# Sheet1.net
KiCad netlist of a schematic drawn in Altium Designer
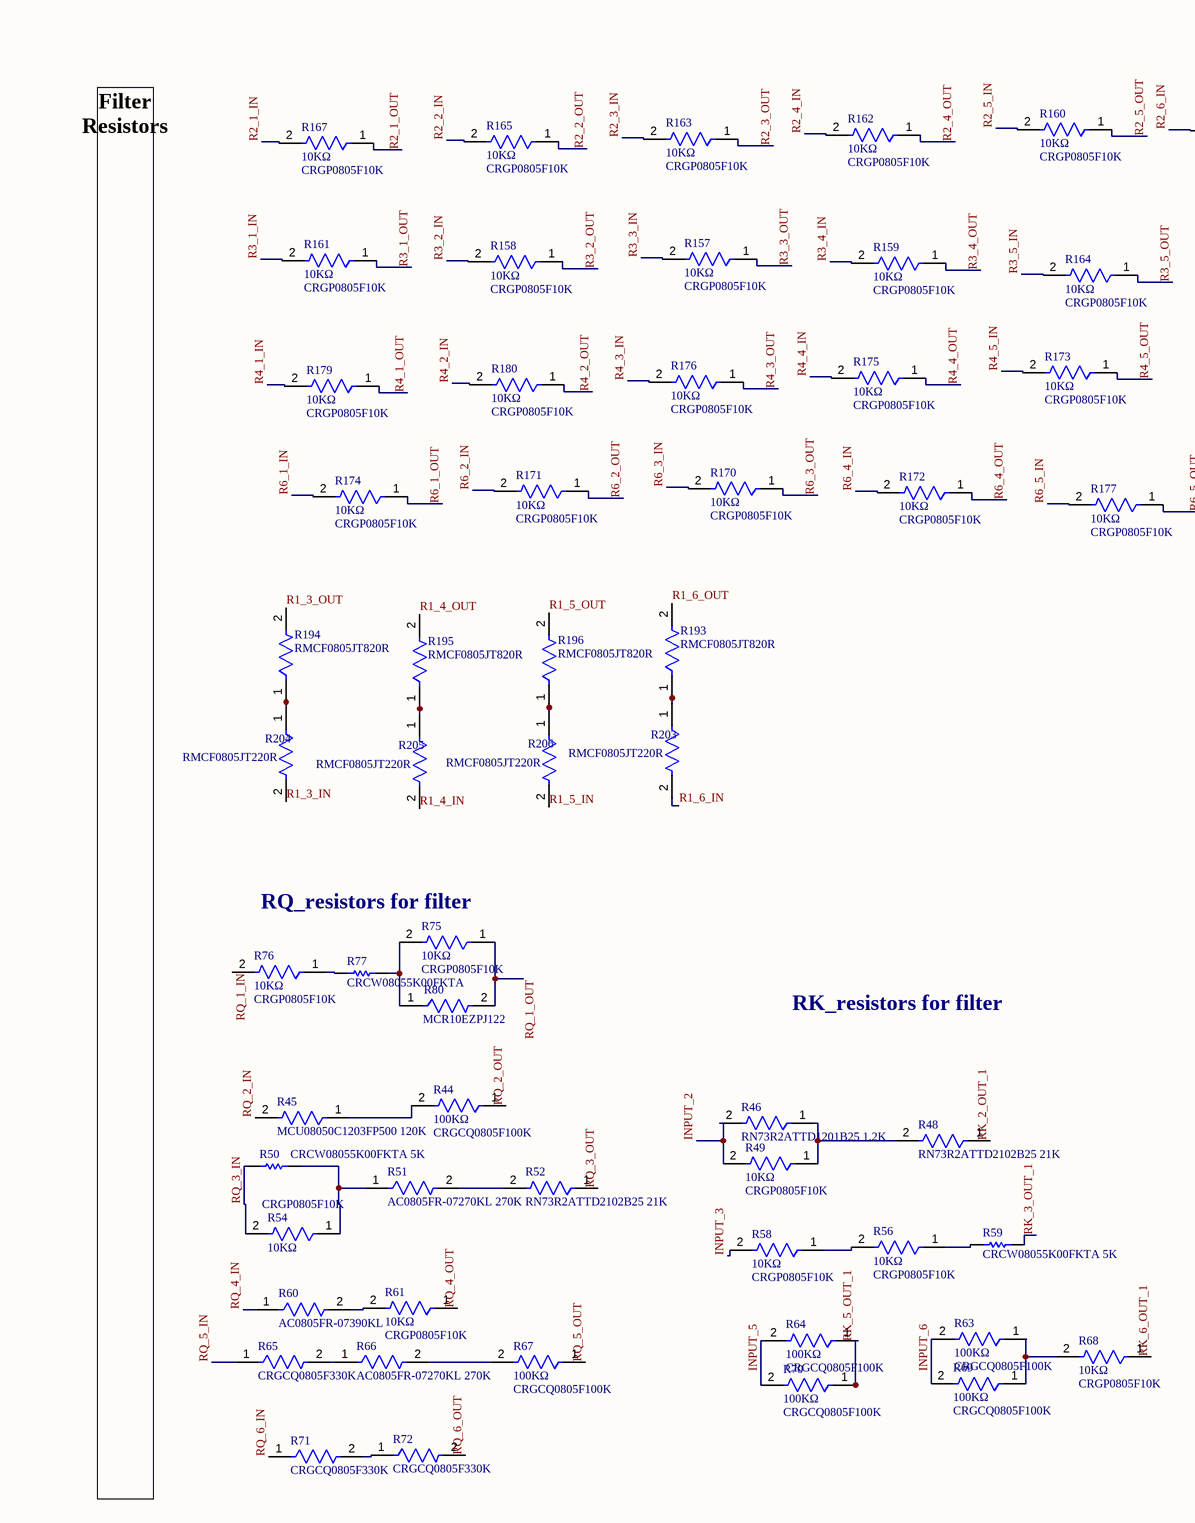
[diagram p0: Sheet1.SchDoc, top left]
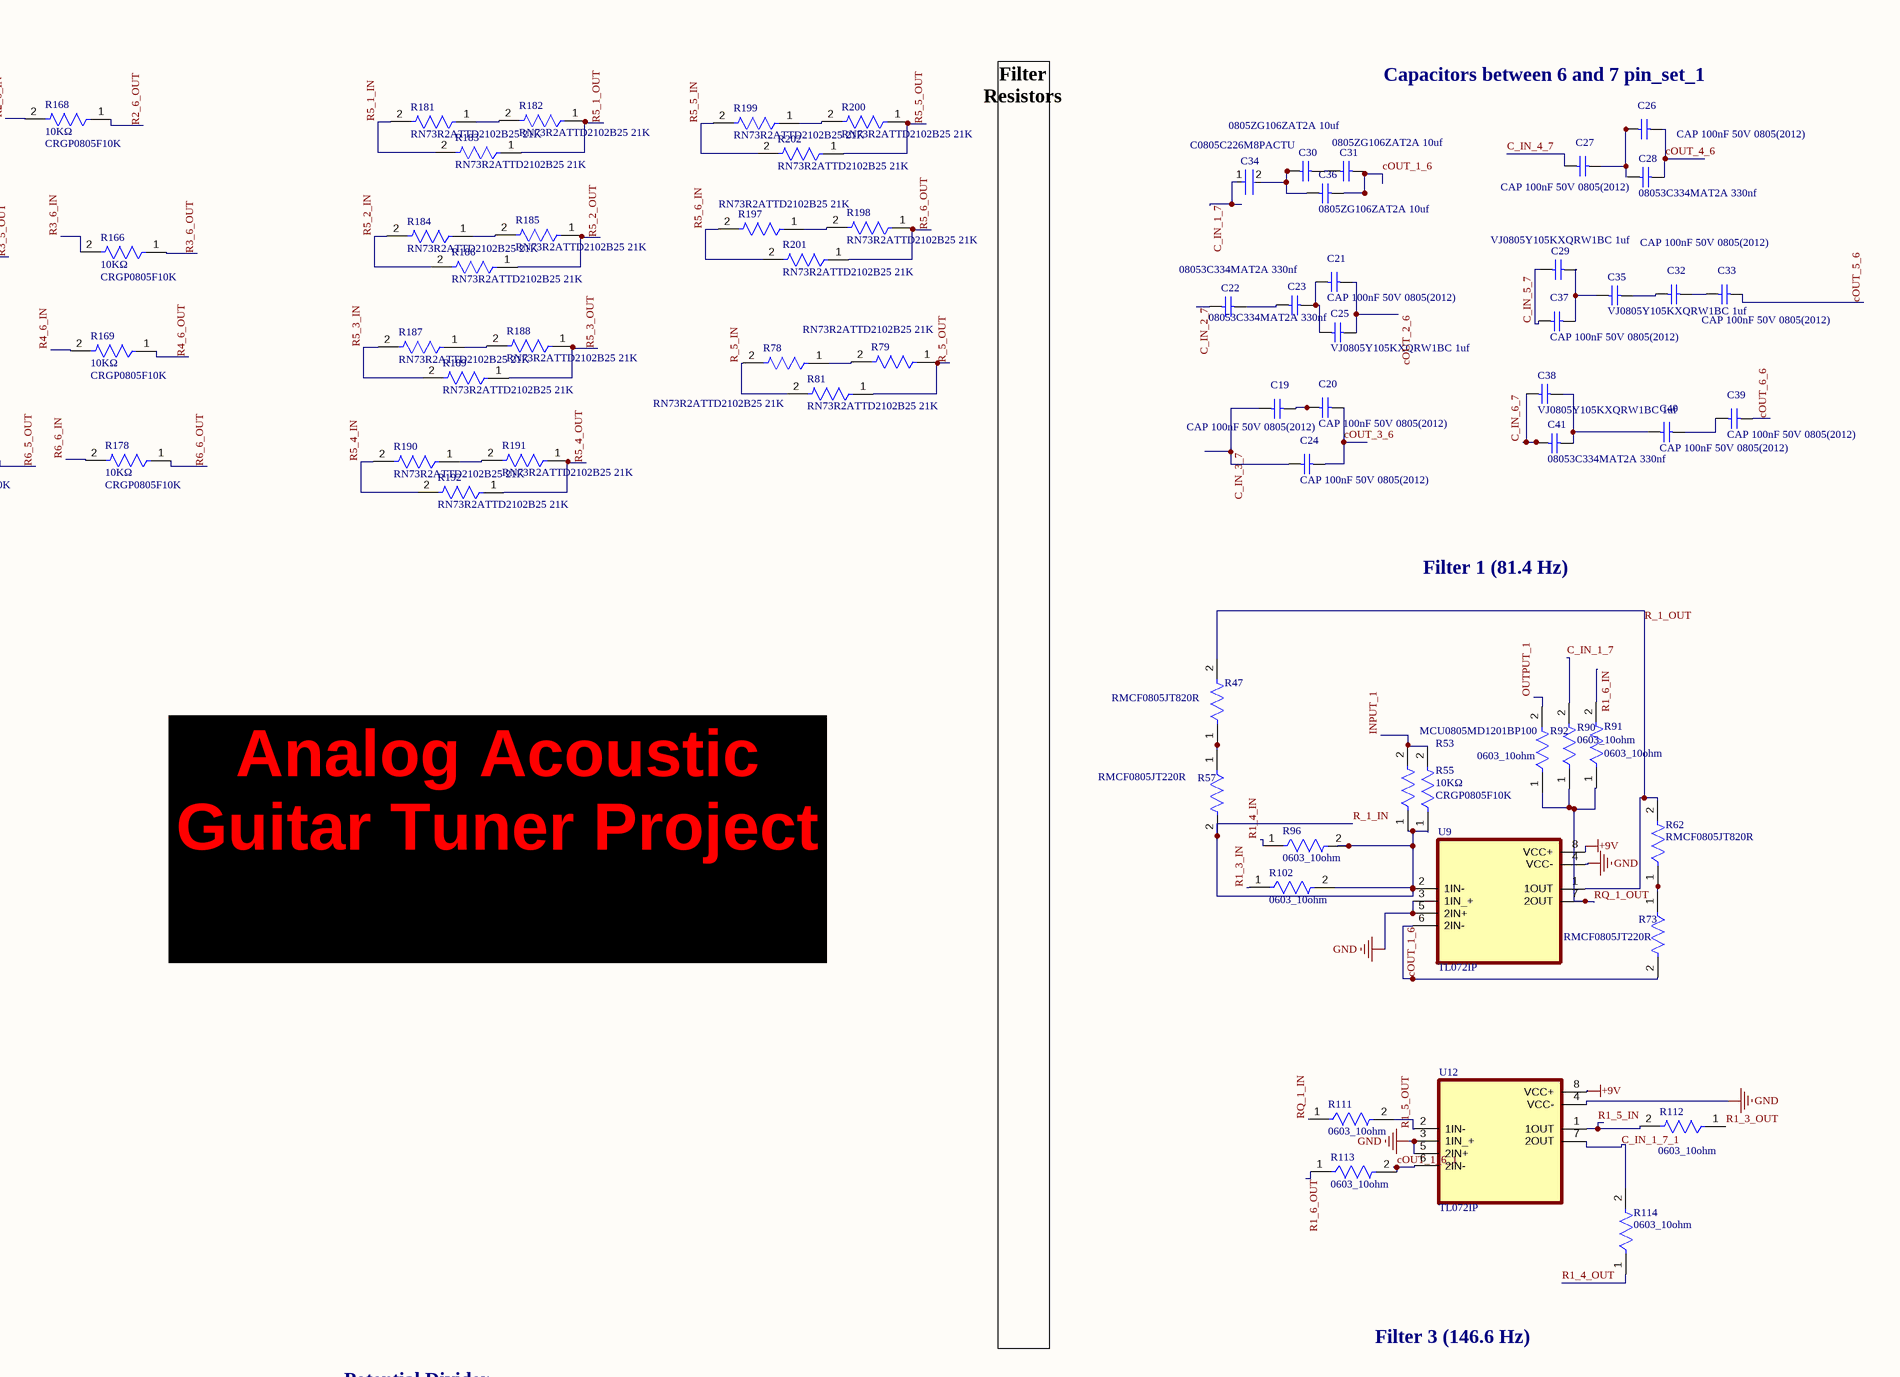
[diagram p1: Sheet1.SchDoc, top middle]
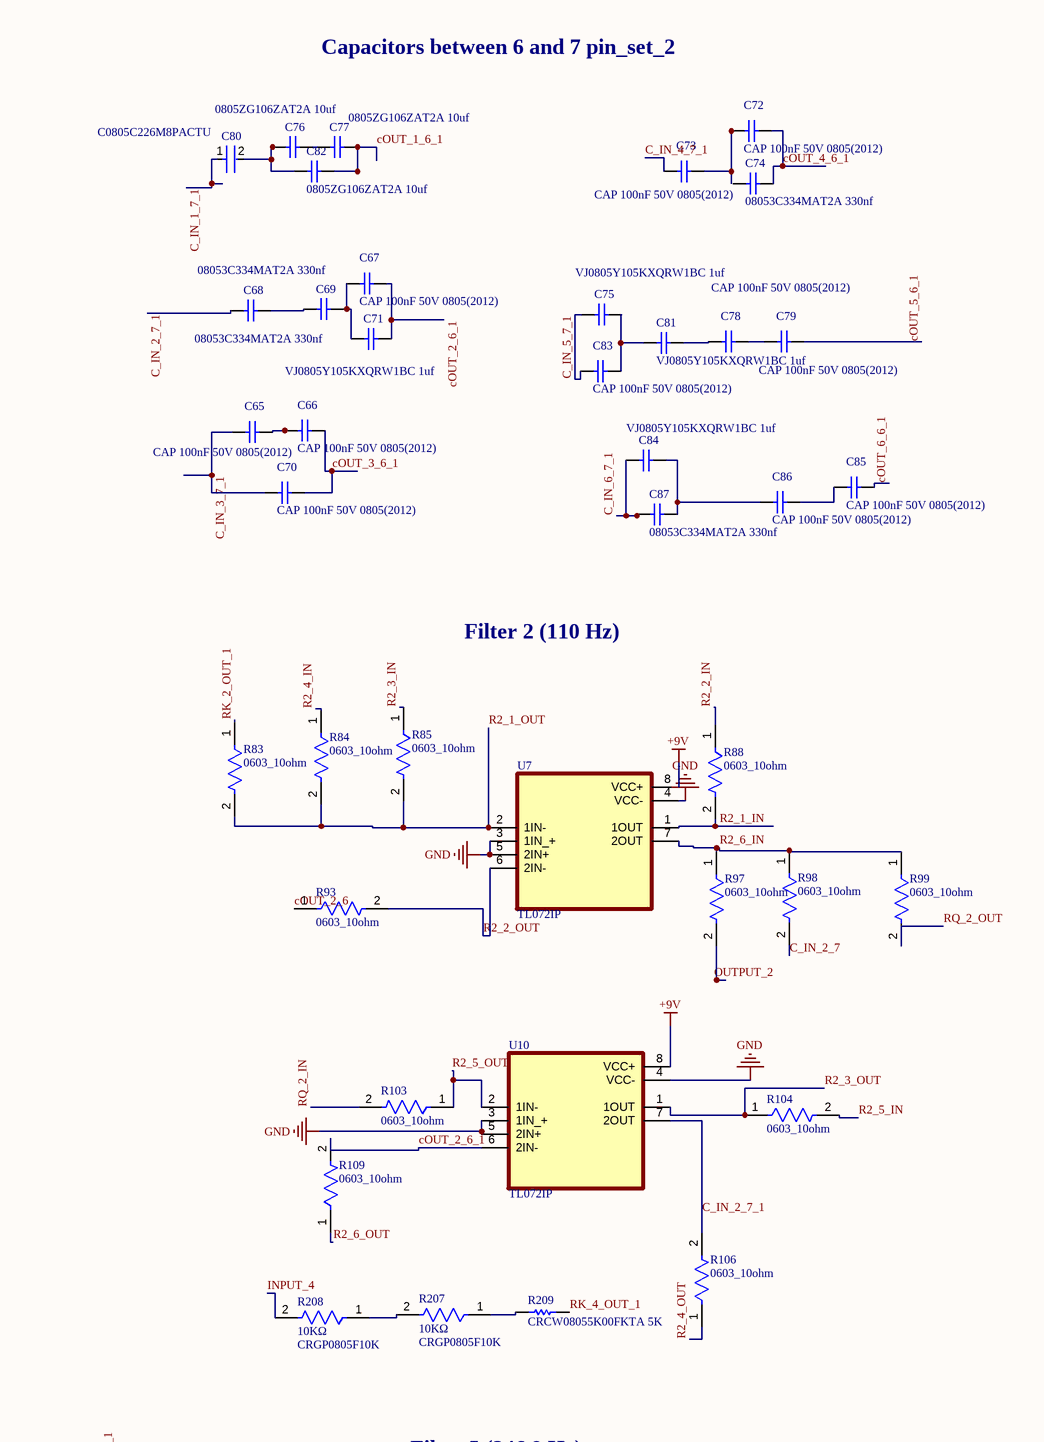
[diagram p2: Sheet1.SchDoc, top right]
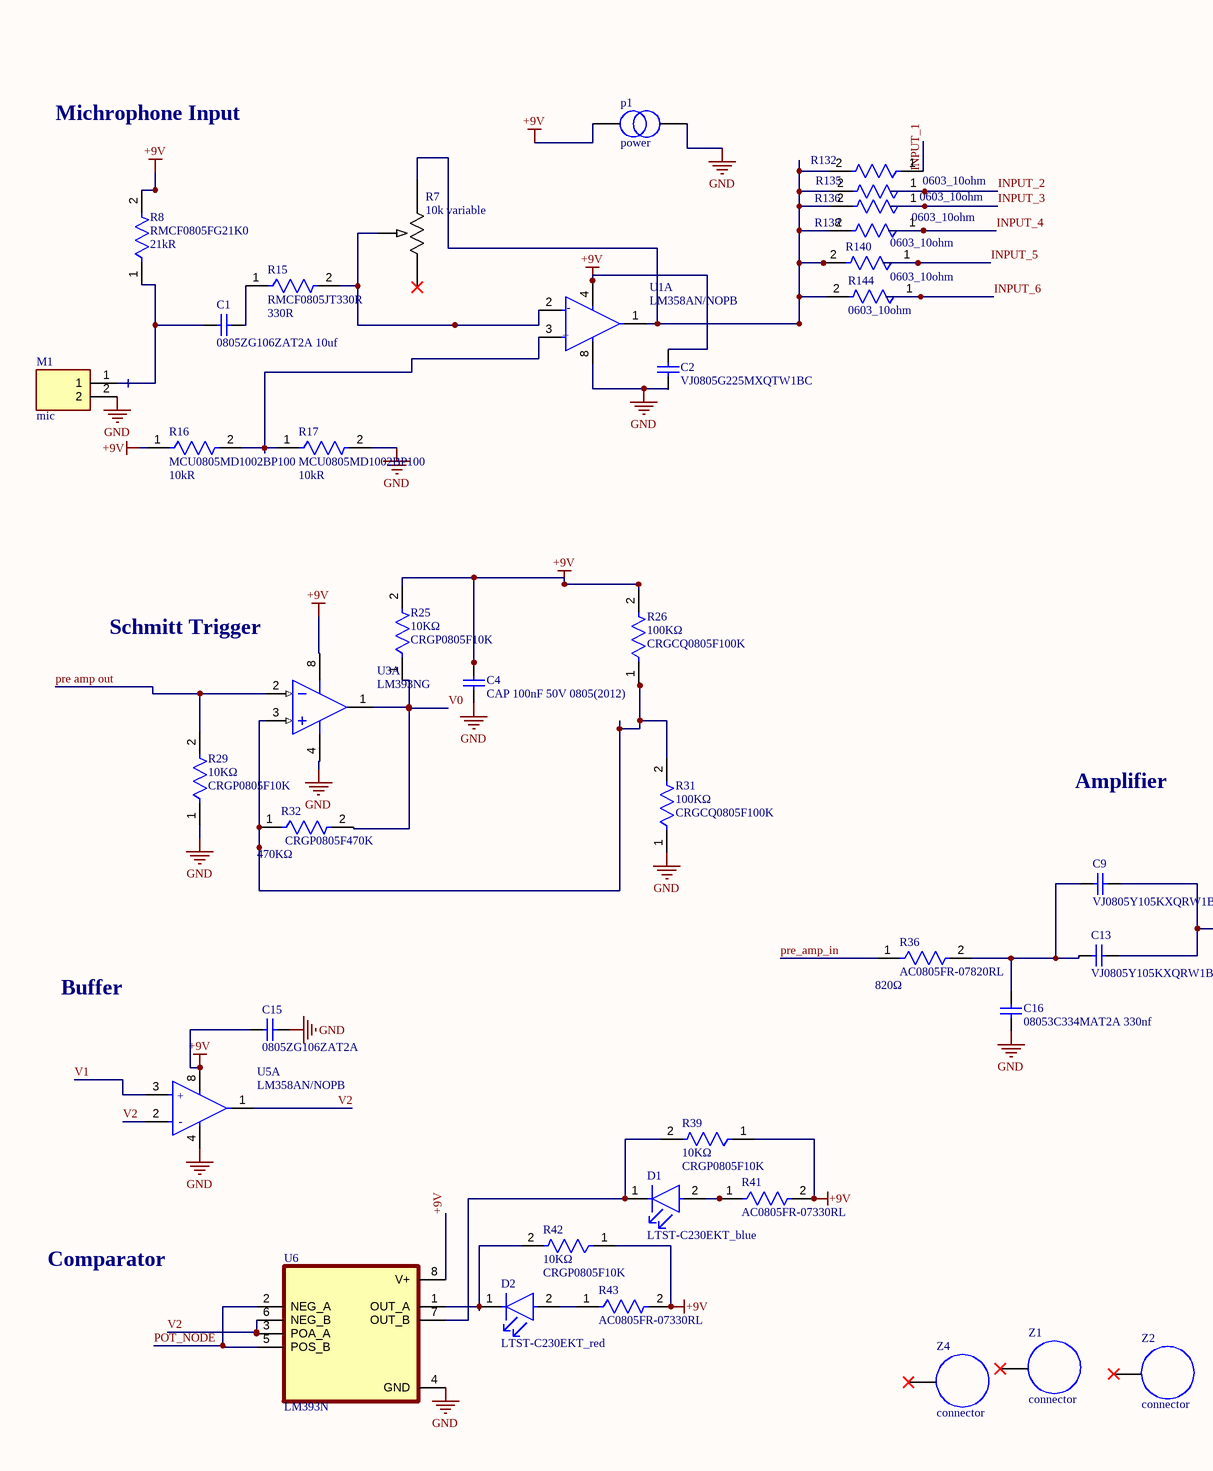
[diagram p3: Sheet1.SchDoc, bottom left]
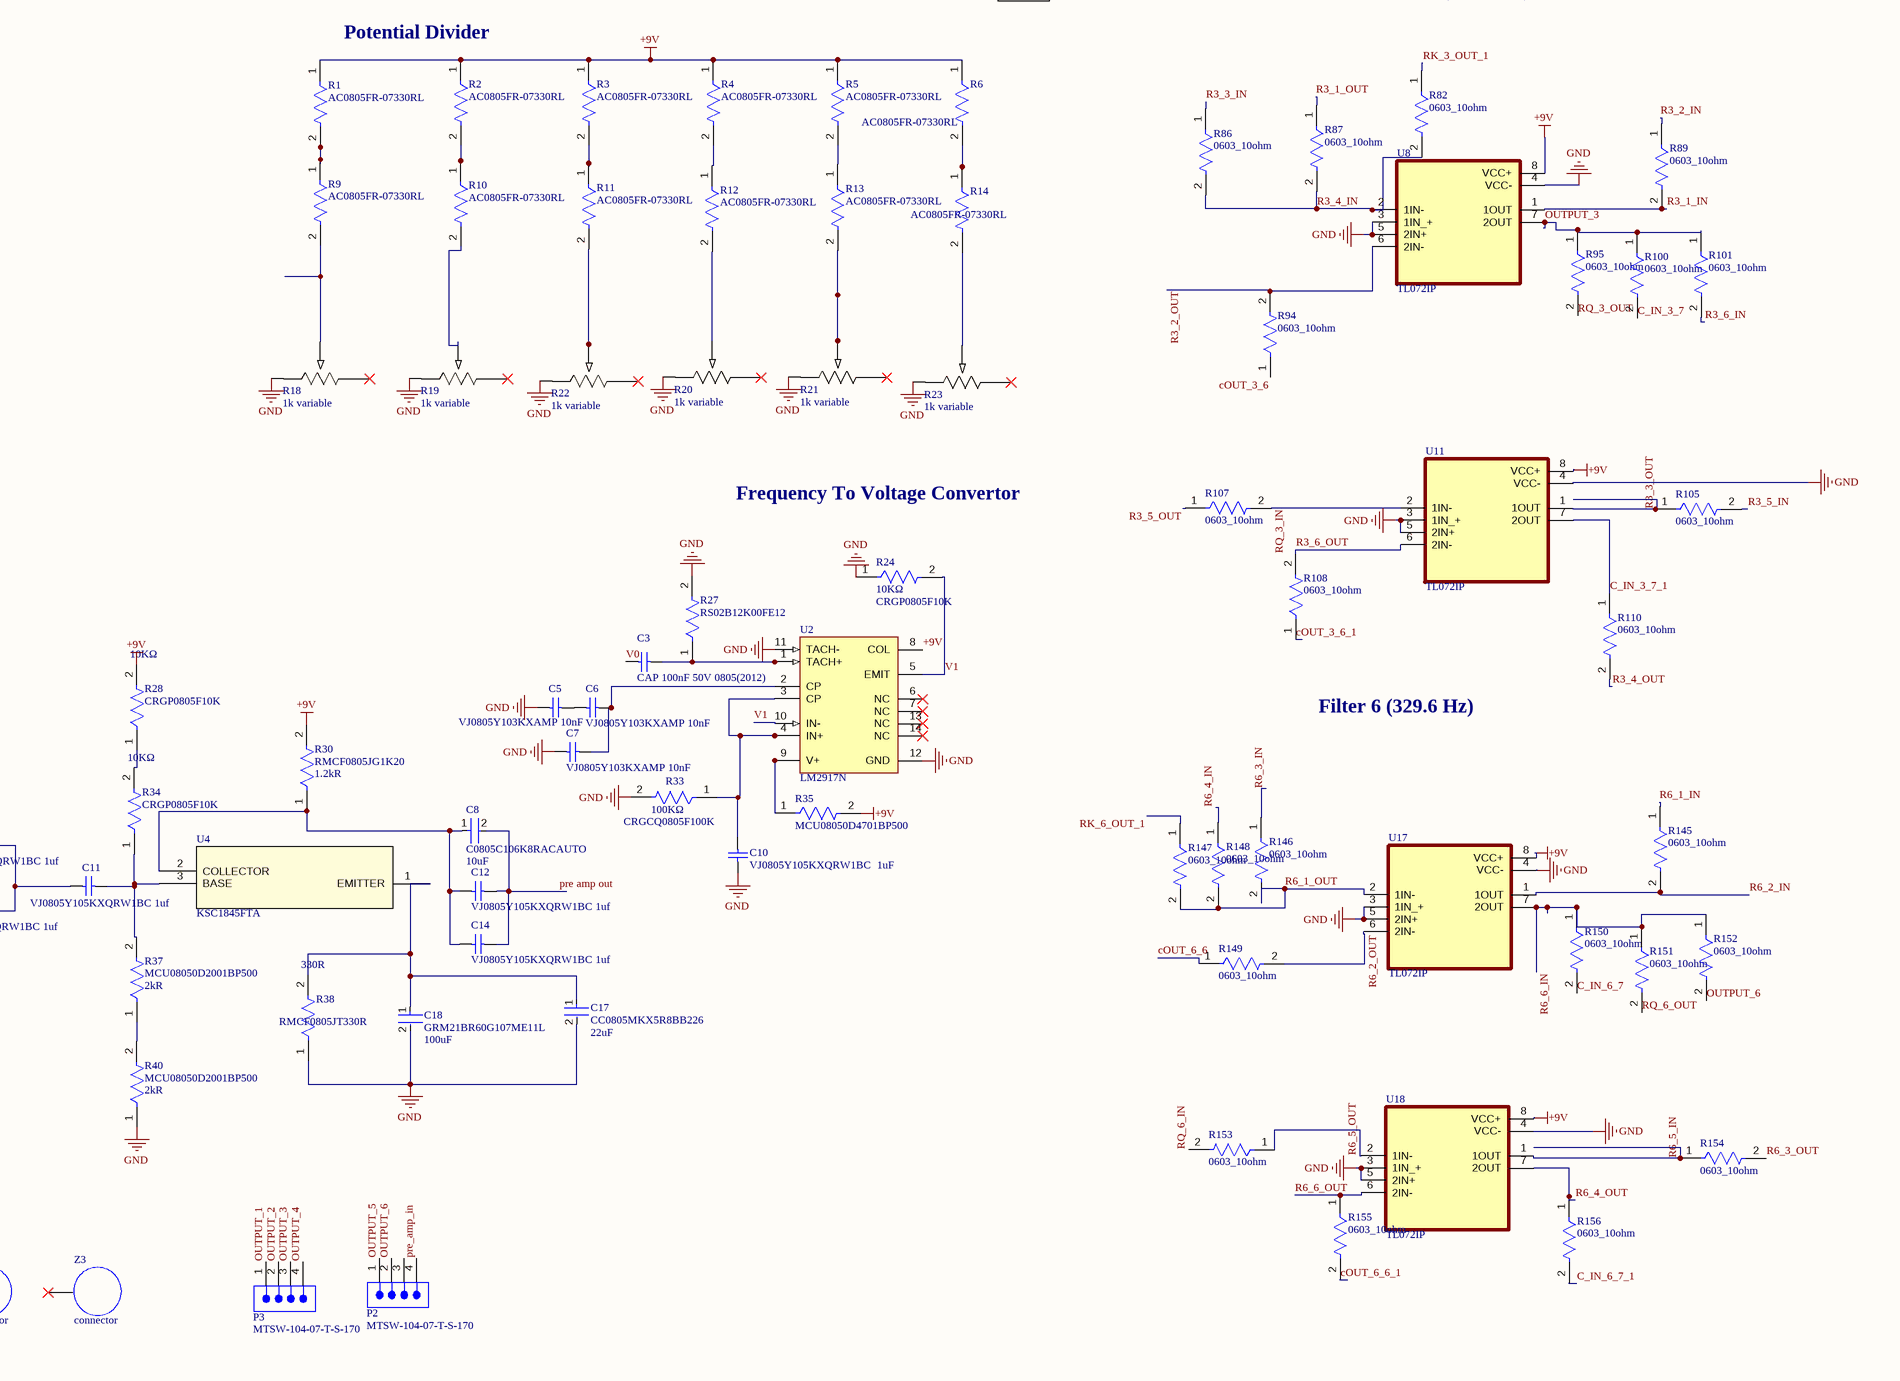
[diagram p4: Sheet1.SchDoc, bottom middle]
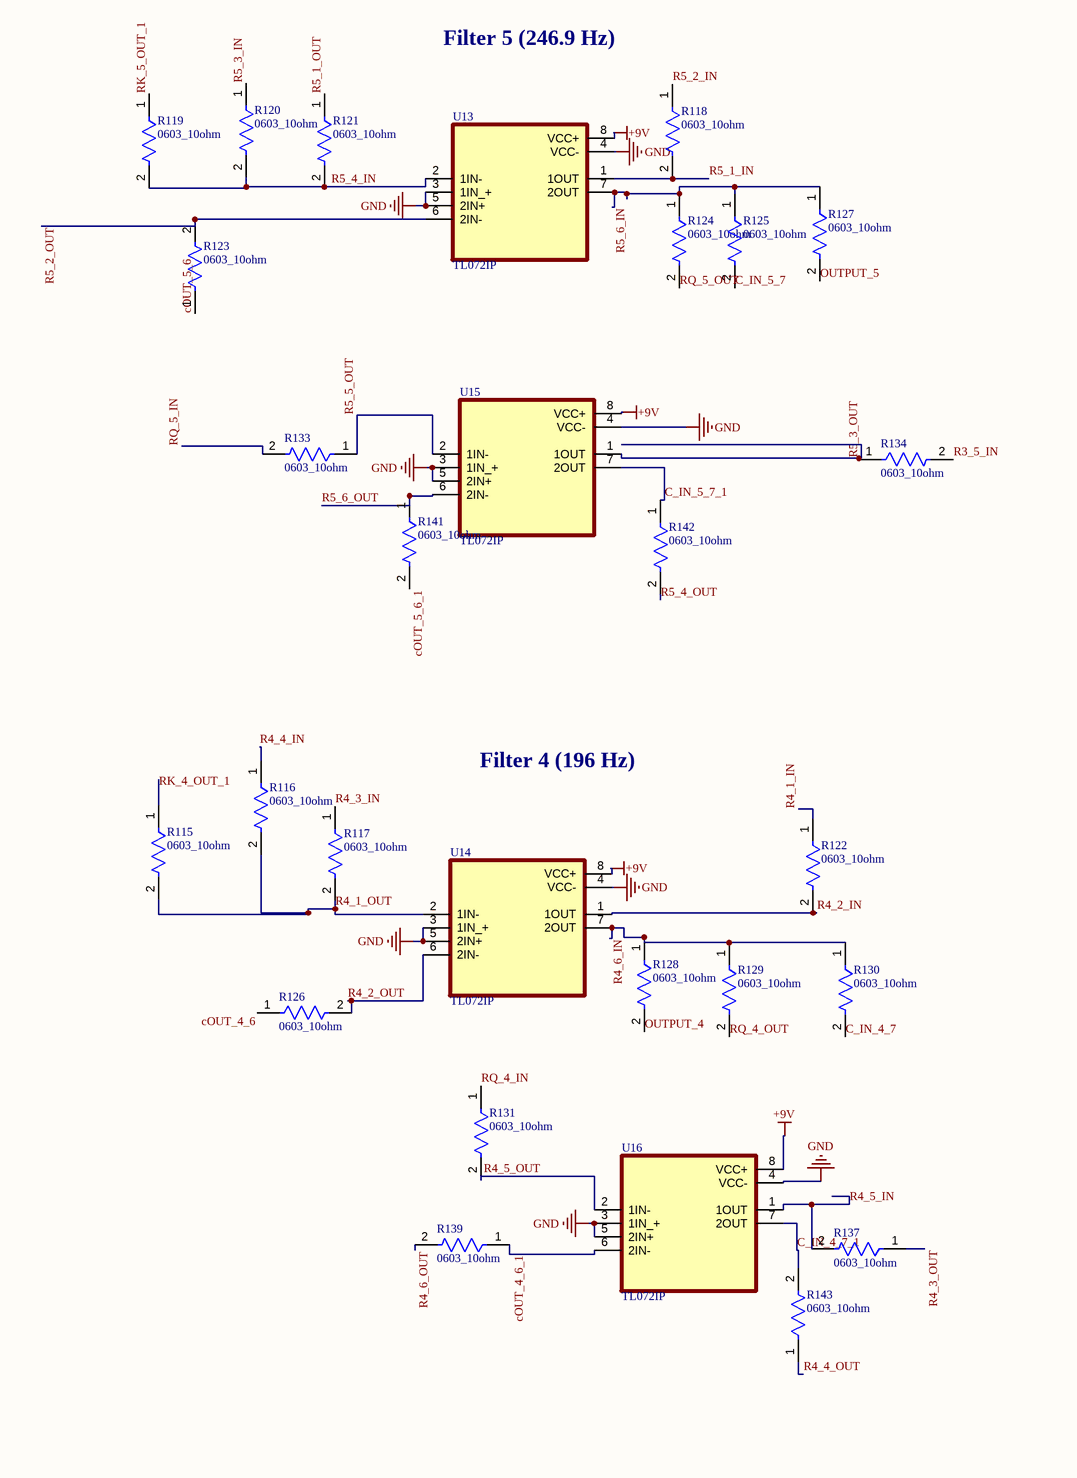
[diagram p5: Sheet1.SchDoc, bottom right]

(export (version "E")
  (design (tool "Eeschema 10.0.6"))
  (components
    (comp (ref "C1")
      (value "0805ZG106ZAT2A 10uf")
      (footprint "CAPC2013X152X50NL20T25")
      (fields
        (field (name "PART NUMBER") "0805ZG106ZAT2A")
        (field (name "MANUFACTURER") "AVX Interconnect / Elco")
      )
      (libsource (lib "Altium Content Vault") (part "CAP"))
    )
    (comp (ref "C2")
      (value "VJ0805G225MXQTW1BC")
      (footprint "CAPC2013X145X50ML20T20")
      (fields (field (name "MANUFACTURER") "Vitramon"))
      (libsource (lib "Altium Content Vault") (part "CAP"))
    )
    (comp (ref "C3")
      (value "CAP 100nF 50V 0805(2012)")
      (footprint "CAPC0805(2012)145_N")
      (description "CAP 100nF 50V ±5% 0805 (2012 Metric) Thickness 1.45mm SMD")
      (fields (field (name "TOLERANCE") "Â±5%"))
      (libsource (lib "Altium Content Vault") (part "CAP"))
    )
    (comp (ref "C4")
      (value "CAP 100nF 50V 0805(2012)")
      (footprint "CAPC0805(2012)145_N")
      (description "CAP 100nF 50V ±5% 0805 (2012 Metric) Thickness 1.45mm SMD")
      (fields (field (name "TOLERANCE") "Â±5%"))
      (libsource (lib "Altium Content Vault") (part "CAP"))
    )
    (comp (ref "C5")
      (value "VJ0805Y103KXAMP 10nF")
      (footprint "CAPC2013X145X48LL20T23")
      (fields (field (name "MANUFACTURER") "Vitramon") (field (name "PART NUMBER") "VJ0805Y103KXAMP"))
      (libsource (lib "Altium Content Vault") (part "CAP"))
    )
    (comp (ref "C6")
      (value "VJ0805Y103KXAMP 10nF")
      (footprint "CAPC2013X145X48LL20T23")
      (fields (field (name "MANUFACTURER") "Vitramon") (field (name "PART NUMBER") "VJ0805Y103KXAMP"))
      (libsource (lib "Altium Content Vault") (part "CAP"))
    )
    (comp (ref "C7")
      (value "VJ0805Y103KXAMP 10nF")
      (footprint "CAPC2013X145X48LL20T23")
      (fields (field (name "MANUFACTURER") "Vitramon") (field (name "PART NUMBER") "VJ0805Y103KXAMP"))
      (libsource (lib "Altium Content Vault") (part "CAP"))
    )
    (comp (ref "C8")
      (value "C0805C106K8RACAUTO")
      (footprint "FP-C0805C106K8RACAUTO-MFG")
      (description "CAP CER 10UF 10V X7R 0805")
      (fields (field (name "TOLERANCE") "10%") (field (name "CAPACITANCE") "10uF"))
      (libsource (lib "Altium Content Vault") (part "b4654b650e69147ec39a6b967a45e02"))
    )
    (comp (ref "C9")
      (value "VJ0805Y105KXQRW1BC 1uf")
      (footprint "CAPC2013X145X50NL20T20")
      (fields (field (name "PART NUMBER") "VJ0805Y105KXQRW1BC") (field (name "MANUFACTURER") "Vitramon"))
      (libsource (lib "Altium Content Vault") (part "CAP"))
    )
    (comp (ref "C10")
      (value "VJ0805Y105KXQRW1BC  1uF")
      (footprint "CAPC2013X145X50NL20T20")
      (fields (field (name "PART NUMBER") "VJ0805Y105KXQRW1BC") (field (name "MANUFACTURER") "Vitramon"))
      (libsource (lib "Altium Content Vault") (part "CAP"))
    )
    (comp (ref "C11")
      (value "VJ0805Y105KXQRW1BC 1uf")
      (footprint "CAPC2013X145X50NL20T20")
      (fields (field (name "PART NUMBER") "VJ0805Y105KXQRW1BC") (field (name "MANUFACTURER") "Vitramon"))
      (libsource (lib "Altium Content Vault") (part "CAP"))
    )
    (comp (ref "C12")
      (value "VJ0805Y105KXQRW1BC 1uf")
      (footprint "CAPC2013X145X50NL20T20")
      (fields (field (name "PART NUMBER") "VJ0805Y105KXQRW1BC") (field (name "MANUFACTURER") "Vitramon"))
      (libsource (lib "Altium Content Vault") (part "CAP"))
    )
    (comp (ref "C13")
      (value "VJ0805Y105KXQRW1BC 1uf")
      (footprint "CAPC2013X145X50NL20T20")
      (fields (field (name "PART NUMBER") "VJ0805Y105KXQRW1BC") (field (name "MANUFACTURER") "Vitramon"))
      (libsource (lib "Altium Content Vault") (part "CAP"))
    )
    (comp (ref "C14")
      (value "VJ0805Y105KXQRW1BC 1uf")
      (footprint "CAPC2013X145X50NL20T20")
      (fields (field (name "PART NUMBER") "VJ0805Y105KXQRW1BC") (field (name "MANUFACTURER") "Vitramon"))
      (libsource (lib "Altium Content Vault") (part "CAP"))
    )
    (comp (ref "C15")
      (value "0805ZG106ZAT2A")
      (footprint "CAPC2013X152X50NL20T25")
      (fields (field (name "MANUFACTURER") "AVX Interconnect / Elco"))
      (libsource (lib "Altium Content Vault") (part "CAP"))
    )
    (comp (ref "C16")
      (value "08053C334MAT2A 330nf")
      (footprint "CAPC2013X140X50ML20T25")
      (fields
        (field (name "MANUFACTURER") "AVX Interconnect / Elco")
        (field (name "PART NUMBER") "08053C334MAT2A")
      )
      (libsource (lib "Altium Content Vault") (part "CAP"))
    )
    (comp (ref "C17")
      (value "CC0805MKX5R8BB226")
      (footprint "FP-CC0805-0_2-1_45-IPC_C")
      (description "CAP CER 22UF 25V X5R 0805")
      (fields (field (name "CAPACITANCE") "22uF") (field (name "TOLERANCE") "20%"))
      (libsource (lib "Altium Content Vault") (part "11868f565c42a9108669ba33697ecf6"))
    )
    (comp (ref "C18")
      (value "GRM21BR60G107ME11L")
      (footprint "FP-GRM21B-0_2-e0_2_0_7-MFG")
      (description "Chip Multilayer Ceramic Capacitors for General Purpose, 0805, 100uF, X5R, 15%, 20%, 4V")
      (fields (field (name "CAPACITANCE") "100uF") (field (name "TOLERANCE") "20%"))
      (libsource (lib "Altium Content Vault") (part "b4654b650e69147ec39a6b967a45e02"))
    )
    (comp (ref "C19")
      (value "CAP 100nF 50V 0805(2012)")
      (footprint "CAPC0805(2012)145_N")
      (description "CAP 100nF 50V ±5% 0805 (2012 Metric) Thickness 1.45mm SMD")
      (fields (field (name "TOLERANCE") "Â±5%"))
      (libsource (lib "Altium Content Vault") (part "CAP"))
    )
    (comp (ref "C20")
      (value "CAP 100nF 50V 0805(2012)")
      (footprint "CAPC0805(2012)145_N")
      (description "CAP 100nF 50V ±5% 0805 (2012 Metric) Thickness 1.45mm SMD")
      (fields (field (name "TOLERANCE") "Â±5%"))
      (libsource (lib "Altium Content Vault") (part "CAP"))
    )
    (comp (ref "C21")
      (value "CAP 100nF 50V 0805(2012)")
      (footprint "CAPC0805(2012)145_N")
      (description "CAP 100nF 50V ±5% 0805 (2012 Metric) Thickness 1.45mm SMD")
      (fields (field (name "TOLERANCE") "Â±5%"))
      (libsource (lib "Altium Content Vault") (part "CAP"))
    )
    (comp (ref "C22")
      (value "08053C334MAT2A 330nf")
      (footprint "CAPC2013X140X50ML20T25")
      (fields
        (field (name "MANUFACTURER") "AVX Interconnect / Elco")
        (field (name "PART NUMBER") "08053C334MAT2A")
      )
      (libsource (lib "Altium Content Vault") (part "CAP"))
    )
    (comp (ref "C23")
      (value "08053C334MAT2A 330nf")
      (footprint "CAPC2013X140X50ML20T25")
      (fields
        (field (name "MANUFACTURER") "AVX Interconnect / Elco")
        (field (name "PART NUMBER") "08053C334MAT2A")
      )
      (libsource (lib "Altium Content Vault") (part "CAP"))
    )
    (comp (ref "C24")
      (value "CAP 100nF 50V 0805(2012)")
      (footprint "CAPC0805(2012)145_N")
      (description "CAP 100nF 50V ±5% 0805 (2012 Metric) Thickness 1.45mm SMD")
      (fields (field (name "TOLERANCE") "Â±5%"))
      (libsource (lib "Altium Content Vault") (part "CAP"))
    )
    (comp (ref "C25")
      (value "VJ0805Y105KXQRW1BC 1uf")
      (footprint "CAPC2013X145X50NL20T20")
      (fields (field (name "PART NUMBER") "VJ0805Y105KXQRW1BC") (field (name "MANUFACTURER") "Vitramon"))
      (libsource (lib "Altium Content Vault") (part "CAP"))
    )
    (comp (ref "C26")
      (value "CAP 100nF 50V 0805(2012)")
      (footprint "CAPC0805(2012)145_N")
      (description "CAP 100nF 50V ±5% 0805 (2012 Metric) Thickness 1.45mm SMD")
      (fields (field (name "TOLERANCE") "Â±5%"))
      (libsource (lib "Altium Content Vault") (part "CAP"))
    )
    (comp (ref "C27")
      (value "CAP 100nF 50V 0805(2012)")
      (footprint "CAPC0805(2012)145_N")
      (description "CAP 100nF 50V ±5% 0805 (2012 Metric) Thickness 1.45mm SMD")
      (fields (field (name "TOLERANCE") "Â±5%"))
      (libsource (lib "Altium Content Vault") (part "CAP"))
    )
    (comp (ref "C28")
      (value "08053C334MAT2A 330nf")
      (footprint "CAPC2013X140X50ML20T25")
      (fields
        (field (name "MANUFACTURER") "AVX Interconnect / Elco")
        (field (name "PART NUMBER") "08053C334MAT2A")
      )
      (libsource (lib "Altium Content Vault") (part "CAP"))
    )
    (comp (ref "C29")
      (value "VJ0805Y105KXQRW1BC 1uf")
      (footprint "CAPC2013X145X50NL20T20")
      (fields (field (name "PART NUMBER") "VJ0805Y105KXQRW1BC") (field (name "MANUFACTURER") "Vitramon"))
      (libsource (lib "Altium Content Vault") (part "CAP"))
    )
    (comp (ref "C30")
      (value "0805ZG106ZAT2A 10uf")
      (footprint "CAPC2013X152X50NL20T25")
      (fields
        (field (name "PART NUMBER") "0805ZG106ZAT2A")
        (field (name "MANUFACTURER") "AVX Interconnect / Elco")
      )
      (libsource (lib "Altium Content Vault") (part "CAP"))
    )
    (comp (ref "C31")
      (value "0805ZG106ZAT2A 10uf")
      (footprint "CAPC2013X152X50NL20T25")
      (fields
        (field (name "PART NUMBER") "0805ZG106ZAT2A")
        (field (name "MANUFACTURER") "AVX Interconnect / Elco")
      )
      (libsource (lib "Altium Content Vault") (part "CAP"))
    )
    (comp (ref "C32")
      (value "CAP 100nF 50V 0805(2012)")
      (footprint "CAPC0805(2012)145_N")
      (description "CAP 100nF 50V ±5% 0805 (2012 Metric) Thickness 1.45mm SMD")
      (fields (field (name "TOLERANCE") "Â±5%"))
      (libsource (lib "Altium Content Vault") (part "CAP"))
    )
    (comp (ref "C33")
      (value "CAP 100nF 50V 0805(2012)")
      (footprint "CAPC0805(2012)145_N")
      (description "CAP 100nF 50V ±5% 0805 (2012 Metric) Thickness 1.45mm SMD")
      (fields (field (name "TOLERANCE") "Â±5%"))
      (libsource (lib "Altium Content Vault") (part "CAP"))
    )
    (comp (ref "C34")
      (value "C0805C226M8PACTU")
      (footprint "FP-C0805C226M8PACTU-MFG")
      (description "CAP CER 22UF 10V X5R 0805")
      (fields (field (name "TOLERANCE") "20%") (field (name "VOLTAGE") "10V"))
      (libsource (lib "Altium Content Vault") (part "02cd4be3c70576c341d710602a673aa"))
    )
    (comp (ref "C35")
      (value "VJ0805Y105KXQRW1BC 1uf")
      (footprint "CAPC2013X145X50NL20T20")
      (fields (field (name "PART NUMBER") "VJ0805Y105KXQRW1BC") (field (name "MANUFACTURER") "Vitramon"))
      (libsource (lib "Altium Content Vault") (part "CAP"))
    )
    (comp (ref "C36")
      (value "0805ZG106ZAT2A 10uf")
      (footprint "CAPC2013X152X50NL20T25")
      (fields
        (field (name "PART NUMBER") "0805ZG106ZAT2A")
        (field (name "MANUFACTURER") "AVX Interconnect / Elco")
      )
      (libsource (lib "Altium Content Vault") (part "CAP"))
    )
    (comp (ref "C37")
      (value "CAP 100nF 50V 0805(2012)")
      (footprint "CAPC0805(2012)145_N")
      (description "CAP 100nF 50V ±5% 0805 (2012 Metric) Thickness 1.45mm SMD")
      (fields (field (name "TOLERANCE") "Â±5%"))
      (libsource (lib "Altium Content Vault") (part "CAP"))
    )
    (comp (ref "C38")
      (value "VJ0805Y105KXQRW1BC 1uf")
      (footprint "CAPC2013X145X50NL20T20")
      (fields (field (name "PART NUMBER") "VJ0805Y105KXQRW1BC") (field (name "MANUFACTURER") "Vitramon"))
      (libsource (lib "Altium Content Vault") (part "CAP"))
    )
    (comp (ref "C39")
      (value "CAP 100nF 50V 0805(2012)")
      (footprint "CAPC0805(2012)145_N")
      (description "CAP 100nF 50V ±5% 0805 (2012 Metric) Thickness 1.45mm SMD")
      (fields (field (name "TOLERANCE") "Â±5%"))
      (libsource (lib "Altium Content Vault") (part "CAP"))
    )
    (comp (ref "C40")
      (value "CAP 100nF 50V 0805(2012)")
      (footprint "CAPC0805(2012)145_N")
      (description "CAP 100nF 50V ±5% 0805 (2012 Metric) Thickness 1.45mm SMD")
      (fields (field (name "TOLERANCE") "Â±5%"))
      (libsource (lib "Altium Content Vault") (part "CAP"))
    )
    (comp (ref "C41")
      (value "08053C334MAT2A 330nf")
      (footprint "CAPC2013X140X50ML20T25")
      (fields
        (field (name "MANUFACTURER") "AVX Interconnect / Elco")
        (field (name "PART NUMBER") "08053C334MAT2A")
      )
      (libsource (lib "Altium Content Vault") (part "CAP"))
    )
    (comp (ref "C65")
      (value "CAP 100nF 50V 0805(2012)")
      (footprint "CAPC0805(2012)145_N")
      (description "CAP 100nF 50V ±5% 0805 (2012 Metric) Thickness 1.45mm SMD")
      (fields (field (name "TOLERANCE") "Â±5%"))
      (libsource (lib "Altium Content Vault") (part "CAP"))
    )
    (comp (ref "C66")
      (value "CAP 100nF 50V 0805(2012)")
      (footprint "CAPC0805(2012)145_N")
      (description "CAP 100nF 50V ±5% 0805 (2012 Metric) Thickness 1.45mm SMD")
      (fields (field (name "TOLERANCE") "Â±5%"))
      (libsource (lib "Altium Content Vault") (part "CAP"))
    )
    (comp (ref "C67")
      (value "CAP 100nF 50V 0805(2012)")
      (footprint "CAPC0805(2012)145_N")
      (description "CAP 100nF 50V ±5% 0805 (2012 Metric) Thickness 1.45mm SMD")
      (fields (field (name "TOLERANCE") "Â±5%"))
      (libsource (lib "Altium Content Vault") (part "CAP"))
    )
    (comp (ref "C68")
      (value "08053C334MAT2A 330nf")
      (footprint "CAPC2013X140X50ML20T25")
      (fields
        (field (name "MANUFACTURER") "AVX Interconnect / Elco")
        (field (name "PART NUMBER") "08053C334MAT2A")
      )
      (libsource (lib "Altium Content Vault") (part "CAP"))
    )
    (comp (ref "C69")
      (value "08053C334MAT2A 330nf")
      (footprint "CAPC2013X140X50ML20T25")
      (fields
        (field (name "MANUFACTURER") "AVX Interconnect / Elco")
        (field (name "PART NUMBER") "08053C334MAT2A")
      )
      (libsource (lib "Altium Content Vault") (part "CAP"))
    )
    (comp (ref "C70")
      (value "CAP 100nF 50V 0805(2012)")
      (footprint "CAPC0805(2012)145_N")
      (description "CAP 100nF 50V ±5% 0805 (2012 Metric) Thickness 1.45mm SMD")
      (fields (field (name "TOLERANCE") "Â±5%"))
      (libsource (lib "Altium Content Vault") (part "CAP"))
    )
    (comp (ref "C71")
      (value "VJ0805Y105KXQRW1BC 1uf")
      (footprint "CAPC2013X145X50NL20T20")
      (fields (field (name "PART NUMBER") "VJ0805Y105KXQRW1BC") (field (name "MANUFACTURER") "Vitramon"))
      (libsource (lib "Altium Content Vault") (part "CAP"))
    )
    (comp (ref "C72")
      (value "CAP 100nF 50V 0805(2012)")
      (footprint "CAPC0805(2012)145_N")
      (description "CAP 100nF 50V ±5% 0805 (2012 Metric) Thickness 1.45mm SMD")
      (fields (field (name "TOLERANCE") "Â±5%"))
      (libsource (lib "Altium Content Vault") (part "CAP"))
    )
    (comp (ref "C73")
      (value "CAP 100nF 50V 0805(2012)")
      (footprint "CAPC0805(2012)145_N")
      (description "CAP 100nF 50V ±5% 0805 (2012 Metric) Thickness 1.45mm SMD")
      (fields (field (name "TOLERANCE") "Â±5%"))
      (libsource (lib "Altium Content Vault") (part "CAP"))
    )
    (comp (ref "C74")
      (value "08053C334MAT2A 330nf")
      (footprint "CAPC2013X140X50ML20T25")
      (fields
        (field (name "MANUFACTURER") "AVX Interconnect / Elco")
        (field (name "PART NUMBER") "08053C334MAT2A")
      )
      (libsource (lib "Altium Content Vault") (part "CAP"))
    )
    (comp (ref "C75")
      (value "VJ0805Y105KXQRW1BC 1uf")
      (footprint "CAPC2013X145X50NL20T20")
      (fields (field (name "PART NUMBER") "VJ0805Y105KXQRW1BC") (field (name "MANUFACTURER") "Vitramon"))
      (libsource (lib "Altium Content Vault") (part "CAP"))
    )
    (comp (ref "C76")
      (value "0805ZG106ZAT2A 10uf")
      (footprint "CAPC2013X152X50NL20T25")
      (fields
        (field (name "PART NUMBER") "0805ZG106ZAT2A")
        (field (name "MANUFACTURER") "AVX Interconnect / Elco")
      )
      (libsource (lib "Altium Content Vault") (part "CAP"))
    )
    (comp (ref "C77")
      (value "0805ZG106ZAT2A 10uf")
      (footprint "CAPC2013X152X50NL20T25")
      (fields
        (field (name "PART NUMBER") "0805ZG106ZAT2A")
        (field (name "MANUFACTURER") "AVX Interconnect / Elco")
      )
      (libsource (lib "Altium Content Vault") (part "CAP"))
    )
    (comp (ref "C78")
      (value "CAP 100nF 50V 0805(2012)")
      (footprint "CAPC0805(2012)145_N")
      (description "CAP 100nF 50V ±5% 0805 (2012 Metric) Thickness 1.45mm SMD")
      (fields (field (name "TOLERANCE") "Â±5%"))
      (libsource (lib "Altium Content Vault") (part "CAP"))
    )
    (comp (ref "C79")
      (value "CAP 100nF 50V 0805(2012)")
      (footprint "CAPC0805(2012)145_N")
      (description "CAP 100nF 50V ±5% 0805 (2012 Metric) Thickness 1.45mm SMD")
      (fields (field (name "TOLERANCE") "Â±5%"))
      (libsource (lib "Altium Content Vault") (part "CAP"))
    )
    (comp (ref "C80")
      (value "C0805C226M8PACTU")
      (footprint "FP-C0805C226M8PACTU-MFG")
      (description "CAP CER 22UF 10V X5R 0805")
      (fields (field (name "TOLERANCE") "20%") (field (name "VOLTAGE") "10V"))
      (libsource (lib "Altium Content Vault") (part "02cd4be3c70576c341d710602a673aa"))
    )
    (comp (ref "C81")
      (value "VJ0805Y105KXQRW1BC 1uf")
      (footprint "CAPC2013X145X50NL20T20")
      (fields (field (name "PART NUMBER") "VJ0805Y105KXQRW1BC") (field (name "MANUFACTURER") "Vitramon"))
      (libsource (lib "Altium Content Vault") (part "CAP"))
    )
    (comp (ref "C82")
      (value "0805ZG106ZAT2A 10uf")
      (footprint "CAPC2013X152X50NL20T25")
      (fields
        (field (name "PART NUMBER") "0805ZG106ZAT2A")
        (field (name "MANUFACTURER") "AVX Interconnect / Elco")
      )
      (libsource (lib "Altium Content Vault") (part "CAP"))
    )
    (comp (ref "C83")
      (value "CAP 100nF 50V 0805(2012)")
      (footprint "CAPC0805(2012)145_N")
      (description "CAP 100nF 50V ±5% 0805 (2012 Metric) Thickness 1.45mm SMD")
      (fields (field (name "TOLERANCE") "Â±5%"))
      (libsource (lib "Altium Content Vault") (part "CAP"))
    )
    (comp (ref "C84")
      (value "VJ0805Y105KXQRW1BC 1uf")
      (footprint "CAPC2013X145X50NL20T20")
      (fields (field (name "PART NUMBER") "VJ0805Y105KXQRW1BC") (field (name "MANUFACTURER") "Vitramon"))
      (libsource (lib "Altium Content Vault") (part "CAP"))
    )
    (comp (ref "C85")
      (value "CAP 100nF 50V 0805(2012)")
      (footprint "CAPC0805(2012)145_N")
      (description "CAP 100nF 50V ±5% 0805 (2012 Metric) Thickness 1.45mm SMD")
      (fields (field (name "TOLERANCE") "Â±5%"))
      (libsource (lib "Altium Content Vault") (part "CAP"))
    )
    (comp (ref "C86")
      (value "CAP 100nF 50V 0805(2012)")
      (footprint "CAPC0805(2012)145_N")
      (description "CAP 100nF 50V ±5% 0805 (2012 Metric) Thickness 1.45mm SMD")
      (fields (field (name "TOLERANCE") "Â±5%"))
      (libsource (lib "Altium Content Vault") (part "CAP"))
    )
    (comp (ref "C87")
      (value "08053C334MAT2A 330nf")
      (footprint "CAPC2013X140X50ML20T25")
      (fields
        (field (name "MANUFACTURER") "AVX Interconnect / Elco")
        (field (name "PART NUMBER") "08053C334MAT2A")
      )
      (libsource (lib "Altium Content Vault") (part "CAP"))
    )
    (comp (ref "D1")
      (value "LTST-C230EKT_blue")
      (footprint "FP-LTST-C230EKT-MFG")
      (description "LED RED CLEAR CHIP SMD")
      (libsource (lib "Altium Content Vault") (part "8706943c75ba83719d021d2fdc84c58"))
    )
    (comp (ref "D2")
      (value "LTST-C230EKT_red")
      (footprint "FP-LTST-C230EKT-MFG")
      (description "LED RED CLEAR CHIP SMD")
      (libsource (lib "Altium Content Vault") (part "8706943c75ba83719d021d2fdc84c58"))
    )
    (comp (ref "M1")
      (value "mic")
      (footprint "CMA4544PFW")
      (description "CMA Series 10V 0.5mA 20 kHz -44 dB Omnidirectional Electret Condenser Microphone")
      (fields
        (field (name "MANUFACTURER") "Same Sky")
        (field (name "MANUFACTURER PART NUMBER") "CMA-4544PF-W")
      )
      (libsource (lib "guitar tuner schematick") (part "CMA-4544PF-W"))
    )
    (comp (ref "p1")
      (value "power")
      (footprint "DIP4")
      (libsource (lib "guitar tuner schematick") (part "power"))
    )
    (comp (ref "P2")
      (value "MTSW-104-07-T-S-170")
      (footprint "SMTC-MTSW-104-07-X-S-170")
      (fields (field (name "MANUFACTURER") "Samtec"))
      (libsource (lib "Altium Content Vault") (part "SMTC-MTSW-104-07-X-S-170"))
    )
    (comp (ref "P3")
      (value "MTSW-104-07-T-S-170")
      (footprint "SMTC-MTSW-104-07-X-S-170")
      (fields (field (name "MANUFACTURER") "Samtec"))
      (libsource (lib "Altium Content Vault") (part "SMTC-MTSW-104-07-X-S-170"))
    )
    (comp (ref "R1")
      (value "AC0805FR-07330RL")
      (footprint "FP-AC0805-MFG")
      (description "RES SMD 330 OHM 1% 1/8W 0805")
      (fields (field (name "MANUFACTURER") "Yageo") (field (name "TOLERANCE") "0.01"))
      (libsource (lib "Altium Content Vault") (part "1029c3af85768c4190bb7ad29bc67b5"))
    )
    (comp (ref "R2")
      (value "AC0805FR-07330RL")
      (footprint "FP-AC0805-MFG")
      (description "RES SMD 330 OHM 1% 1/8W 0805")
      (fields (field (name "MANUFACTURER") "Yageo") (field (name "TOLERANCE") "0.01"))
      (libsource (lib "Altium Content Vault") (part "1029c3af85768c4190bb7ad29bc67b5"))
    )
    (comp (ref "R3")
      (value "AC0805FR-07330RL")
      (footprint "FP-AC0805-MFG")
      (description "RES SMD 330 OHM 1% 1/8W 0805")
      (fields (field (name "MANUFACTURER") "Yageo") (field (name "TOLERANCE") "0.01"))
      (libsource (lib "Altium Content Vault") (part "1029c3af85768c4190bb7ad29bc67b5"))
    )
    (comp (ref "R4")
      (value "AC0805FR-07330RL")
      (footprint "FP-AC0805-MFG")
      (description "RES SMD 330 OHM 1% 1/8W 0805")
      (fields (field (name "MANUFACTURER") "Yageo") (field (name "TOLERANCE") "0.01"))
      (libsource (lib "Altium Content Vault") (part "1029c3af85768c4190bb7ad29bc67b5"))
    )
    (comp (ref "R5")
      (value "AC0805FR-07330RL")
      (footprint "FP-AC0805-MFG")
      (description "RES SMD 330 OHM 1% 1/8W 0805")
      (fields (field (name "MANUFACTURER") "Yageo") (field (name "TOLERANCE") "0.01"))
      (libsource (lib "Altium Content Vault") (part "1029c3af85768c4190bb7ad29bc67b5"))
    )
    (comp (ref "R6")
      (value "AC0805FR-07330RL")
      (footprint "FP-AC0805-MFG")
      (description "RES SMD 330 OHM 1% 1/8W 0805")
      (fields (field (name "MANUFACTURER") "Yageo") (field (name "TOLERANCE") "0.01"))
      (libsource (lib "Altium Content Vault") (part "1029c3af85768c4190bb7ad29bc67b5"))
    )
    (comp (ref "R7")
      (value "10k variable")
      (footprint "variablr resistor")
      (description "Cermet trimmer potentiometer, 25 turns, 100 kΩ, 0.5 W, THT, on top, PV36W104C01B00")
      (fields
        (field (name "MANUFACTURER") "Bourns")
        (field (name "MANUFACTURER PART NUMBER") "PV36W104C01B00")
      )
      (libsource (lib "guitar tuner schematick") (part "PV36W104C01B00"))
    )
    (comp (ref "R8")
      (value "RMCF0805FG21K0")
      (footprint "FP-RMCF0805-IPC_C")
      (description "21kΩ ±1% 0.125W 0805 Thick Film Chip Resistor AEC-Q200 compliant")
      (fields (field (name "RESISTANCE") "21kR") (field (name "TOLERANCE") "1%"))
      (libsource (lib "Altium Content Vault") (part "1029c3af85768c4190bb7ad29bc67b5"))
    )
    (comp (ref "R9")
      (value "AC0805FR-07330RL")
      (footprint "FP-AC0805-MFG")
      (description "RES SMD 330 OHM 1% 1/8W 0805")
      (fields (field (name "MANUFACTURER") "Yageo") (field (name "TOLERANCE") "0.01"))
      (libsource (lib "Altium Content Vault") (part "1029c3af85768c4190bb7ad29bc67b5"))
    )
    (comp (ref "R10")
      (value "AC0805FR-07330RL")
      (footprint "FP-AC0805-MFG")
      (description "RES SMD 330 OHM 1% 1/8W 0805")
      (fields (field (name "MANUFACTURER") "Yageo") (field (name "TOLERANCE") "0.01"))
      (libsource (lib "Altium Content Vault") (part "1029c3af85768c4190bb7ad29bc67b5"))
    )
    (comp (ref "R11")
      (value "AC0805FR-07330RL")
      (footprint "FP-AC0805-MFG")
      (description "RES SMD 330 OHM 1% 1/8W 0805")
      (fields (field (name "MANUFACTURER") "Yageo") (field (name "TOLERANCE") "0.01"))
      (libsource (lib "Altium Content Vault") (part "1029c3af85768c4190bb7ad29bc67b5"))
    )
    (comp (ref "R12")
      (value "AC0805FR-07330RL")
      (footprint "FP-AC0805-MFG")
      (description "RES SMD 330 OHM 1% 1/8W 0805")
      (fields (field (name "MANUFACTURER") "Yageo") (field (name "TOLERANCE") "0.01"))
      (libsource (lib "Altium Content Vault") (part "1029c3af85768c4190bb7ad29bc67b5"))
    )
    (comp (ref "R13")
      (value "AC0805FR-07330RL")
      (footprint "FP-AC0805-MFG")
      (description "RES SMD 330 OHM 1% 1/8W 0805")
      (fields (field (name "MANUFACTURER") "Yageo") (field (name "TOLERANCE") "0.01"))
      (libsource (lib "Altium Content Vault") (part "1029c3af85768c4190bb7ad29bc67b5"))
    )
    (comp (ref "R14")
      (value "AC0805FR-07330RL")
      (footprint "FP-AC0805-MFG")
      (description "RES SMD 330 OHM 1% 1/8W 0805")
      (fields (field (name "MANUFACTURER") "Yageo") (field (name "TOLERANCE") "0.01"))
      (libsource (lib "Altium Content Vault") (part "1029c3af85768c4190bb7ad29bc67b5"))
    )
    (comp (ref "R15")
      (value "RMCF0805JT330R")
      (footprint "FP-RMCF0805-IPC_C")
      (description "330Ω ±5% 0.125W 0805 Thick Film Chip Resistor AEC-Q200 compliant")
      (fields (field (name "TOLERANCE") "5%") (field (name "RESISTANCE") "330R"))
      (libsource (lib "Altium Content Vault") (part "1029c3af85768c4190bb7ad29bc67b5"))
    )
    (comp (ref "R16")
      (value "MCU0805MD1002BP100")
      (footprint "FP-MCU0805-IPC_C")
      (description "RES 1.05K OHM 0.5% 1/5W 0805")
      (fields (field (name "TOLERANCE") "0.1%") (field (name "RESISTANCE") "10kR"))
      (libsource (lib "Altium Content Vault") (part "1029c3af85768c4190bb7ad29bc67b5"))
    )
    (comp (ref "R17")
      (value "MCU0805MD1002BP100")
      (footprint "FP-MCU0805-IPC_C")
      (description "RES 1.05K OHM 0.5% 1/5W 0805")
      (fields (field (name "TOLERANCE") "0.1%") (field (name "RESISTANCE") "10kR"))
      (libsource (lib "Altium Content Vault") (part "1029c3af85768c4190bb7ad29bc67b5"))
    )
    (comp (ref "R18")
      (value "1k variable")
      (footprint "variablr resistor")
      (description "Cermet trimmer potentiometer, 25 turns, 1 kΩ, 0.5 W, THT, on top, PV36W102C01B00")
      (fields
        (field (name "MANUFACTURER") "Bourns")
        (field (name "MANUFACTURER PART NUMBER") "PV36W102C01B00")
      )
      (libsource (lib "guitar tuner schematick") (part "PV36W102C01B00"))
    )
    (comp (ref "R19")
      (value "1k variable")
      (footprint "variablr resistor")
      (description "Cermet trimmer potentiometer, 25 turns, 1 kΩ, 0.5 W, THT, on top, PV36W102C01B00")
      (fields
        (field (name "MANUFACTURER") "Bourns")
        (field (name "MANUFACTURER PART NUMBER") "PV36W102C01B00")
      )
      (libsource (lib "guitar tuner schematick") (part "PV36W102C01B00"))
    )
    (comp (ref "R20")
      (value "1k variable")
      (footprint "variablr resistor")
      (description "Cermet trimmer potentiometer, 25 turns, 1 kΩ, 0.5 W, THT, on top, PV36W102C01B00")
      (fields
        (field (name "MANUFACTURER") "Bourns")
        (field (name "MANUFACTURER PART NUMBER") "PV36W102C01B00")
      )
      (libsource (lib "guitar tuner schematick") (part "PV36W102C01B00"))
    )
    (comp (ref "R21")
      (value "1k variable")
      (footprint "variablr resistor")
      (description "Cermet trimmer potentiometer, 25 turns, 1 kΩ, 0.5 W, THT, on top, PV36W102C01B00")
      (fields
        (field (name "MANUFACTURER") "Bourns")
        (field (name "MANUFACTURER PART NUMBER") "PV36W102C01B00")
      )
      (libsource (lib "guitar tuner schematick") (part "PV36W102C01B00"))
    )
    (comp (ref "R22")
      (value "1k variable")
      (footprint "variablr resistor")
      (description "Cermet trimmer potentiometer, 25 turns, 1 kΩ, 0.5 W, THT, on top, PV36W102C01B00")
      (fields
        (field (name "MANUFACTURER") "Bourns")
        (field (name "MANUFACTURER PART NUMBER") "PV36W102C01B00")
      )
      (libsource (lib "guitar tuner schematick") (part "PV36W102C01B00"))
    )
    (comp (ref "R23")
      (value "1k variable")
      (footprint "variablr resistor")
      (description "Cermet trimmer potentiometer, 25 turns, 1 kΩ, 0.5 W, THT, on top, PV36W102C01B00")
      (fields
        (field (name "MANUFACTURER") "Bourns")
        (field (name "MANUFACTURER PART NUMBER") "PV36W102C01B00")
      )
      (libsource (lib "guitar tuner schematick") (part "PV36W102C01B00"))
    )
    (comp (ref "R24")
      (value "CRGP0805F10K")
      (footprint "FP-CRGP0805-IPC_C")
      (description "CRGP 0805 10K 1%")
      (fields
        (field (name "MANUFACTURER") "TE")
        (field (name "ALTIUM_VALUE") "10KΩ")
        (field (name "OCTOPART") "https://octopart.com/crgp0805f10k-te+connectivity-91018782")
      )
      (libsource (lib "Altium Content Vault") (part "1029c3af85768c4190bb7ad29bc67b5"))
    )
    (comp (ref "R25")
      (value "CRGP0805F10K")
      (footprint "FP-CRGP0805-IPC_C")
      (description "CRGP 0805 10K 1%")
      (fields
        (field (name "MANUFACTURER") "TE")
        (field (name "ALTIUM_VALUE") "10KΩ")
        (field (name "OCTOPART") "https://octopart.com/crgp0805f10k-te+connectivity-91018782")
      )
      (libsource (lib "Altium Content Vault") (part "1029c3af85768c4190bb7ad29bc67b5"))
    )
    (comp (ref "R26")
      (value "CRGCQ0805F100K")
      (footprint "FP-CRGCQ0805-IPC_C")
      (description "CRGCQ 0805 100K 1%")
      (fields
        (field (name "MANUFACTURER") "TE Connectivity")
        (field (name "OCTOPART") "https://octopart.com/crgcq0805f100k-te+connectivity-91018138")
        (field (name "ALTIUM_VALUE") "100KΩ")
      )
      (libsource (lib "Altium Content Vault") (part "1029c3af85768c4190bb7ad29bc67b5"))
    )
    (comp (ref "R27")
      (value "RS02B12K00FE12")
      (footprint "FP-RS02B-MFG")
      (description "Res Wirewound 12K Ohm 1% 3W ±20ppm/°C Ceramic Hi Temp Sil AXL Thru-Hole Bulk")
      (fields (field (name "TOLERANCE") "1%"))
      (libsource (lib "Altium Content Vault") (part "1029c3af85768c4190bb7ad29bc67b5"))
    )
    (comp (ref "R28")
      (value "CRGP0805F10K")
      (footprint "FP-CRGP0805-IPC_C")
      (description "CRGP 0805 10K 1%")
      (fields
        (field (name "MANUFACTURER") "TE")
        (field (name "ALTIUM_VALUE") "10KΩ")
        (field (name "OCTOPART") "https://octopart.com/crgp0805f10k-te+connectivity-91018782")
      )
      (libsource (lib "Altium Content Vault") (part "1029c3af85768c4190bb7ad29bc67b5"))
    )
    (comp (ref "R29")
      (value "CRGP0805F10K")
      (footprint "FP-CRGP0805-IPC_C")
      (description "CRGP 0805 10K 1%")
      (fields
        (field (name "MANUFACTURER") "TE")
        (field (name "ALTIUM_VALUE") "10KΩ")
        (field (name "OCTOPART") "https://octopart.com/crgp0805f10k-te+connectivity-91018782")
      )
      (libsource (lib "Altium Content Vault") (part "1029c3af85768c4190bb7ad29bc67b5"))
    )
    (comp (ref "R30")
      (value "RMCF0805JG1K20")
      (footprint "FP-RMCF0805-IPC_A")
      (description "1.2kΩ ±5% 0.125W 0805 Thick Film Chip Resistor AEC-Q200 compliant")
      (fields (field (name "RESISTANCE") "1.2kR") (field (name "TOLERANCE") "5%"))
      (libsource (lib "Altium Content Vault") (part "1029c3af85768c4190bb7ad29bc67b5"))
    )
    (comp (ref "R31")
      (value "CRGCQ0805F100K")
      (footprint "FP-CRGCQ0805-IPC_C")
      (description "CRGCQ 0805 100K 1%")
      (fields
        (field (name "MANUFACTURER") "TE Connectivity")
        (field (name "OCTOPART") "https://octopart.com/crgcq0805f100k-te+connectivity-91018138")
        (field (name "ALTIUM_VALUE") "100KΩ")
      )
      (libsource (lib "Altium Content Vault") (part "1029c3af85768c4190bb7ad29bc67b5"))
    )
    (comp (ref "R32")
      (value "CRGP0805F470K")
      (footprint "FP-CRGP0805-IPC_C")
      (description "CRGP0805 470KΩ 0.33W ±100ppm/°C 1% 150V")
      (fields
        (field (name "ALTIUM_VALUE") "470KΩ")
        (field (name "MANUFACTURER") "TE")
        (field (name "TOLERANCE") "0.01")
      )
      (libsource (lib "Altium Content Vault") (part "1029c3af85768c4190bb7ad29bc67b5"))
    )
    (comp (ref "R33")
      (value "CRGCQ0805F100K")
      (footprint "FP-CRGCQ0805-IPC_C")
      (description "CRGCQ 0805 100K 1%")
      (fields
        (field (name "MANUFACTURER") "TE Connectivity")
        (field (name "OCTOPART") "https://octopart.com/crgcq0805f100k-te+connectivity-91018138")
        (field (name "ALTIUM_VALUE") "100KΩ")
      )
      (libsource (lib "Altium Content Vault") (part "1029c3af85768c4190bb7ad29bc67b5"))
    )
    (comp (ref "R34")
      (value "CRGP0805F10K")
      (footprint "FP-CRGP0805-IPC_C")
      (description "CRGP 0805 10K 1%")
      (fields
        (field (name "MANUFACTURER") "TE")
        (field (name "ALTIUM_VALUE") "10KΩ")
        (field (name "OCTOPART") "https://octopart.com/crgp0805f10k-te+connectivity-91018782")
      )
      (libsource (lib "Altium Content Vault") (part "1029c3af85768c4190bb7ad29bc67b5"))
    )
    (comp (ref "R35")
      (value "MCU08050D4701BP500")
      (footprint "FP-MCU0805-MFG")
      (description "RES 1.05K OHM 0.5% 1/5W 0805")
      (fields (field (name "TOLERANCE") "0.1%"))
      (libsource (lib "Altium Content Vault") (part "1029c3af85768c4190bb7ad29bc67b5"))
    )
    (comp (ref "R36")
      (value "AC0805FR-07820RL")
      (footprint "FP-AC0805-MFG")
      (description "RES SMD 820 OHM 1% 1/8W 0805")
      (fields
        (field (name "TOLERANCE") "0.01")
        (field (name "ALTIUM_VALUE") "820Ω")
        (field (name "OCTOPART") "https://octopart.com/ac0805fr-07820rl-yageo-26041182")
      )
      (libsource (lib "Altium Content Vault") (part "1029c3af85768c4190bb7ad29bc67b5"))
    )
    (comp (ref "R37")
      (value "MCU08050D2001BP500")
      (footprint "FP-MCU0805-IPC_A")
      (description "RES 1.05K OHM 0.5% 1/5W 0805")
      (fields (field (name "TOLERANCE") "0.1%") (field (name "RESISTANCE") "2kR"))
      (libsource (lib "Altium Content Vault") (part "1029c3af85768c4190bb7ad29bc67b5"))
    )
    (comp (ref "R38")
      (value "RMCF0805JT330R")
      (footprint "FP-RMCF0805-IPC_C")
      (description "330Ω ±5% 0.125W 0805 Thick Film Chip Resistor AEC-Q200 compliant")
      (fields (field (name "TOLERANCE") "5%") (field (name "RESISTANCE") "330R"))
      (libsource (lib "Altium Content Vault") (part "1029c3af85768c4190bb7ad29bc67b5"))
    )
    (comp (ref "R39")
      (value "CRGP0805F10K")
      (footprint "FP-CRGP0805-IPC_C")
      (description "CRGP 0805 10K 1%")
      (fields
        (field (name "MANUFACTURER") "TE")
        (field (name "ALTIUM_VALUE") "10KΩ")
        (field (name "OCTOPART") "https://octopart.com/crgp0805f10k-te+connectivity-91018782")
      )
      (libsource (lib "Altium Content Vault") (part "1029c3af85768c4190bb7ad29bc67b5"))
    )
    (comp (ref "R40")
      (value "MCU08050D2001BP500")
      (footprint "FP-MCU0805-IPC_A")
      (description "RES 1.05K OHM 0.5% 1/5W 0805")
      (fields (field (name "TOLERANCE") "0.1%") (field (name "RESISTANCE") "2kR"))
      (libsource (lib "Altium Content Vault") (part "1029c3af85768c4190bb7ad29bc67b5"))
    )
    (comp (ref "R41")
      (value "AC0805FR-07330RL")
      (footprint "FP-AC0805-MFG")
      (description "RES SMD 330 OHM 1% 1/8W 0805")
      (fields (field (name "MANUFACTURER") "Yageo") (field (name "TOLERANCE") "0.01"))
      (libsource (lib "Altium Content Vault") (part "1029c3af85768c4190bb7ad29bc67b5"))
    )
    (comp (ref "R42")
      (value "CRGP0805F10K")
      (footprint "FP-CRGP0805-IPC_C")
      (description "CRGP 0805 10K 1%")
      (fields
        (field (name "MANUFACTURER") "TE")
        (field (name "ALTIUM_VALUE") "10KΩ")
        (field (name "OCTOPART") "https://octopart.com/crgp0805f10k-te+connectivity-91018782")
      )
      (libsource (lib "Altium Content Vault") (part "1029c3af85768c4190bb7ad29bc67b5"))
    )
    (comp (ref "R43")
      (value "AC0805FR-07330RL")
      (footprint "FP-AC0805-MFG")
      (description "RES SMD 330 OHM 1% 1/8W 0805")
      (fields (field (name "MANUFACTURER") "Yageo") (field (name "TOLERANCE") "0.01"))
      (libsource (lib "Altium Content Vault") (part "1029c3af85768c4190bb7ad29bc67b5"))
    )
    (comp (ref "R44")
      (value "CRGCQ0805F100K")
      (footprint "FP-CRGCQ0805-IPC_C")
      (description "CRGCQ 0805 100K 1%")
      (fields
        (field (name "MANUFACTURER") "TE Connectivity")
        (field (name "OCTOPART") "https://octopart.com/crgcq0805f100k-te+connectivity-91018138")
        (field (name "ALTIUM_VALUE") "100KΩ")
      )
      (libsource (lib "Altium Content Vault") (part "1029c3af85768c4190bb7ad29bc67b5"))
    )
    (comp (ref "R45")
      (value "MCU08050C1203FP500 120K")
      (footprint "FP-MCU0805-IPC_A")
      (description "RES 1.05K OHM 0.5% 1/5W 0805")
      (fields (field (name "TOLERANCE") "1%"))
      (libsource (lib "Altium Content Vault") (part "1029c3af85768c4190bb7ad29bc67b5"))
    )
    (comp (ref "R46")
      (value "RN73R2ATTD1201B25 1.2K")
      (footprint "FP-RN73R2A-MFG")
      (description "1.2kΩ ±0.1% 0.125W, 1/8W Chip Resistor 0805 (2012 Metric) Moisture Resistant Thin Film")
      (libsource (lib "Altium Content Vault") (part "1029c3af85768c4190bb7ad29bc67b5"))
    )
    (comp (ref "R47")
      (value "RMCF0805JT820R")
      (footprint "FP-RMCF0805-IPC_C")
      (description "820Ω ±5% 0.125W 0805 Thick Film Chip Resistor AEC-Q200 compliant")
      (fields (field (name "TOLERANCE") "5%"))
      (libsource (lib "Altium Content Vault") (part "1029c3af85768c4190bb7ad29bc67b5"))
    )
    (comp (ref "R48")
      (value "RN73R2ATTD2102B25 21K")
      (footprint "FP-RN73R2A-IPC_A")
      (description "21kΩ ±0.1% 0.125W, 1/8W Chip Resistor 0805 (2012 Metric) Moisture Resistant Thin Film")
      (libsource (lib "Altium Content Vault") (part "1029c3af85768c4190bb7ad29bc67b5"))
    )
    (comp (ref "R49")
      (value "CRGP0805F10K")
      (footprint "FP-CRGP0805-IPC_C")
      (description "CRGP 0805 10K 1%")
      (fields
        (field (name "MANUFACTURER") "TE")
        (field (name "ALTIUM_VALUE") "10KΩ")
        (field (name "OCTOPART") "https://octopart.com/crgp0805f10k-te+connectivity-91018782")
      )
      (libsource (lib "Altium Content Vault") (part "1029c3af85768c4190bb7ad29bc67b5"))
    )
    (comp (ref "R50")
      (value "CRCW08055K00FKTA 5K")
      (footprint "RESC2013X50X30ML20T20")
      (fields (field (name "PART NUMBER") "CRCW08055K00FKTA") (field (name "MANUFACTURER") "Vishay Dale"))
      (libsource (lib "Altium Content Vault") (part "RES"))
    )
    (comp (ref "R51")
      (value "AC0805FR-07270KL 270K")
      (footprint "FP-AC0805-MFG")
      (description "RES SMD 270K OHM 1% 1/8W 0805")
      (fields
        (field (name "OCTOPART") "https://octopart.com/ac0805fr-07270kl-yageo-71367641")
        (field (name "TOLERANCE") "0.01")
      )
      (libsource (lib "Altium Content Vault") (part "1029c3af85768c4190bb7ad29bc67b5"))
    )
    (comp (ref "R52")
      (value "RN73R2ATTD2102B25 21K")
      (footprint "FP-RN73R2A-IPC_A")
      (description "21kΩ ±0.1% 0.125W, 1/8W Chip Resistor 0805 (2012 Metric) Moisture Resistant Thin Film")
      (libsource (lib "Altium Content Vault") (part "1029c3af85768c4190bb7ad29bc67b5"))
    )
    (comp (ref "R53")
      (value "MCU0805MD1201BP100")
      (footprint "FP-MCU0805-MFG")
      (description "RES 1.05K OHM 0.5% 1/5W 0805")
      (libsource (lib "Altium Content Vault") (part "1029c3af85768c4190bb7ad29bc67b5"))
    )
    (comp (ref "R54")
      (value "CRGP0805F10K")
      (footprint "FP-CRGP0805-IPC_C")
      (description "CRGP 0805 10K 1%")
      (fields
        (field (name "MANUFACTURER") "TE")
        (field (name "ALTIUM_VALUE") "10KΩ")
        (field (name "OCTOPART") "https://octopart.com/crgp0805f10k-te+connectivity-91018782")
      )
      (libsource (lib "Altium Content Vault") (part "1029c3af85768c4190bb7ad29bc67b5"))
    )
    (comp (ref "R55")
      (value "CRGP0805F10K")
      (footprint "FP-CRGP0805-IPC_C")
      (description "CRGP 0805 10K 1%")
      (fields
        (field (name "MANUFACTURER") "TE")
        (field (name "ALTIUM_VALUE") "10KΩ")
        (field (name "OCTOPART") "https://octopart.com/crgp0805f10k-te+connectivity-91018782")
      )
      (libsource (lib "Altium Content Vault") (part "1029c3af85768c4190bb7ad29bc67b5"))
    )
    (comp (ref "R56")
      (value "CRGP0805F10K")
      (footprint "FP-CRGP0805-IPC_C")
      (description "CRGP 0805 10K 1%")
      (fields
        (field (name "MANUFACTURER") "TE")
        (field (name "ALTIUM_VALUE") "10KΩ")
        (field (name "OCTOPART") "https://octopart.com/crgp0805f10k-te+connectivity-91018782")
      )
      (libsource (lib "Altium Content Vault") (part "1029c3af85768c4190bb7ad29bc67b5"))
    )
    (comp (ref "R57")
      (value "RMCF0805JT220R")
      (footprint "FP-RMCF0805-IPC_A")
      (description "220Ω ±5% 0.125W 0805 Thick Film Chip Resistor AEC-Q200 compliant")
      (fields (field (name "TOLERANCE") "5%"))
      (libsource (lib "Altium Content Vault") (part "1029c3af85768c4190bb7ad29bc67b5"))
    )
    (comp (ref "R58")
      (value "CRGP0805F10K")
      (footprint "FP-CRGP0805-IPC_C")
      (description "CRGP 0805 10K 1%")
      (fields
        (field (name "MANUFACTURER") "TE")
        (field (name "ALTIUM_VALUE") "10KΩ")
        (field (name "OCTOPART") "https://octopart.com/crgp0805f10k-te+connectivity-91018782")
      )
      (libsource (lib "Altium Content Vault") (part "1029c3af85768c4190bb7ad29bc67b5"))
    )
    (comp (ref "R59")
      (value "CRCW08055K00FKTA 5K")
      (footprint "RESC2013X50X30ML20T20")
      (fields (field (name "PART NUMBER") "CRCW08055K00FKTA") (field (name "MANUFACTURER") "Vishay Dale"))
      (libsource (lib "Altium Content Vault") (part "RES"))
    )
    (comp (ref "R60")
      (value "AC0805FR-07390KL")
      (footprint "FP-AC0805-MFG")
      (description "RES SMD 390K OHM 1% 1/8W 0805")
      (fields (field (name "TOLERANCE") "0.01") (field (name "MANUFACTURER") "Yageo"))
      (libsource (lib "Altium Content Vault") (part "1029c3af85768c4190bb7ad29bc67b5"))
    )
    (comp (ref "R61")
      (value "CRGP0805F10K")
      (footprint "FP-CRGP0805-IPC_C")
      (description "CRGP 0805 10K 1%")
      (fields
        (field (name "MANUFACTURER") "TE")
        (field (name "ALTIUM_VALUE") "10KΩ")
        (field (name "OCTOPART") "https://octopart.com/crgp0805f10k-te+connectivity-91018782")
      )
      (libsource (lib "Altium Content Vault") (part "1029c3af85768c4190bb7ad29bc67b5"))
    )
    (comp (ref "R62")
      (value "RMCF0805JT820R")
      (footprint "FP-RMCF0805-IPC_C")
      (description "820Ω ±5% 0.125W 0805 Thick Film Chip Resistor AEC-Q200 compliant")
      (fields (field (name "TOLERANCE") "5%"))
      (libsource (lib "Altium Content Vault") (part "1029c3af85768c4190bb7ad29bc67b5"))
    )
    (comp (ref "R63")
      (value "CRGCQ0805F100K")
      (footprint "FP-CRGCQ0805-IPC_C")
      (description "CRGCQ 0805 100K 1%")
      (fields
        (field (name "MANUFACTURER") "TE Connectivity")
        (field (name "OCTOPART") "https://octopart.com/crgcq0805f100k-te+connectivity-91018138")
        (field (name "ALTIUM_VALUE") "100KΩ")
      )
      (libsource (lib "Altium Content Vault") (part "1029c3af85768c4190bb7ad29bc67b5"))
    )
    (comp (ref "R64")
      (value "CRGCQ0805F100K")
      (footprint "FP-CRGCQ0805-IPC_C")
      (description "CRGCQ 0805 100K 1%")
      (fields
        (field (name "MANUFACTURER") "TE Connectivity")
        (field (name "OCTOPART") "https://octopart.com/crgcq0805f100k-te+connectivity-91018138")
        (field (name "ALTIUM_VALUE") "100KΩ")
      )
      (libsource (lib "Altium Content Vault") (part "1029c3af85768c4190bb7ad29bc67b5"))
    )
    (comp (ref "R65")
      (value "CRGCQ0805F330K")
      (footprint "FP-CRGCQ0805-IPC_C")
      (description "CRGCQ0805 330KΩ 0.125W ±100ppm/°C 1% 150V")
      (fields
        (field (name "OCTOPART") "https://octopart.com/crgcq0805f330k-te+connectivity-91018169")
        (field (name "TOLERANCE") "0.01")
      )
      (libsource (lib "Altium Content Vault") (part "1029c3af85768c4190bb7ad29bc67b5"))
    )
    (comp (ref "R66")
      (value "AC0805FR-07270KL 270K")
      (footprint "FP-AC0805-MFG")
      (description "RES SMD 270K OHM 1% 1/8W 0805")
      (fields
        (field (name "OCTOPART") "https://octopart.com/ac0805fr-07270kl-yageo-71367641")
        (field (name "TOLERANCE") "0.01")
      )
      (libsource (lib "Altium Content Vault") (part "1029c3af85768c4190bb7ad29bc67b5"))
    )
    (comp (ref "R67")
      (value "CRGCQ0805F100K")
      (footprint "FP-CRGCQ0805-IPC_C")
      (description "CRGCQ 0805 100K 1%")
      (fields
        (field (name "MANUFACTURER") "TE Connectivity")
        (field (name "OCTOPART") "https://octopart.com/crgcq0805f100k-te+connectivity-91018138")
        (field (name "ALTIUM_VALUE") "100KΩ")
      )
      (libsource (lib "Altium Content Vault") (part "1029c3af85768c4190bb7ad29bc67b5"))
    )
    (comp (ref "R68")
      (value "CRGP0805F10K")
      (footprint "FP-CRGP0805-IPC_C")
      (description "CRGP 0805 10K 1%")
      (fields
        (field (name "MANUFACTURER") "TE")
        (field (name "ALTIUM_VALUE") "10KΩ")
        (field (name "OCTOPART") "https://octopart.com/crgp0805f10k-te+connectivity-91018782")
      )
      (libsource (lib "Altium Content Vault") (part "1029c3af85768c4190bb7ad29bc67b5"))
    )
    (comp (ref "R69")
      (value "CRGCQ0805F100K")
      (footprint "FP-CRGCQ0805-IPC_C")
      (description "CRGCQ 0805 100K 1%")
      (fields
        (field (name "MANUFACTURER") "TE Connectivity")
        (field (name "OCTOPART") "https://octopart.com/crgcq0805f100k-te+connectivity-91018138")
        (field (name "ALTIUM_VALUE") "100KΩ")
      )
      (libsource (lib "Altium Content Vault") (part "1029c3af85768c4190bb7ad29bc67b5"))
    )
    (comp (ref "R70")
      (value "CRGCQ0805F100K")
      (footprint "FP-CRGCQ0805-IPC_C")
      (description "CRGCQ 0805 100K 1%")
      (fields
        (field (name "MANUFACTURER") "TE Connectivity")
        (field (name "OCTOPART") "https://octopart.com/crgcq0805f100k-te+connectivity-91018138")
        (field (name "ALTIUM_VALUE") "100KΩ")
      )
      (libsource (lib "Altium Content Vault") (part "1029c3af85768c4190bb7ad29bc67b5"))
    )
    (comp (ref "R71")
      (value "CRGCQ0805F330K")
      (footprint "FP-CRGCQ0805-IPC_C")
      (description "CRGCQ0805 330KΩ 0.125W ±100ppm/°C 1% 150V")
      (fields
        (field (name "OCTOPART") "https://octopart.com/crgcq0805f330k-te+connectivity-91018169")
        (field (name "TOLERANCE") "0.01")
      )
      (libsource (lib "Altium Content Vault") (part "1029c3af85768c4190bb7ad29bc67b5"))
    )
    (comp (ref "R72")
      (value "CRGCQ0805F330K")
      (footprint "FP-CRGCQ0805-IPC_C")
      (description "CRGCQ0805 330KΩ 0.125W ±100ppm/°C 1% 150V")
      (fields
        (field (name "OCTOPART") "https://octopart.com/crgcq0805f330k-te+connectivity-91018169")
        (field (name "TOLERANCE") "0.01")
      )
      (libsource (lib "Altium Content Vault") (part "1029c3af85768c4190bb7ad29bc67b5"))
    )
    (comp (ref "R73")
      (value "RMCF0805JT220R")
      (footprint "FP-RMCF0805-IPC_A")
      (description "220Ω ±5% 0.125W 0805 Thick Film Chip Resistor AEC-Q200 compliant")
      (fields (field (name "TOLERANCE") "5%"))
      (libsource (lib "Altium Content Vault") (part "1029c3af85768c4190bb7ad29bc67b5"))
    )
    (comp (ref "R75")
      (value "CRGP0805F10K")
      (footprint "FP-CRGP0805-IPC_C")
      (description "CRGP 0805 10K 1%")
      (fields
        (field (name "MANUFACTURER") "TE")
        (field (name "ALTIUM_VALUE") "10KΩ")
        (field (name "OCTOPART") "https://octopart.com/crgp0805f10k-te+connectivity-91018782")
      )
      (libsource (lib "Altium Content Vault") (part "1029c3af85768c4190bb7ad29bc67b5"))
    )
    (comp (ref "R76")
      (value "CRGP0805F10K")
      (footprint "FP-CRGP0805-IPC_C")
      (description "CRGP 0805 10K 1%")
      (fields
        (field (name "MANUFACTURER") "TE")
        (field (name "ALTIUM_VALUE") "10KΩ")
        (field (name "OCTOPART") "https://octopart.com/crgp0805f10k-te+connectivity-91018782")
      )
      (libsource (lib "Altium Content Vault") (part "1029c3af85768c4190bb7ad29bc67b5"))
    )
    (comp (ref "R77")
      (value "CRCW08055K00FKTA")
      (footprint "RESC2013X50X30ML20T20")
      (fields (field (name "MANUFACTURER") "Vishay Dale"))
      (libsource (lib "Altium Content Vault") (part "RES"))
    )
    (comp (ref "R78")
      (value "RN73R2ATTD2102B25 21K")
      (footprint "FP-RN73R2A-IPC_A")
      (description "21kΩ ±0.1% 0.125W, 1/8W Chip Resistor 0805 (2012 Metric) Moisture Resistant Thin Film")
      (libsource (lib "Altium Content Vault") (part "1029c3af85768c4190bb7ad29bc67b5"))
    )
    (comp (ref "R79")
      (value "RN73R2ATTD2102B25 21K")
      (footprint "FP-RN73R2A-IPC_A")
      (description "21kΩ ±0.1% 0.125W, 1/8W Chip Resistor 0805 (2012 Metric) Moisture Resistant Thin Film")
      (libsource (lib "Altium Content Vault") (part "1029c3af85768c4190bb7ad29bc67b5"))
    )
    (comp (ref "R80")
      (value "MCR10EZPJ122")
      (footprint "FP-MCR10-IPC_C")
      (description "Thick Film Chip Resistor, 0805, 1.2kΩ, 5%, 200ppm/°C, 0.125W, 150V")
      (fields (field (name "TOLERANCE") "5%"))
      (libsource (lib "Altium Content Vault") (part "1029c3af85768c4190bb7ad29bc67b5"))
    )
    (comp (ref "R81")
      (value "RN73R2ATTD2102B25 21K")
      (footprint "FP-RN73R2A-IPC_A")
      (description "21kΩ ±0.1% 0.125W, 1/8W Chip Resistor 0805 (2012 Metric) Moisture Resistant Thin Film")
      (libsource (lib "Altium Content Vault") (part "1029c3af85768c4190bb7ad29bc67b5"))
    )
    (comp (ref "R82")
      (value "0603_10ohm")
      (footprint "FP-MCT0603-IPC_A")
      (description "RES SMD 100 OHM 1% 1/8W 0603")
      (fields (field (name "TOLERANCE") "0.1%"))
      (libsource (lib "Altium Content Vault") (part "1029c3af85768c4190bb7ad29bc67b5"))
    )
    (comp (ref "R83")
      (value "0603_10ohm")
      (footprint "FP-MCT0603-IPC_A")
      (description "RES SMD 100 OHM 1% 1/8W 0603")
      (fields (field (name "TOLERANCE") "0.1%"))
      (libsource (lib "Altium Content Vault") (part "1029c3af85768c4190bb7ad29bc67b5"))
    )
    (comp (ref "R84")
      (value "0603_10ohm")
      (footprint "FP-MCT0603-IPC_A")
      (description "RES SMD 100 OHM 1% 1/8W 0603")
      (fields (field (name "TOLERANCE") "0.1%"))
      (libsource (lib "Altium Content Vault") (part "1029c3af85768c4190bb7ad29bc67b5"))
    )
    (comp (ref "R85")
      (value "0603_10ohm")
      (footprint "FP-MCT0603-IPC_A")
      (description "RES SMD 100 OHM 1% 1/8W 0603")
      (fields (field (name "TOLERANCE") "0.1%"))
      (libsource (lib "Altium Content Vault") (part "1029c3af85768c4190bb7ad29bc67b5"))
    )
    (comp (ref "R86")
      (value "0603_10ohm")
      (footprint "FP-MCT0603-IPC_A")
      (description "RES SMD 100 OHM 1% 1/8W 0603")
      (fields (field (name "TOLERANCE") "0.1%"))
      (libsource (lib "Altium Content Vault") (part "1029c3af85768c4190bb7ad29bc67b5"))
    )
    (comp (ref "R87")
      (value "0603_10ohm")
      (footprint "FP-MCT0603-IPC_A")
      (description "RES SMD 100 OHM 1% 1/8W 0603")
      (fields (field (name "TOLERANCE") "0.1%"))
      (libsource (lib "Altium Content Vault") (part "1029c3af85768c4190bb7ad29bc67b5"))
    )
    (comp (ref "R88")
      (value "0603_10ohm")
      (footprint "FP-MCT0603-IPC_A")
      (description "RES SMD 100 OHM 1% 1/8W 0603")
      (fields (field (name "TOLERANCE") "0.1%"))
      (libsource (lib "Altium Content Vault") (part "1029c3af85768c4190bb7ad29bc67b5"))
    )
    (comp (ref "R89")
      (value "0603_10ohm")
      (footprint "FP-MCT0603-IPC_A")
      (description "RES SMD 100 OHM 1% 1/8W 0603")
      (fields (field (name "TOLERANCE") "0.1%"))
      (libsource (lib "Altium Content Vault") (part "1029c3af85768c4190bb7ad29bc67b5"))
    )
    (comp (ref "R90")
      (value "0603_10ohm")
      (footprint "FP-MCT0603-IPC_A")
      (description "RES SMD 100 OHM 1% 1/8W 0603")
      (fields (field (name "TOLERANCE") "0.1%"))
      (libsource (lib "Altium Content Vault") (part "1029c3af85768c4190bb7ad29bc67b5"))
    )
    (comp (ref "R91")
      (value "0603_10ohm")
      (footprint "FP-MCT0603-IPC_A")
      (description "RES SMD 100 OHM 1% 1/8W 0603")
      (fields (field (name "TOLERANCE") "0.1%"))
      (libsource (lib "Altium Content Vault") (part "1029c3af85768c4190bb7ad29bc67b5"))
    )
    (comp (ref "R92")
      (value "0603_10ohm")
      (footprint "FP-MCT0603-IPC_A")
      (description "RES SMD 100 OHM 1% 1/8W 0603")
      (fields (field (name "TOLERANCE") "0.1%"))
      (libsource (lib "Altium Content Vault") (part "1029c3af85768c4190bb7ad29bc67b5"))
    )
    (comp (ref "R93")
      (value "0603_10ohm")
      (footprint "FP-MCT0603-IPC_A")
      (description "RES SMD 100 OHM 1% 1/8W 0603")
      (fields (field (name "TOLERANCE") "0.1%"))
      (libsource (lib "Altium Content Vault") (part "1029c3af85768c4190bb7ad29bc67b5"))
    )
    (comp (ref "R94")
      (value "0603_10ohm")
      (footprint "FP-MCT0603-IPC_A")
      (description "RES SMD 100 OHM 1% 1/8W 0603")
      (fields (field (name "TOLERANCE") "0.1%"))
      (libsource (lib "Altium Content Vault") (part "1029c3af85768c4190bb7ad29bc67b5"))
    )
    (comp (ref "R95")
      (value "0603_10ohm")
      (footprint "FP-MCT0603-IPC_A")
      (description "RES SMD 100 OHM 1% 1/8W 0603")
      (fields (field (name "TOLERANCE") "0.1%"))
      (libsource (lib "Altium Content Vault") (part "1029c3af85768c4190bb7ad29bc67b5"))
    )
    (comp (ref "R96")
      (value "0603_10ohm")
      (footprint "FP-MCT0603-IPC_A")
      (description "RES SMD 100 OHM 1% 1/8W 0603")
      (fields (field (name "TOLERANCE") "0.1%"))
      (libsource (lib "Altium Content Vault") (part "1029c3af85768c4190bb7ad29bc67b5"))
    )
    (comp (ref "R97")
      (value "0603_10ohm")
      (footprint "FP-MCT0603-IPC_A")
      (description "RES SMD 100 OHM 1% 1/8W 0603")
      (fields (field (name "TOLERANCE") "0.1%"))
      (libsource (lib "Altium Content Vault") (part "1029c3af85768c4190bb7ad29bc67b5"))
    )
    (comp (ref "R98")
      (value "0603_10ohm")
      (footprint "FP-MCT0603-IPC_A")
      (description "RES SMD 100 OHM 1% 1/8W 0603")
      (fields (field (name "TOLERANCE") "0.1%"))
      (libsource (lib "Altium Content Vault") (part "1029c3af85768c4190bb7ad29bc67b5"))
    )
    (comp (ref "R99")
      (value "0603_10ohm")
      (footprint "FP-MCT0603-IPC_A")
      (description "RES SMD 100 OHM 1% 1/8W 0603")
      (fields (field (name "TOLERANCE") "0.1%"))
      (libsource (lib "Altium Content Vault") (part "1029c3af85768c4190bb7ad29bc67b5"))
    )
    (comp (ref "R100")
      (value "0603_10ohm")
      (footprint "FP-MCT0603-IPC_A")
      (description "RES SMD 100 OHM 1% 1/8W 0603")
      (fields (field (name "TOLERANCE") "0.1%"))
      (libsource (lib "Altium Content Vault") (part "1029c3af85768c4190bb7ad29bc67b5"))
    )
    (comp (ref "R101")
      (value "0603_10ohm")
      (footprint "FP-MCT0603-IPC_A")
      (description "RES SMD 100 OHM 1% 1/8W 0603")
      (fields (field (name "TOLERANCE") "0.1%"))
      (libsource (lib "Altium Content Vault") (part "1029c3af85768c4190bb7ad29bc67b5"))
    )
    (comp (ref "R102")
      (value "0603_10ohm")
      (footprint "FP-MCT0603-IPC_A")
      (description "RES SMD 100 OHM 1% 1/8W 0603")
      (fields (field (name "TOLERANCE") "0.1%"))
      (libsource (lib "Altium Content Vault") (part "1029c3af85768c4190bb7ad29bc67b5"))
    )
    (comp (ref "R103")
      (value "0603_10ohm")
      (footprint "FP-MCT0603-IPC_A")
      (description "RES SMD 100 OHM 1% 1/8W 0603")
      (fields (field (name "TOLERANCE") "0.1%"))
      (libsource (lib "Altium Content Vault") (part "1029c3af85768c4190bb7ad29bc67b5"))
    )
    (comp (ref "R104")
      (value "0603_10ohm")
      (footprint "FP-MCT0603-IPC_A")
      (description "RES SMD 100 OHM 1% 1/8W 0603")
      (fields (field (name "TOLERANCE") "0.1%"))
      (libsource (lib "Altium Content Vault") (part "1029c3af85768c4190bb7ad29bc67b5"))
    )
    (comp (ref "R105")
      (value "0603_10ohm")
      (footprint "FP-MCT0603-IPC_A")
      (description "RES SMD 100 OHM 1% 1/8W 0603")
      (fields (field (name "TOLERANCE") "0.1%"))
      (libsource (lib "Altium Content Vault") (part "1029c3af85768c4190bb7ad29bc67b5"))
    )
    (comp (ref "R106")
      (value "0603_10ohm")
      (footprint "FP-MCT0603-IPC_A")
      (description "RES SMD 100 OHM 1% 1/8W 0603")
      (fields (field (name "TOLERANCE") "0.1%"))
      (libsource (lib "Altium Content Vault") (part "1029c3af85768c4190bb7ad29bc67b5"))
    )
    (comp (ref "R107")
      (value "0603_10ohm")
      (footprint "FP-MCT0603-IPC_A")
      (description "RES SMD 100 OHM 1% 1/8W 0603")
      (fields (field (name "TOLERANCE") "0.1%"))
      (libsource (lib "Altium Content Vault") (part "1029c3af85768c4190bb7ad29bc67b5"))
    )
    (comp (ref "R108")
      (value "0603_10ohm")
      (footprint "FP-MCT0603-IPC_A")
      (description "RES SMD 100 OHM 1% 1/8W 0603")
      (fields (field (name "TOLERANCE") "0.1%"))
      (libsource (lib "Altium Content Vault") (part "1029c3af85768c4190bb7ad29bc67b5"))
    )
    (comp (ref "R109")
      (value "0603_10ohm")
      (footprint "FP-MCT0603-IPC_A")
      (description "RES SMD 100 OHM 1% 1/8W 0603")
      (fields (field (name "TOLERANCE") "0.1%"))
      (libsource (lib "Altium Content Vault") (part "1029c3af85768c4190bb7ad29bc67b5"))
    )
    (comp (ref "R110")
      (value "0603_10ohm")
      (footprint "FP-MCT0603-IPC_A")
      (description "RES SMD 100 OHM 1% 1/8W 0603")
      (fields (field (name "TOLERANCE") "0.1%"))
      (libsource (lib "Altium Content Vault") (part "1029c3af85768c4190bb7ad29bc67b5"))
    )
    (comp (ref "R111")
      (value "0603_10ohm")
      (footprint "FP-MCT0603-IPC_A")
      (description "RES SMD 100 OHM 1% 1/8W 0603")
      (fields (field (name "TOLERANCE") "0.1%"))
      (libsource (lib "Altium Content Vault") (part "1029c3af85768c4190bb7ad29bc67b5"))
    )
    (comp (ref "R112")
      (value "0603_10ohm")
      (footprint "FP-MCT0603-IPC_A")
      (description "RES SMD 100 OHM 1% 1/8W 0603")
      (fields (field (name "TOLERANCE") "0.1%"))
      (libsource (lib "Altium Content Vault") (part "1029c3af85768c4190bb7ad29bc67b5"))
    )
    (comp (ref "R113")
      (value "0603_10ohm")
      (footprint "FP-MCT0603-IPC_A")
      (description "RES SMD 100 OHM 1% 1/8W 0603")
      (fields (field (name "TOLERANCE") "0.1%"))
      (libsource (lib "Altium Content Vault") (part "1029c3af85768c4190bb7ad29bc67b5"))
    )
    (comp (ref "R114")
      (value "0603_10ohm")
      (footprint "FP-MCT0603-IPC_A")
      (description "RES SMD 100 OHM 1% 1/8W 0603")
      (fields (field (name "TOLERANCE") "0.1%"))
      (libsource (lib "Altium Content Vault") (part "1029c3af85768c4190bb7ad29bc67b5"))
    )
    (comp (ref "R115")
      (value "0603_10ohm")
      (footprint "FP-MCT0603-IPC_A")
      (description "RES SMD 100 OHM 1% 1/8W 0603")
      (fields (field (name "TOLERANCE") "0.1%"))
      (libsource (lib "Altium Content Vault") (part "1029c3af85768c4190bb7ad29bc67b5"))
    )
    (comp (ref "R116")
      (value "0603_10ohm")
      (footprint "FP-MCT0603-IPC_A")
      (description "RES SMD 100 OHM 1% 1/8W 0603")
      (fields (field (name "TOLERANCE") "0.1%"))
      (libsource (lib "Altium Content Vault") (part "1029c3af85768c4190bb7ad29bc67b5"))
    )
    (comp (ref "R117")
      (value "0603_10ohm")
      (footprint "FP-MCT0603-IPC_A")
      (description "RES SMD 100 OHM 1% 1/8W 0603")
      (fields (field (name "TOLERANCE") "0.1%"))
      (libsource (lib "Altium Content Vault") (part "1029c3af85768c4190bb7ad29bc67b5"))
    )
    (comp (ref "R118")
      (value "0603_10ohm")
      (footprint "FP-MCT0603-IPC_A")
      (description "RES SMD 100 OHM 1% 1/8W 0603")
      (fields (field (name "TOLERANCE") "0.1%"))
      (libsource (lib "Altium Content Vault") (part "1029c3af85768c4190bb7ad29bc67b5"))
    )
    (comp (ref "R119")
      (value "0603_10ohm")
      (footprint "FP-MCT0603-IPC_A")
      (description "RES SMD 100 OHM 1% 1/8W 0603")
      (fields (field (name "TOLERANCE") "0.1%"))
      (libsource (lib "Altium Content Vault") (part "1029c3af85768c4190bb7ad29bc67b5"))
    )
    (comp (ref "R120")
      (value "0603_10ohm")
      (footprint "FP-MCT0603-IPC_A")
      (description "RES SMD 100 OHM 1% 1/8W 0603")
      (fields (field (name "TOLERANCE") "0.1%"))
      (libsource (lib "Altium Content Vault") (part "1029c3af85768c4190bb7ad29bc67b5"))
    )
    (comp (ref "R121")
      (value "0603_10ohm")
      (footprint "FP-MCT0603-IPC_A")
      (description "RES SMD 100 OHM 1% 1/8W 0603")
      (fields (field (name "TOLERANCE") "0.1%"))
      (libsource (lib "Altium Content Vault") (part "1029c3af85768c4190bb7ad29bc67b5"))
    )
    (comp (ref "R122")
      (value "0603_10ohm")
      (footprint "FP-MCT0603-IPC_A")
      (description "RES SMD 100 OHM 1% 1/8W 0603")
      (fields (field (name "TOLERANCE") "0.1%"))
      (libsource (lib "Altium Content Vault") (part "1029c3af85768c4190bb7ad29bc67b5"))
    )
    (comp (ref "R123")
      (value "0603_10ohm")
      (footprint "FP-MCT0603-IPC_A")
      (description "RES SMD 100 OHM 1% 1/8W 0603")
      (fields (field (name "TOLERANCE") "0.1%"))
      (libsource (lib "Altium Content Vault") (part "1029c3af85768c4190bb7ad29bc67b5"))
    )
    (comp (ref "R124")
      (value "0603_10ohm")
      (footprint "FP-MCT0603-IPC_A")
      (description "RES SMD 100 OHM 1% 1/8W 0603")
      (fields (field (name "TOLERANCE") "0.1%"))
      (libsource (lib "Altium Content Vault") (part "1029c3af85768c4190bb7ad29bc67b5"))
    )
    (comp (ref "R125")
      (value "0603_10ohm")
      (footprint "FP-MCT0603-IPC_A")
      (description "RES SMD 100 OHM 1% 1/8W 0603")
      (fields (field (name "TOLERANCE") "0.1%"))
      (libsource (lib "Altium Content Vault") (part "1029c3af85768c4190bb7ad29bc67b5"))
    )
    (comp (ref "R126")
      (value "0603_10ohm")
      (footprint "FP-MCT0603-IPC_A")
      (description "RES SMD 100 OHM 1% 1/8W 0603")
      (fields (field (name "TOLERANCE") "0.1%"))
      (libsource (lib "Altium Content Vault") (part "1029c3af85768c4190bb7ad29bc67b5"))
    )
    (comp (ref "R127")
      (value "0603_10ohm")
      (footprint "FP-MCT0603-IPC_A")
      (description "RES SMD 100 OHM 1% 1/8W 0603")
      (fields (field (name "TOLERANCE") "0.1%"))
      (libsource (lib "Altium Content Vault") (part "1029c3af85768c4190bb7ad29bc67b5"))
    )
    (comp (ref "R128")
      (value "0603_10ohm")
      (footprint "FP-MCT0603-IPC_A")
      (description "RES SMD 100 OHM 1% 1/8W 0603")
      (fields (field (name "TOLERANCE") "0.1%"))
      (libsource (lib "Altium Content Vault") (part "1029c3af85768c4190bb7ad29bc67b5"))
    )
    (comp (ref "R129")
      (value "0603_10ohm")
      (footprint "FP-MCT0603-IPC_A")
      (description "RES SMD 100 OHM 1% 1/8W 0603")
      (fields (field (name "TOLERANCE") "0.1%"))
      (libsource (lib "Altium Content Vault") (part "1029c3af85768c4190bb7ad29bc67b5"))
    )
    (comp (ref "R130")
      (value "0603_10ohm")
      (footprint "FP-MCT0603-IPC_A")
      (description "RES SMD 100 OHM 1% 1/8W 0603")
      (fields (field (name "TOLERANCE") "0.1%"))
      (libsource (lib "Altium Content Vault") (part "1029c3af85768c4190bb7ad29bc67b5"))
    )
    (comp (ref "R131")
      (value "0603_10ohm")
      (footprint "FP-MCT0603-IPC_A")
      (description "RES SMD 100 OHM 1% 1/8W 0603")
      (fields (field (name "TOLERANCE") "0.1%"))
      (libsource (lib "Altium Content Vault") (part "1029c3af85768c4190bb7ad29bc67b5"))
    )
    (comp (ref "R132")
      (value "0603_10ohm")
      (footprint "FP-MCT0603-IPC_A")
      (description "RES SMD 100 OHM 1% 1/8W 0603")
      (fields (field (name "TOLERANCE") "0.1%"))
      (libsource (lib "Altium Content Vault") (part "1029c3af85768c4190bb7ad29bc67b5"))
    )
    (comp (ref "R133")
      (value "0603_10ohm")
      (footprint "FP-MCT0603-IPC_A")
      (description "RES SMD 100 OHM 1% 1/8W 0603")
      (fields (field (name "TOLERANCE") "0.1%"))
      (libsource (lib "Altium Content Vault") (part "1029c3af85768c4190bb7ad29bc67b5"))
    )
    (comp (ref "R134")
      (value "0603_10ohm")
      (footprint "FP-MCT0603-IPC_A")
      (description "RES SMD 100 OHM 1% 1/8W 0603")
      (fields (field (name "TOLERANCE") "0.1%"))
      (libsource (lib "Altium Content Vault") (part "1029c3af85768c4190bb7ad29bc67b5"))
    )
    (comp (ref "R135")
      (value "0603_10ohm")
      (footprint "FP-MCT0603-IPC_A")
      (description "RES SMD 100 OHM 1% 1/8W 0603")
      (fields (field (name "TOLERANCE") "0.1%"))
      (libsource (lib "Altium Content Vault") (part "1029c3af85768c4190bb7ad29bc67b5"))
    )
    (comp (ref "R136")
      (value "0603_10ohm")
      (footprint "FP-MCT0603-IPC_A")
      (description "RES SMD 100 OHM 1% 1/8W 0603")
      (fields (field (name "TOLERANCE") "0.1%"))
      (libsource (lib "Altium Content Vault") (part "1029c3af85768c4190bb7ad29bc67b5"))
    )
    (comp (ref "R137")
      (value "0603_10ohm")
      (footprint "FP-MCT0603-IPC_A")
      (description "RES SMD 100 OHM 1% 1/8W 0603")
      (fields (field (name "TOLERANCE") "0.1%"))
      (libsource (lib "Altium Content Vault") (part "1029c3af85768c4190bb7ad29bc67b5"))
    )
    (comp (ref "R138")
      (value "0603_10ohm")
      (footprint "FP-MCT0603-IPC_A")
      (description "RES SMD 100 OHM 1% 1/8W 0603")
      (fields (field (name "TOLERANCE") "0.1%"))
      (libsource (lib "Altium Content Vault") (part "1029c3af85768c4190bb7ad29bc67b5"))
    )
    (comp (ref "R139")
      (value "0603_10ohm")
      (footprint "FP-MCT0603-IPC_A")
      (description "RES SMD 100 OHM 1% 1/8W 0603")
      (fields (field (name "TOLERANCE") "0.1%"))
      (libsource (lib "Altium Content Vault") (part "1029c3af85768c4190bb7ad29bc67b5"))
    )
    (comp (ref "R140")
      (value "0603_10ohm")
      (footprint "FP-MCT0603-IPC_A")
      (description "RES SMD 100 OHM 1% 1/8W 0603")
      (fields (field (name "TOLERANCE") "0.1%"))
      (libsource (lib "Altium Content Vault") (part "1029c3af85768c4190bb7ad29bc67b5"))
    )
    (comp (ref "R141")
      (value "0603_10ohm")
      (footprint "FP-MCT0603-IPC_A")
      (description "RES SMD 100 OHM 1% 1/8W 0603")
      (fields (field (name "TOLERANCE") "0.1%"))
      (libsource (lib "Altium Content Vault") (part "1029c3af85768c4190bb7ad29bc67b5"))
    )
    (comp (ref "R142")
      (value "0603_10ohm")
      (footprint "FP-MCT0603-IPC_A")
      (description "RES SMD 100 OHM 1% 1/8W 0603")
      (fields (field (name "TOLERANCE") "0.1%"))
      (libsource (lib "Altium Content Vault") (part "1029c3af85768c4190bb7ad29bc67b5"))
    )
    (comp (ref "R143")
      (value "0603_10ohm")
      (footprint "FP-MCT0603-IPC_A")
      (description "RES SMD 100 OHM 1% 1/8W 0603")
      (fields (field (name "TOLERANCE") "0.1%"))
      (libsource (lib "Altium Content Vault") (part "1029c3af85768c4190bb7ad29bc67b5"))
    )
    (comp (ref "R144")
      (value "0603_10ohm")
      (footprint "FP-MCT0603-IPC_A")
      (description "RES SMD 100 OHM 1% 1/8W 0603")
      (fields (field (name "TOLERANCE") "0.1%"))
      (libsource (lib "Altium Content Vault") (part "1029c3af85768c4190bb7ad29bc67b5"))
    )
    (comp (ref "R145")
      (value "0603_10ohm")
      (footprint "FP-MCT0603-IPC_A")
      (description "RES SMD 100 OHM 1% 1/8W 0603")
      (fields (field (name "TOLERANCE") "0.1%"))
      (libsource (lib "Altium Content Vault") (part "1029c3af85768c4190bb7ad29bc67b5"))
    )
    (comp (ref "R146")
      (value "0603_10ohm")
      (footprint "FP-MCT0603-IPC_A")
      (description "RES SMD 100 OHM 1% 1/8W 0603")
      (fields (field (name "TOLERANCE") "0.1%"))
      (libsource (lib "Altium Content Vault") (part "1029c3af85768c4190bb7ad29bc67b5"))
    )
    (comp (ref "R147")
      (value "0603_10ohm")
      (footprint "FP-MCT0603-IPC_A")
      (description "RES SMD 100 OHM 1% 1/8W 0603")
      (fields (field (name "TOLERANCE") "0.1%"))
      (libsource (lib "Altium Content Vault") (part "1029c3af85768c4190bb7ad29bc67b5"))
    )
    (comp (ref "R148")
      (value "0603_10ohm")
      (footprint "FP-MCT0603-IPC_A")
      (description "RES SMD 100 OHM 1% 1/8W 0603")
      (fields (field (name "TOLERANCE") "0.1%"))
      (libsource (lib "Altium Content Vault") (part "1029c3af85768c4190bb7ad29bc67b5"))
    )
    (comp (ref "R149")
      (value "0603_10ohm")
      (footprint "FP-MCT0603-IPC_A")
      (description "RES SMD 100 OHM 1% 1/8W 0603")
      (fields (field (name "TOLERANCE") "0.1%"))
      (libsource (lib "Altium Content Vault") (part "1029c3af85768c4190bb7ad29bc67b5"))
    )
    (comp (ref "R150")
      (value "0603_10ohm")
      (footprint "FP-MCT0603-IPC_A")
      (description "RES SMD 100 OHM 1% 1/8W 0603")
      (fields (field (name "TOLERANCE") "0.1%"))
      (libsource (lib "Altium Content Vault") (part "1029c3af85768c4190bb7ad29bc67b5"))
    )
    (comp (ref "R151")
      (value "0603_10ohm")
      (footprint "FP-MCT0603-IPC_A")
      (description "RES SMD 100 OHM 1% 1/8W 0603")
      (fields (field (name "TOLERANCE") "0.1%"))
      (libsource (lib "Altium Content Vault") (part "1029c3af85768c4190bb7ad29bc67b5"))
    )
    (comp (ref "R152")
      (value "0603_10ohm")
      (footprint "FP-MCT0603-IPC_A")
      (description "RES SMD 100 OHM 1% 1/8W 0603")
      (fields (field (name "TOLERANCE") "0.1%"))
      (libsource (lib "Altium Content Vault") (part "1029c3af85768c4190bb7ad29bc67b5"))
    )
    (comp (ref "R153")
      (value "0603_10ohm")
      (footprint "FP-MCT0603-IPC_A")
      (description "RES SMD 100 OHM 1% 1/8W 0603")
      (fields (field (name "TOLERANCE") "0.1%"))
      (libsource (lib "Altium Content Vault") (part "1029c3af85768c4190bb7ad29bc67b5"))
    )
    (comp (ref "R154")
      (value "0603_10ohm")
      (footprint "FP-MCT0603-IPC_A")
      (description "RES SMD 100 OHM 1% 1/8W 0603")
      (fields (field (name "TOLERANCE") "0.1%"))
      (libsource (lib "Altium Content Vault") (part "1029c3af85768c4190bb7ad29bc67b5"))
    )
    (comp (ref "R155")
      (value "0603_10ohm")
      (footprint "FP-MCT0603-IPC_A")
      (description "RES SMD 100 OHM 1% 1/8W 0603")
      (fields (field (name "TOLERANCE") "0.1%"))
      (libsource (lib "Altium Content Vault") (part "1029c3af85768c4190bb7ad29bc67b5"))
    )
    (comp (ref "R156")
      (value "0603_10ohm")
      (footprint "FP-MCT0603-IPC_A")
      (description "RES SMD 100 OHM 1% 1/8W 0603")
      (fields (field (name "TOLERANCE") "0.1%"))
      (libsource (lib "Altium Content Vault") (part "1029c3af85768c4190bb7ad29bc67b5"))
    )
    (comp (ref "R157")
      (value "CRGP0805F10K")
      (footprint "FP-CRGP0805-IPC_C")
      (description "CRGP 0805 10K 1%")
      (fields
        (field (name "MANUFACTURER") "TE")
        (field (name "ALTIUM_VALUE") "10KΩ")
        (field (name "OCTOPART") "https://octopart.com/crgp0805f10k-te+connectivity-91018782")
      )
      (libsource (lib "Altium Content Vault") (part "1029c3af85768c4190bb7ad29bc67b5"))
    )
    (comp (ref "R158")
      (value "CRGP0805F10K")
      (footprint "FP-CRGP0805-IPC_C")
      (description "CRGP 0805 10K 1%")
      (fields
        (field (name "MANUFACTURER") "TE")
        (field (name "ALTIUM_VALUE") "10KΩ")
        (field (name "OCTOPART") "https://octopart.com/crgp0805f10k-te+connectivity-91018782")
      )
      (libsource (lib "Altium Content Vault") (part "1029c3af85768c4190bb7ad29bc67b5"))
    )
    (comp (ref "R159")
      (value "CRGP0805F10K")
      (footprint "FP-CRGP0805-IPC_C")
      (description "CRGP 0805 10K 1%")
      (fields
        (field (name "MANUFACTURER") "TE")
        (field (name "ALTIUM_VALUE") "10KΩ")
        (field (name "OCTOPART") "https://octopart.com/crgp0805f10k-te+connectivity-91018782")
      )
      (libsource (lib "Altium Content Vault") (part "1029c3af85768c4190bb7ad29bc67b5"))
    )
    (comp (ref "R160")
      (value "CRGP0805F10K")
      (footprint "FP-CRGP0805-IPC_C")
      (description "CRGP 0805 10K 1%")
      (fields
        (field (name "MANUFACTURER") "TE")
        (field (name "ALTIUM_VALUE") "10KΩ")
        (field (name "OCTOPART") "https://octopart.com/crgp0805f10k-te+connectivity-91018782")
      )
      (libsource (lib "Altium Content Vault") (part "1029c3af85768c4190bb7ad29bc67b5"))
    )
    (comp (ref "R161")
      (value "CRGP0805F10K")
      (footprint "FP-CRGP0805-IPC_C")
      (description "CRGP 0805 10K 1%")
      (fields
        (field (name "MANUFACTURER") "TE")
        (field (name "ALTIUM_VALUE") "10KΩ")
        (field (name "OCTOPART") "https://octopart.com/crgp0805f10k-te+connectivity-91018782")
      )
      (libsource (lib "Altium Content Vault") (part "1029c3af85768c4190bb7ad29bc67b5"))
    )
    (comp (ref "R162")
      (value "CRGP0805F10K")
      (footprint "FP-CRGP0805-IPC_C")
      (description "CRGP 0805 10K 1%")
      (fields
        (field (name "MANUFACTURER") "TE")
        (field (name "ALTIUM_VALUE") "10KΩ")
        (field (name "OCTOPART") "https://octopart.com/crgp0805f10k-te+connectivity-91018782")
      )
      (libsource (lib "Altium Content Vault") (part "1029c3af85768c4190bb7ad29bc67b5"))
    )
    (comp (ref "R163")
      (value "CRGP0805F10K")
      (footprint "FP-CRGP0805-IPC_C")
      (description "CRGP 0805 10K 1%")
      (fields
        (field (name "MANUFACTURER") "TE")
        (field (name "ALTIUM_VALUE") "10KΩ")
        (field (name "OCTOPART") "https://octopart.com/crgp0805f10k-te+connectivity-91018782")
      )
      (libsource (lib "Altium Content Vault") (part "1029c3af85768c4190bb7ad29bc67b5"))
    )
    (comp (ref "R164")
      (value "CRGP0805F10K")
      (footprint "FP-CRGP0805-IPC_C")
      (description "CRGP 0805 10K 1%")
      (fields
        (field (name "MANUFACTURER") "TE")
        (field (name "ALTIUM_VALUE") "10KΩ")
        (field (name "OCTOPART") "https://octopart.com/crgp0805f10k-te+connectivity-91018782")
      )
      (libsource (lib "Altium Content Vault") (part "1029c3af85768c4190bb7ad29bc67b5"))
    )
    (comp (ref "R165")
      (value "CRGP0805F10K")
      (footprint "FP-CRGP0805-IPC_C")
      (description "CRGP 0805 10K 1%")
      (fields
        (field (name "MANUFACTURER") "TE")
        (field (name "ALTIUM_VALUE") "10KΩ")
        (field (name "OCTOPART") "https://octopart.com/crgp0805f10k-te+connectivity-91018782")
      )
      (libsource (lib "Altium Content Vault") (part "1029c3af85768c4190bb7ad29bc67b5"))
    )
    (comp (ref "R166")
      (value "CRGP0805F10K")
      (footprint "FP-CRGP0805-IPC_C")
      (description "CRGP 0805 10K 1%")
      (fields
        (field (name "MANUFACTURER") "TE")
        (field (name "ALTIUM_VALUE") "10KΩ")
        (field (name "OCTOPART") "https://octopart.com/crgp0805f10k-te+connectivity-91018782")
      )
      (libsource (lib "Altium Content Vault") (part "1029c3af85768c4190bb7ad29bc67b5"))
    )
    (comp (ref "R167")
      (value "CRGP0805F10K")
      (footprint "FP-CRGP0805-IPC_C")
      (description "CRGP 0805 10K 1%")
      (fields
        (field (name "MANUFACTURER") "TE")
        (field (name "ALTIUM_VALUE") "10KΩ")
        (field (name "OCTOPART") "https://octopart.com/crgp0805f10k-te+connectivity-91018782")
      )
      (libsource (lib "Altium Content Vault") (part "1029c3af85768c4190bb7ad29bc67b5"))
    )
    (comp (ref "R168")
      (value "CRGP0805F10K")
      (footprint "FP-CRGP0805-IPC_C")
      (description "CRGP 0805 10K 1%")
      (fields
        (field (name "MANUFACTURER") "TE")
        (field (name "ALTIUM_VALUE") "10KΩ")
        (field (name "OCTOPART") "https://octopart.com/crgp0805f10k-te+connectivity-91018782")
      )
      (libsource (lib "Altium Content Vault") (part "1029c3af85768c4190bb7ad29bc67b5"))
    )
    (comp (ref "R169")
      (value "CRGP0805F10K")
      (footprint "FP-CRGP0805-IPC_C")
      (description "CRGP 0805 10K 1%")
      (fields
        (field (name "MANUFACTURER") "TE")
        (field (name "ALTIUM_VALUE") "10KΩ")
        (field (name "OCTOPART") "https://octopart.com/crgp0805f10k-te+connectivity-91018782")
      )
      (libsource (lib "Altium Content Vault") (part "1029c3af85768c4190bb7ad29bc67b5"))
    )
    (comp (ref "R170")
      (value "CRGP0805F10K")
      (footprint "FP-CRGP0805-IPC_C")
      (description "CRGP 0805 10K 1%")
      (fields
        (field (name "MANUFACTURER") "TE")
        (field (name "ALTIUM_VALUE") "10KΩ")
        (field (name "OCTOPART") "https://octopart.com/crgp0805f10k-te+connectivity-91018782")
      )
      (libsource (lib "Altium Content Vault") (part "1029c3af85768c4190bb7ad29bc67b5"))
    )
    (comp (ref "R171")
      (value "CRGP0805F10K")
      (footprint "FP-CRGP0805-IPC_C")
      (description "CRGP 0805 10K 1%")
      (fields
        (field (name "MANUFACTURER") "TE")
        (field (name "ALTIUM_VALUE") "10KΩ")
        (field (name "OCTOPART") "https://octopart.com/crgp0805f10k-te+connectivity-91018782")
      )
      (libsource (lib "Altium Content Vault") (part "1029c3af85768c4190bb7ad29bc67b5"))
    )
    (comp (ref "R172")
      (value "CRGP0805F10K")
      (footprint "FP-CRGP0805-IPC_C")
      (description "CRGP 0805 10K 1%")
      (fields
        (field (name "MANUFACTURER") "TE")
        (field (name "ALTIUM_VALUE") "10KΩ")
        (field (name "OCTOPART") "https://octopart.com/crgp0805f10k-te+connectivity-91018782")
      )
      (libsource (lib "Altium Content Vault") (part "1029c3af85768c4190bb7ad29bc67b5"))
    )
    (comp (ref "R173")
      (value "CRGP0805F10K")
      (footprint "FP-CRGP0805-IPC_C")
      (description "CRGP 0805 10K 1%")
      (fields
        (field (name "MANUFACTURER") "TE")
        (field (name "ALTIUM_VALUE") "10KΩ")
        (field (name "OCTOPART") "https://octopart.com/crgp0805f10k-te+connectivity-91018782")
      )
      (libsource (lib "Altium Content Vault") (part "1029c3af85768c4190bb7ad29bc67b5"))
    )
    (comp (ref "R174")
      (value "CRGP0805F10K")
      (footprint "FP-CRGP0805-IPC_C")
      (description "CRGP 0805 10K 1%")
      (fields
        (field (name "MANUFACTURER") "TE")
        (field (name "ALTIUM_VALUE") "10KΩ")
        (field (name "OCTOPART") "https://octopart.com/crgp0805f10k-te+connectivity-91018782")
      )
      (libsource (lib "Altium Content Vault") (part "1029c3af85768c4190bb7ad29bc67b5"))
    )
    (comp (ref "R175")
      (value "CRGP0805F10K")
      (footprint "FP-CRGP0805-IPC_C")
      (description "CRGP 0805 10K 1%")
      (fields
        (field (name "MANUFACTURER") "TE")
        (field (name "ALTIUM_VALUE") "10KΩ")
        (field (name "OCTOPART") "https://octopart.com/crgp0805f10k-te+connectivity-91018782")
      )
      (libsource (lib "Altium Content Vault") (part "1029c3af85768c4190bb7ad29bc67b5"))
    )
    (comp (ref "R176")
      (value "CRGP0805F10K")
      (footprint "FP-CRGP0805-IPC_C")
      (description "CRGP 0805 10K 1%")
      (fields
        (field (name "MANUFACTURER") "TE")
        (field (name "ALTIUM_VALUE") "10KΩ")
        (field (name "OCTOPART") "https://octopart.com/crgp0805f10k-te+connectivity-91018782")
      )
      (libsource (lib "Altium Content Vault") (part "1029c3af85768c4190bb7ad29bc67b5"))
    )
    (comp (ref "R177")
      (value "CRGP0805F10K")
      (footprint "FP-CRGP0805-IPC_C")
      (description "CRGP 0805 10K 1%")
      (fields
        (field (name "MANUFACTURER") "TE")
        (field (name "ALTIUM_VALUE") "10KΩ")
        (field (name "OCTOPART") "https://octopart.com/crgp0805f10k-te+connectivity-91018782")
      )
      (libsource (lib "Altium Content Vault") (part "1029c3af85768c4190bb7ad29bc67b5"))
    )
    (comp (ref "R178")
      (value "CRGP0805F10K")
      (footprint "FP-CRGP0805-IPC_C")
      (description "CRGP 0805 10K 1%")
      (fields
        (field (name "MANUFACTURER") "TE")
        (field (name "ALTIUM_VALUE") "10KΩ")
        (field (name "OCTOPART") "https://octopart.com/crgp0805f10k-te+connectivity-91018782")
      )
      (libsource (lib "Altium Content Vault") (part "1029c3af85768c4190bb7ad29bc67b5"))
    )
    (comp (ref "R179")
      (value "CRGP0805F10K")
      (footprint "FP-CRGP0805-IPC_C")
      (description "CRGP 0805 10K 1%")
      (fields
        (field (name "MANUFACTURER") "TE")
        (field (name "ALTIUM_VALUE") "10KΩ")
        (field (name "OCTOPART") "https://octopart.com/crgp0805f10k-te+connectivity-91018782")
      )
      (libsource (lib "Altium Content Vault") (part "1029c3af85768c4190bb7ad29bc67b5"))
    )
    (comp (ref "R180")
      (value "CRGP0805F10K")
      (footprint "FP-CRGP0805-IPC_C")
      (description "CRGP 0805 10K 1%")
      (fields
        (field (name "MANUFACTURER") "TE")
        (field (name "ALTIUM_VALUE") "10KΩ")
        (field (name "OCTOPART") "https://octopart.com/crgp0805f10k-te+connectivity-91018782")
      )
      (libsource (lib "Altium Content Vault") (part "1029c3af85768c4190bb7ad29bc67b5"))
    )
    (comp (ref "R181")
      (value "RN73R2ATTD2102B25 21K")
      (footprint "FP-RN73R2A-IPC_A")
      (description "21kΩ ±0.1% 0.125W, 1/8W Chip Resistor 0805 (2012 Metric) Moisture Resistant Thin Film")
      (libsource (lib "Altium Content Vault") (part "1029c3af85768c4190bb7ad29bc67b5"))
    )
    (comp (ref "R182")
      (value "RN73R2ATTD2102B25 21K")
      (footprint "FP-RN73R2A-IPC_A")
      (description "21kΩ ±0.1% 0.125W, 1/8W Chip Resistor 0805 (2012 Metric) Moisture Resistant Thin Film")
      (libsource (lib "Altium Content Vault") (part "1029c3af85768c4190bb7ad29bc67b5"))
    )
    (comp (ref "R183")
      (value "RN73R2ATTD2102B25 21K")
      (footprint "FP-RN73R2A-IPC_A")
      (description "21kΩ ±0.1% 0.125W, 1/8W Chip Resistor 0805 (2012 Metric) Moisture Resistant Thin Film")
      (libsource (lib "Altium Content Vault") (part "1029c3af85768c4190bb7ad29bc67b5"))
    )
    (comp (ref "R184")
      (value "RN73R2ATTD2102B25 21K")
      (footprint "FP-RN73R2A-IPC_A")
      (description "21kΩ ±0.1% 0.125W, 1/8W Chip Resistor 0805 (2012 Metric) Moisture Resistant Thin Film")
      (libsource (lib "Altium Content Vault") (part "1029c3af85768c4190bb7ad29bc67b5"))
    )
    (comp (ref "R185")
      (value "RN73R2ATTD2102B25 21K")
      (footprint "FP-RN73R2A-IPC_A")
      (description "21kΩ ±0.1% 0.125W, 1/8W Chip Resistor 0805 (2012 Metric) Moisture Resistant Thin Film")
      (libsource (lib "Altium Content Vault") (part "1029c3af85768c4190bb7ad29bc67b5"))
    )
    (comp (ref "R186")
      (value "RN73R2ATTD2102B25 21K")
      (footprint "FP-RN73R2A-IPC_A")
      (description "21kΩ ±0.1% 0.125W, 1/8W Chip Resistor 0805 (2012 Metric) Moisture Resistant Thin Film")
      (libsource (lib "Altium Content Vault") (part "1029c3af85768c4190bb7ad29bc67b5"))
    )
    (comp (ref "R187")
      (value "RN73R2ATTD2102B25 21K")
      (footprint "FP-RN73R2A-IPC_A")
      (description "21kΩ ±0.1% 0.125W, 1/8W Chip Resistor 0805 (2012 Metric) Moisture Resistant Thin Film")
      (libsource (lib "Altium Content Vault") (part "1029c3af85768c4190bb7ad29bc67b5"))
    )
    (comp (ref "R188")
      (value "RN73R2ATTD2102B25 21K")
      (footprint "FP-RN73R2A-IPC_A")
      (description "21kΩ ±0.1% 0.125W, 1/8W Chip Resistor 0805 (2012 Metric) Moisture Resistant Thin Film")
      (libsource (lib "Altium Content Vault") (part "1029c3af85768c4190bb7ad29bc67b5"))
    )
    (comp (ref "R189")
      (value "RN73R2ATTD2102B25 21K")
      (footprint "FP-RN73R2A-IPC_A")
      (description "21kΩ ±0.1% 0.125W, 1/8W Chip Resistor 0805 (2012 Metric) Moisture Resistant Thin Film")
      (libsource (lib "Altium Content Vault") (part "1029c3af85768c4190bb7ad29bc67b5"))
    )
    (comp (ref "R190")
      (value "RN73R2ATTD2102B25 21K")
      (footprint "FP-RN73R2A-IPC_A")
      (description "21kΩ ±0.1% 0.125W, 1/8W Chip Resistor 0805 (2012 Metric) Moisture Resistant Thin Film")
      (libsource (lib "Altium Content Vault") (part "1029c3af85768c4190bb7ad29bc67b5"))
    )
    (comp (ref "R191")
      (value "RN73R2ATTD2102B25 21K")
      (footprint "FP-RN73R2A-IPC_A")
      (description "21kΩ ±0.1% 0.125W, 1/8W Chip Resistor 0805 (2012 Metric) Moisture Resistant Thin Film")
      (libsource (lib "Altium Content Vault") (part "1029c3af85768c4190bb7ad29bc67b5"))
    )
    (comp (ref "R192")
      (value "RN73R2ATTD2102B25 21K")
      (footprint "FP-RN73R2A-IPC_A")
      (description "21kΩ ±0.1% 0.125W, 1/8W Chip Resistor 0805 (2012 Metric) Moisture Resistant Thin Film")
      (libsource (lib "Altium Content Vault") (part "1029c3af85768c4190bb7ad29bc67b5"))
    )
    (comp (ref "R193")
      (value "RMCF0805JT820R")
      (footprint "FP-RMCF0805-IPC_C")
      (description "820Ω ±5% 0.125W 0805 Thick Film Chip Resistor AEC-Q200 compliant")
      (fields (field (name "TOLERANCE") "5%"))
      (libsource (lib "Altium Content Vault") (part "1029c3af85768c4190bb7ad29bc67b5"))
    )
    (comp (ref "R194")
      (value "RMCF0805JT820R")
      (footprint "FP-RMCF0805-IPC_C")
      (description "820Ω ±5% 0.125W 0805 Thick Film Chip Resistor AEC-Q200 compliant")
      (fields (field (name "TOLERANCE") "5%"))
      (libsource (lib "Altium Content Vault") (part "1029c3af85768c4190bb7ad29bc67b5"))
    )
    (comp (ref "R195")
      (value "RMCF0805JT820R")
      (footprint "FP-RMCF0805-IPC_C")
      (description "820Ω ±5% 0.125W 0805 Thick Film Chip Resistor AEC-Q200 compliant")
      (fields (field (name "TOLERANCE") "5%"))
      (libsource (lib "Altium Content Vault") (part "1029c3af85768c4190bb7ad29bc67b5"))
    )
    (comp (ref "R196")
      (value "RMCF0805JT820R")
      (footprint "FP-RMCF0805-IPC_C")
      (description "820Ω ±5% 0.125W 0805 Thick Film Chip Resistor AEC-Q200 compliant")
      (fields (field (name "TOLERANCE") "5%"))
      (libsource (lib "Altium Content Vault") (part "1029c3af85768c4190bb7ad29bc67b5"))
    )
    (comp (ref "R197")
      (value "RN73R2ATTD2102B25 21K")
      (footprint "FP-RN73R2A-IPC_A")
      (description "21kΩ ±0.1% 0.125W, 1/8W Chip Resistor 0805 (2012 Metric) Moisture Resistant Thin Film")
      (libsource (lib "Altium Content Vault") (part "1029c3af85768c4190bb7ad29bc67b5"))
    )
    (comp (ref "R198")
      (value "RN73R2ATTD2102B25 21K")
      (footprint "FP-RN73R2A-IPC_A")
      (description "21kΩ ±0.1% 0.125W, 1/8W Chip Resistor 0805 (2012 Metric) Moisture Resistant Thin Film")
      (libsource (lib "Altium Content Vault") (part "1029c3af85768c4190bb7ad29bc67b5"))
    )
    (comp (ref "R199")
      (value "RN73R2ATTD2102B25 21K")
      (footprint "FP-RN73R2A-IPC_A")
      (description "21kΩ ±0.1% 0.125W, 1/8W Chip Resistor 0805 (2012 Metric) Moisture Resistant Thin Film")
      (libsource (lib "Altium Content Vault") (part "1029c3af85768c4190bb7ad29bc67b5"))
    )
    (comp (ref "R200")
      (value "RN73R2ATTD2102B25 21K")
      (footprint "FP-RN73R2A-IPC_A")
      (description "21kΩ ±0.1% 0.125W, 1/8W Chip Resistor 0805 (2012 Metric) Moisture Resistant Thin Film")
      (libsource (lib "Altium Content Vault") (part "1029c3af85768c4190bb7ad29bc67b5"))
    )
    (comp (ref "R201")
      (value "RN73R2ATTD2102B25 21K")
      (footprint "FP-RN73R2A-IPC_A")
      (description "21kΩ ±0.1% 0.125W, 1/8W Chip Resistor 0805 (2012 Metric) Moisture Resistant Thin Film")
      (libsource (lib "Altium Content Vault") (part "1029c3af85768c4190bb7ad29bc67b5"))
    )
    (comp (ref "R202")
      (value "RN73R2ATTD2102B25 21K")
      (footprint "FP-RN73R2A-IPC_A")
      (description "21kΩ ±0.1% 0.125W, 1/8W Chip Resistor 0805 (2012 Metric) Moisture Resistant Thin Film")
      (libsource (lib "Altium Content Vault") (part "1029c3af85768c4190bb7ad29bc67b5"))
    )
    (comp (ref "R203")
      (value "RMCF0805JT220R")
      (footprint "FP-RMCF0805-IPC_A")
      (description "220Ω ±5% 0.125W 0805 Thick Film Chip Resistor AEC-Q200 compliant")
      (fields (field (name "TOLERANCE") "5%"))
      (libsource (lib "Altium Content Vault") (part "1029c3af85768c4190bb7ad29bc67b5"))
    )
    (comp (ref "R204")
      (value "RMCF0805JT220R")
      (footprint "FP-RMCF0805-IPC_A")
      (description "220Ω ±5% 0.125W 0805 Thick Film Chip Resistor AEC-Q200 compliant")
      (fields (field (name "TOLERANCE") "5%"))
      (libsource (lib "Altium Content Vault") (part "1029c3af85768c4190bb7ad29bc67b5"))
    )
    (comp (ref "R205")
      (value "RMCF0805JT220R")
      (footprint "FP-RMCF0805-IPC_A")
      (description "220Ω ±5% 0.125W 0805 Thick Film Chip Resistor AEC-Q200 compliant")
      (fields (field (name "TOLERANCE") "5%"))
      (libsource (lib "Altium Content Vault") (part "1029c3af85768c4190bb7ad29bc67b5"))
    )
    (comp (ref "R206")
      (value "RMCF0805JT220R")
      (footprint "FP-RMCF0805-IPC_A")
      (description "220Ω ±5% 0.125W 0805 Thick Film Chip Resistor AEC-Q200 compliant")
      (fields (field (name "TOLERANCE") "5%"))
      (libsource (lib "Altium Content Vault") (part "1029c3af85768c4190bb7ad29bc67b5"))
    )
    (comp (ref "R207")
      (value "CRGP0805F10K")
      (footprint "FP-CRGP0805-IPC_C")
      (description "CRGP 0805 10K 1%")
      (fields
        (field (name "MANUFACTURER") "TE")
        (field (name "ALTIUM_VALUE") "10KΩ")
        (field (name "OCTOPART") "https://octopart.com/crgp0805f10k-te+connectivity-91018782")
      )
      (libsource (lib "Altium Content Vault") (part "1029c3af85768c4190bb7ad29bc67b5"))
    )
    (comp (ref "R208")
      (value "CRGP0805F10K")
      (footprint "FP-CRGP0805-IPC_C")
      (description "CRGP 0805 10K 1%")
      (fields
        (field (name "MANUFACTURER") "TE")
        (field (name "ALTIUM_VALUE") "10KΩ")
        (field (name "OCTOPART") "https://octopart.com/crgp0805f10k-te+connectivity-91018782")
      )
      (libsource (lib "Altium Content Vault") (part "1029c3af85768c4190bb7ad29bc67b5"))
    )
    (comp (ref "R209")
      (value "CRCW08055K00FKTA 5K")
      (footprint "RESC2013X50X30ML20T20")
      (fields (field (name "PART NUMBER") "CRCW08055K00FKTA") (field (name "MANUFACTURER") "Vishay Dale"))
      (libsource (lib "Altium Content Vault") (part "RES"))
    )
    (comp (ref "U1")
      (value "LM358AN/NOPB")
      (footprint "FP-P0008A-MFG")
      (description "IC OPAMP GP 2 CIRCUIT 8DIP")
      (fields
        (field (name "MANUFACTURER") "Texas Instruments")
        (field (name "OCTOPART") "https://octopart.com/lm358an%2Fnopb-texas+instruments-24814014")
      )
      (libsource (lib "Altium Content Vault") (part "1d8c551adc971fa6d54955cbfc8f220"))
    )
    (comp (ref "U2")
      (value "LM2917N")
      (footprint "N14A")
      (description "Frequency to Voltage Converter, 14-pin MDIP")
      (fields (field (name "MANUFACTURER") "National Semiconductor"))
      (libsource (lib "Altium Content Vault") (part "CON-FVC-LM2907-IL14"))
    )
    (comp (ref "U3")
      (value "LM393NG")
      (footprint "ONSC-PDIP-8-626-05_M")
      (description "Low Offset Voltage Dual Comparators, 2 to 36 V, 0 to 70 degC, 8-Pin PDIP, Pb-Free, Tube")
      (fields (field (name "MANUFACTURER") "On Semiconductor"))
      (libsource (lib "Altium Content Vault") (part "ONSC-LM2903X_X93_LMV393_NVC2903-8"))
    )
    (comp (ref "U4")
      (value "KSC1845FTA")
      (footprint "TO-92-3L_5P33X5P2_ONS")
      (description "No Description Available")
      (fields (field (name "COPYRIGHT") "Copyright (C) 2025 Ultra Librarian. All rights reserved."))
      (libsource (lib "guitar tuner schematick") (part "KSC1845FTA"))
    )
    (comp (ref "U5")
      (value "LM358AN/NOPB")
      (footprint "FP-P0008A-MFG")
      (description "IC OPAMP GP 2 CIRCUIT 8DIP")
      (fields
        (field (name "MANUFACTURER") "Texas Instruments")
        (field (name "OCTOPART") "https://octopart.com/lm358an%2Fnopb-texas+instruments-24814014")
      )
      (libsource (lib "Altium Content Vault") (part "1d8c551adc971fa6d54955cbfc8f220"))
    )
    (comp (ref "U6")
      (value "LM393N")
      (footprint "DIP794W45P254L959H508Q8")
      (description "Comparator General Purpose CMOS, DTL, ECL, MOS, Open-Collector, TTL 8-PDIP")
      (fields (field (name "MF") "Texas Instruments"))
      (libsource (lib "LM393N") (part "LM393N"))
    )
    (comp (ref "U7")
      (value "TL072IP")
      (footprint "DIP794W45P254L959H508Q8")
      (description "Dual, 30-V, 3-MHz, high slew rate (13-V/Âµs), In to V+, JFET-input op amp")
      (fields (field (name "MF") "Texas Instruments"))
      (libsource (lib "TL072IP") (part "TL072IP"))
    )
    (comp (ref "U8")
      (value "TL072IP")
      (footprint "DIP794W45P254L959H508Q8")
      (description "Dual, 30-V, 3-MHz, high slew rate (13-V/Âµs), In to V+, JFET-input op amp")
      (fields (field (name "MF") "Texas Instruments"))
      (libsource (lib "TL072IP") (part "TL072IP"))
    )
    (comp (ref "U9")
      (value "TL072IP")
      (footprint "DIP794W45P254L959H508Q8")
      (description "Dual, 30-V, 3-MHz, high slew rate (13-V/Âµs), In to V+, JFET-input op amp")
      (fields (field (name "MF") "Texas Instruments"))
      (libsource (lib "TL072IP") (part "TL072IP"))
    )
    (comp (ref "U10")
      (value "TL072IP")
      (footprint "DIP794W45P254L959H508Q8")
      (description "Dual, 30-V, 3-MHz, high slew rate (13-V/Âµs), In to V+, JFET-input op amp")
      (fields (field (name "MF") "Texas Instruments"))
      (libsource (lib "TL072IP") (part "TL072IP"))
    )
    (comp (ref "U11")
      (value "TL072IP")
      (footprint "DIP794W45P254L959H508Q8")
      (description "Dual, 30-V, 3-MHz, high slew rate (13-V/Âµs), In to V+, JFET-input op amp")
      (fields (field (name "MF") "Texas Instruments"))
      (libsource (lib "TL072IP") (part "TL072IP"))
    )
    (comp (ref "U12")
      (value "TL072IP")
      (footprint "DIP794W45P254L959H508Q8")
      (description "Dual, 30-V, 3-MHz, high slew rate (13-V/Âµs), In to V+, JFET-input op amp")
      (fields (field (name "MF") "Texas Instruments"))
      (libsource (lib "TL072IP") (part "TL072IP"))
    )
    (comp (ref "U13")
      (value "TL072IP")
      (footprint "DIP794W45P254L959H508Q8")
      (description "Dual, 30-V, 3-MHz, high slew rate (13-V/Âµs), In to V+, JFET-input op amp")
      (fields (field (name "MF") "Texas Instruments"))
      (libsource (lib "TL072IP") (part "TL072IP"))
    )
    (comp (ref "U14")
      (value "TL072IP")
      (footprint "DIP794W45P254L959H508Q8")
      (description "Dual, 30-V, 3-MHz, high slew rate (13-V/Âµs), In to V+, JFET-input op amp")
      (fields (field (name "MF") "Texas Instruments"))
      (libsource (lib "TL072IP") (part "TL072IP"))
    )
    (comp (ref "U15")
      (value "TL072IP")
      (footprint "DIP794W45P254L959H508Q8")
      (description "Dual, 30-V, 3-MHz, high slew rate (13-V/Âµs), In to V+, JFET-input op amp")
      (fields (field (name "MF") "Texas Instruments"))
      (libsource (lib "TL072IP") (part "TL072IP"))
    )
    (comp (ref "U16")
      (value "TL072IP")
      (footprint "DIP794W45P254L959H508Q8")
      (description "Dual, 30-V, 3-MHz, high slew rate (13-V/Âµs), In to V+, JFET-input op amp")
      (fields (field (name "MF") "Texas Instruments"))
      (libsource (lib "TL072IP") (part "TL072IP"))
    )
    (comp (ref "U17")
      (value "TL072IP")
      (footprint "DIP794W45P254L959H508Q8")
      (description "Dual, 30-V, 3-MHz, high slew rate (13-V/Âµs), In to V+, JFET-input op amp")
      (fields (field (name "MF") "Texas Instruments"))
      (libsource (lib "TL072IP") (part "TL072IP"))
    )
    (comp (ref "U18")
      (value "TL072IP")
      (footprint "DIP794W45P254L959H508Q8")
      (description "Dual, 30-V, 3-MHz, high slew rate (13-V/Âµs), In to V+, JFET-input op amp")
      (fields (field (name "MF") "Texas Instruments"))
      (libsource (lib "TL072IP") (part "TL072IP"))
    )
    (comp (ref "Z1")
      (value "connector")
      (footprint "connector")
      (libsource (lib "guitar tuner schematick") (part "connector"))
    )
    (comp (ref "Z2")
      (value "connector")
      (footprint "connector")
      (libsource (lib "guitar tuner schematick") (part "connector"))
    )
    (comp (ref "Z3")
      (value "connector")
      (footprint "connector")
      (libsource (lib "guitar tuner schematick") (part "connector"))
    )
    (comp (ref "Z4")
      (value "connector")
      (footprint "connector")
      (libsource (lib "guitar tuner schematick") (part "connector"))
    )
  )
  (nets
    (net (code "1") (name "+9V") (class "Default")
      (node (ref "C15") (pin "1") (pinfunction "1_1") (pintype "passive"))
      (node (ref "C2") (pin "2") (pinfunction "2_2") (pintype "passive"))
      (node (ref "C4") (pin "2") (pinfunction "2_2") (pintype "passive"))
      (node (ref "R1") (pin "1") (pinfunction "1_1") (pintype "passive"))
      (node (ref "R16") (pin "1") (pinfunction "1_1") (pintype "passive"))
      (node (ref "R2") (pin "1") (pinfunction "1_1") (pintype "passive"))
      (node (ref "R25") (pin "2") (pinfunction "2_2") (pintype "passive"))
      (node (ref "R26") (pin "2") (pinfunction "2_2") (pintype "passive"))
      (node (ref "R28") (pin "2") (pinfunction "2_2") (pintype "passive"))
      (node (ref "R3") (pin "1") (pinfunction "1_1") (pintype "passive"))
      (node (ref "R30") (pin "2") (pinfunction "2_2") (pintype "passive"))
      (node (ref "R35") (pin "2") (pinfunction "2_2") (pintype "passive"))
      (node (ref "R39") (pin "1") (pinfunction "1_1") (pintype "passive"))
      (node (ref "R4") (pin "1") (pinfunction "1_1") (pintype "passive"))
      (node (ref "R41") (pin "2") (pinfunction "2_2") (pintype "passive"))
      (node (ref "R42") (pin "1") (pinfunction "1_1") (pintype "passive"))
      (node (ref "R43") (pin "2") (pinfunction "2_2") (pintype "passive"))
      (node (ref "R5") (pin "1") (pinfunction "1_1") (pintype "passive"))
      (node (ref "R6") (pin "1") (pinfunction "1_1") (pintype "passive"))
      (node (ref "R8") (pin "2") (pinfunction "2_2") (pintype "passive"))
      (node (ref "U1") (pin "4") (pinfunction "GND_4") (pintype "passive"))
      (node (ref "U10") (pin "8") (pinfunction "VCC+_8") (pintype "passive"))
      (node (ref "U11") (pin "8") (pinfunction "VCC+_8") (pintype "passive"))
      (node (ref "U12") (pin "8") (pinfunction "VCC+_8") (pintype "passive"))
      (node (ref "U13") (pin "8") (pinfunction "VCC+_8") (pintype "passive"))
      (node (ref "U14") (pin "8") (pinfunction "VCC+_8") (pintype "passive"))
      (node (ref "U15") (pin "8") (pinfunction "VCC+_8") (pintype "passive"))
      (node (ref "U16") (pin "8") (pinfunction "VCC+_8") (pintype "passive"))
      (node (ref "U17") (pin "8") (pinfunction "VCC+_8") (pintype "passive"))
      (node (ref "U18") (pin "8") (pinfunction "VCC+_8") (pintype "passive"))
      (node (ref "U2") (pin "8") (pinfunction "COL_8") (pintype "passive"))
      (node (ref "U3") (pin "8") (pinfunction "VCC_8") (pintype "power_in"))
      (node (ref "U5") (pin "8") (pinfunction "V+_8") (pintype "passive"))
      (node (ref "U6") (pin "8") (pinfunction "V+_8") (pintype "passive"))
      (node (ref "U7") (pin "8") (pinfunction "VCC+_8") (pintype "passive"))
      (node (ref "U8") (pin "8") (pinfunction "VCC+_8") (pintype "passive"))
      (node (ref "U9") (pin "8") (pinfunction "VCC+_8") (pintype "passive"))
      (node (ref "p1") (pin "1") (pinfunction "1_1") (pintype "passive"))
    )
    (net (code "3") (name "/C_IN_1_7") (class "Default")
      (node (ref "C34") (pin "1") (pinfunction "1_1") (pintype "passive"))
      (node (ref "R90") (pin "2") (pinfunction "2_2") (pintype "passive"))
    )
    (net (code "4") (name "/C_IN_1_7_1") (class "Default")
      (node (ref "C80") (pin "1") (pinfunction "1_1") (pintype "passive"))
      (node (ref "R114") (pin "2") (pinfunction "2_2") (pintype "passive"))
      (node (ref "U12") (pin "7") (pinfunction "2OUT_7") (pintype "passive"))
    )
    (net (code "5") (name "/C_IN_2_7") (class "Default")
      (node (ref "C22") (pin "2") (pinfunction "2_2") (pintype "passive"))
      (node (ref "R98") (pin "2") (pinfunction "2_2") (pintype "passive"))
    )
    (net (code "6") (name "/C_IN_2_7_1") (class "Default")
      (node (ref "C68") (pin "2") (pinfunction "2_2") (pintype "passive"))
      (node (ref "R106") (pin "2") (pinfunction "2_2") (pintype "passive"))
      (node (ref "U10") (pin "7") (pinfunction "2OUT_7") (pintype "passive"))
    )
    (net (code "7") (name "/C_IN_3_7") (class "Default")
      (node (ref "C19") (pin "2") (pinfunction "2_2") (pintype "passive"))
      (node (ref "C24") (pin "2") (pinfunction "2_2") (pintype "passive"))
      (node (ref "R100") (pin "2") (pinfunction "2_2") (pintype "passive"))
    )
    (net (code "8") (name "/C_IN_3_7_1") (class "Default")
      (node (ref "C65") (pin "2") (pinfunction "2_2") (pintype "passive"))
      (node (ref "C70") (pin "2") (pinfunction "2_2") (pintype "passive"))
      (node (ref "R110") (pin "1") (pinfunction "1_1") (pintype "passive"))
      (node (ref "U11") (pin "7") (pinfunction "2OUT_7") (pintype "passive"))
    )
    (net (code "9") (name "/C_IN_4_7") (class "Default")
      (node (ref "C27") (pin "2") (pinfunction "2_2") (pintype "passive"))
      (node (ref "R130") (pin "2") (pinfunction "2_2") (pintype "passive"))
    )
    (net (code "10") (name "/C_IN_4_7_1") (class "Default")
      (node (ref "C73") (pin "2") (pinfunction "2_2") (pintype "passive"))
      (node (ref "R143") (pin "2") (pinfunction "2_2") (pintype "passive"))
      (node (ref "U16") (pin "7") (pinfunction "2OUT_7") (pintype "passive"))
    )
    (net (code "11") (name "/C_IN_5_7") (class "Default")
      (node (ref "C29") (pin "1") (pinfunction "1_1") (pintype "passive"))
      (node (ref "C37") (pin "2") (pinfunction "2_2") (pintype "passive"))
      (node (ref "R125") (pin "2") (pinfunction "2_2") (pintype "passive"))
    )
    (net (code "12") (name "/C_IN_5_7_1") (class "Default")
      (node (ref "C75") (pin "1") (pinfunction "1_1") (pintype "passive"))
      (node (ref "C83") (pin "2") (pinfunction "2_2") (pintype "passive"))
      (node (ref "R142") (pin "1") (pinfunction "1_1") (pintype "passive"))
      (node (ref "U15") (pin "7") (pinfunction "2OUT_7") (pintype "passive"))
    )
    (net (code "13") (name "/C_IN_6_7") (class "Default")
      (node (ref "C38") (pin "1") (pinfunction "1_1") (pintype "passive"))
      (node (ref "C41") (pin "2") (pinfunction "2_2") (pintype "passive"))
      (node (ref "R150") (pin "2") (pinfunction "2_2") (pintype "passive"))
    )
    (net (code "14") (name "/C_IN_6_7_1") (class "Default")
      (node (ref "C84") (pin "1") (pinfunction "1_1") (pintype "passive"))
      (node (ref "C87") (pin "2") (pinfunction "2_2") (pintype "passive"))
      (node (ref "R156") (pin "2") (pinfunction "2_2") (pintype "passive"))
    )
    (net (code "15") (name "/INPUT_1") (class "Default")
      (node (ref "R132") (pin "1") (pinfunction "1_1") (pintype "passive"))
      (node (ref "R53") (pin "2") (pinfunction "2_2") (pintype "passive"))
      (node (ref "R55") (pin "2") (pinfunction "2_2") (pintype "passive"))
    )
    (net (code "16") (name "/INPUT_2") (class "Default")
      (node (ref "R135") (pin "1") (pinfunction "1_1") (pintype "passive"))
      (node (ref "R46") (pin "2") (pinfunction "2_2") (pintype "passive"))
      (node (ref "R49") (pin "2") (pinfunction "2_2") (pintype "passive"))
    )
    (net (code "17") (name "/INPUT_3") (class "Default")
      (node (ref "R136") (pin "1") (pinfunction "1_1") (pintype "passive"))
      (node (ref "R58") (pin "2") (pinfunction "2_2") (pintype "passive"))
    )
    (net (code "18") (name "/INPUT_4") (class "Default")
      (node (ref "R138") (pin "1") (pinfunction "1_1") (pintype "passive"))
      (node (ref "R208") (pin "2") (pinfunction "2_2") (pintype "passive"))
    )
    (net (code "19") (name "/INPUT_5") (class "Default")
      (node (ref "R140") (pin "1") (pinfunction "1_1") (pintype "passive"))
      (node (ref "R64") (pin "2") (pinfunction "2_2") (pintype "passive"))
      (node (ref "R70") (pin "2") (pinfunction "2_2") (pintype "passive"))
    )
    (net (code "20") (name "/INPUT_6") (class "Default")
      (node (ref "R144") (pin "1") (pinfunction "1_1") (pintype "passive"))
      (node (ref "R63") (pin "2") (pinfunction "2_2") (pintype "passive"))
      (node (ref "R69") (pin "2") (pinfunction "2_2") (pintype "passive"))
    )
    (net (code "21") (name "/OUTPUT_1") (class "Default")
      (node (ref "P3") (pin "1") (pinfunction "1_1") (pintype "passive"))
      (node (ref "R92") (pin "2") (pinfunction "2_2") (pintype "passive"))
    )
    (net (code "22") (name "/OUTPUT_2") (class "Default")
      (node (ref "P3") (pin "2") (pinfunction "2_2") (pintype "passive"))
      (node (ref "R97") (pin "2") (pinfunction "2_2") (pintype "passive"))
    )
    (net (code "23") (name "/OUTPUT_3") (class "Default")
      (node (ref "P3") (pin "3") (pinfunction "3_3") (pintype "passive"))
      (node (ref "R100") (pin "1") (pinfunction "1_1") (pintype "passive"))
      (node (ref "R101") (pin "1") (pinfunction "1_1") (pintype "passive"))
      (node (ref "R95") (pin "1") (pinfunction "1_1") (pintype "passive"))
      (node (ref "U8") (pin "7") (pinfunction "2OUT_7") (pintype "passive"))
    )
    (net (code "24") (name "/OUTPUT_4") (class "Default")
      (node (ref "P3") (pin "4") (pinfunction "4_4") (pintype "passive"))
      (node (ref "R128") (pin "2") (pinfunction "2_2") (pintype "passive"))
    )
    (net (code "25") (name "/OUTPUT_5") (class "Default")
      (node (ref "P2") (pin "1") (pinfunction "1_1") (pintype "passive"))
      (node (ref "R127") (pin "2") (pinfunction "2_2") (pintype "passive"))
    )
    (net (code "26") (name "/OUTPUT_6") (class "Default")
      (node (ref "P2") (pin "2") (pinfunction "2_2") (pintype "passive"))
      (node (ref "R152") (pin "2") (pinfunction "2_2") (pintype "passive"))
    )
    (net (code "27") (name "/POT_NODE") (class "Default")
      (node (ref "U6") (pin "2") (pinfunction "NEG_A_2") (pintype "passive"))
      (node (ref "U6") (pin "5") (pinfunction "POS_B_5") (pintype "passive"))
    )
    (net (code "28") (name "/R1_3_IN") (class "Default")
      (node (ref "R102") (pin "1") (pinfunction "1_1") (pintype "passive"))
      (node (ref "R204") (pin "2") (pinfunction "2_2") (pintype "passive"))
    )
    (net (code "29") (name "/R1_3_OUT") (class "Default")
      (node (ref "R112") (pin "1") (pinfunction "1_1") (pintype "passive"))
      (node (ref "R194") (pin "2") (pinfunction "2_2") (pintype "passive"))
    )
    (net (code "30") (name "/R1_4_IN") (class "Default")
      (node (ref "R205") (pin "2") (pinfunction "2_2") (pintype "passive"))
      (node (ref "R96") (pin "1") (pinfunction "1_1") (pintype "passive"))
    )
    (net (code "31") (name "/R1_4_OUT") (class "Default")
      (node (ref "R114") (pin "1") (pinfunction "1_1") (pintype "passive"))
      (node (ref "R195") (pin "2") (pinfunction "2_2") (pintype "passive"))
    )
    (net (code "32") (name "/R1_5_IN") (class "Default")
      (node (ref "R112") (pin "2") (pinfunction "2_2") (pintype "passive"))
      (node (ref "R206") (pin "2") (pinfunction "2_2") (pintype "passive"))
      (node (ref "U12") (pin "1") (pinfunction "1OUT_1") (pintype "passive"))
    )
    (net (code "33") (name "/R1_5_OUT") (class "Default")
      (node (ref "R111") (pin "2") (pinfunction "2_2") (pintype "passive"))
      (node (ref "R196") (pin "2") (pinfunction "2_2") (pintype "passive"))
      (node (ref "U12") (pin "2") (pinfunction "1IN-_2") (pintype "passive"))
    )
    (net (code "34") (name "/R1_6_IN") (class "Default")
      (node (ref "R203") (pin "2") (pinfunction "2_2") (pintype "passive"))
      (node (ref "R91") (pin "2") (pinfunction "2_2") (pintype "passive"))
    )
    (net (code "35") (name "/R1_6_OUT") (class "Default")
      (node (ref "R113") (pin "1") (pinfunction "1_1") (pintype "passive"))
      (node (ref "R193") (pin "2") (pinfunction "2_2") (pintype "passive"))
    )
    (net (code "36") (name "/R2_1_IN") (class "Default")
      (node (ref "R167") (pin "2") (pinfunction "2_2") (pintype "passive"))
      (node (ref "R88") (pin "2") (pinfunction "2_2") (pintype "passive"))
      (node (ref "U7") (pin "1") (pinfunction "1OUT_1") (pintype "passive"))
    )
    (net (code "37") (name "/R2_1_OUT") (class "Default")
      (node (ref "R167") (pin "1") (pinfunction "1_1") (pintype "passive"))
      (node (ref "R83") (pin "2") (pinfunction "2_2") (pintype "passive"))
      (node (ref "R84") (pin "2") (pinfunction "2_2") (pintype "passive"))
      (node (ref "R85") (pin "2") (pinfunction "2_2") (pintype "passive"))
      (node (ref "U7") (pin "2") (pinfunction "1IN-_2") (pintype "passive"))
    )
    (net (code "38") (name "/R2_2_IN") (class "Default")
      (node (ref "R165") (pin "2") (pinfunction "2_2") (pintype "passive"))
      (node (ref "R88") (pin "1") (pinfunction "1_1") (pintype "passive"))
    )
    (net (code "39") (name "/R2_2_OUT") (class "Default")
      (node (ref "R165") (pin "1") (pinfunction "1_1") (pintype "passive"))
      (node (ref "R93") (pin "2") (pinfunction "2_2") (pintype "passive"))
      (node (ref "U7") (pin "6") (pinfunction "2IN-_6") (pintype "passive"))
    )
    (net (code "40") (name "/R2_3_IN") (class "Default")
      (node (ref "R163") (pin "2") (pinfunction "2_2") (pintype "passive"))
      (node (ref "R85") (pin "1") (pinfunction "1_1") (pintype "passive"))
    )
    (net (code "41") (name "/R2_3_OUT") (class "Default")
      (node (ref "R104") (pin "1") (pinfunction "1_1") (pintype "passive"))
      (node (ref "R163") (pin "1") (pinfunction "1_1") (pintype "passive"))
      (node (ref "U10") (pin "1") (pinfunction "1OUT_1") (pintype "passive"))
    )
    (net (code "42") (name "/R2_4_IN") (class "Default")
      (node (ref "R162") (pin "2") (pinfunction "2_2") (pintype "passive"))
      (node (ref "R84") (pin "1") (pinfunction "1_1") (pintype "passive"))
    )
    (net (code "43") (name "/R2_4_OUT") (class "Default")
      (node (ref "R106") (pin "1") (pinfunction "1_1") (pintype "passive"))
      (node (ref "R162") (pin "1") (pinfunction "1_1") (pintype "passive"))
    )
    (net (code "44") (name "/R2_5_IN") (class "Default")
      (node (ref "R104") (pin "2") (pinfunction "2_2") (pintype "passive"))
      (node (ref "R160") (pin "2") (pinfunction "2_2") (pintype "passive"))
    )
    (net (code "45") (name "/R2_5_OUT") (class "Default")
      (node (ref "R103") (pin "1") (pinfunction "1_1") (pintype "passive"))
      (node (ref "R160") (pin "1") (pinfunction "1_1") (pintype "passive"))
      (node (ref "U10") (pin "2") (pinfunction "1IN-_2") (pintype "passive"))
    )
    (net (code "46") (name "/R2_6_IN") (class "Default")
      (node (ref "R168") (pin "2") (pinfunction "2_2") (pintype "passive"))
      (node (ref "R97") (pin "1") (pinfunction "1_1") (pintype "passive"))
      (node (ref "R98") (pin "1") (pinfunction "1_1") (pintype "passive"))
      (node (ref "R99") (pin "1") (pinfunction "1_1") (pintype "passive"))
      (node (ref "U7") (pin "7") (pinfunction "2OUT_7") (pintype "passive"))
    )
    (net (code "47") (name "/R2_6_OUT") (class "Default")
      (node (ref "R109") (pin "1") (pinfunction "1_1") (pintype "passive"))
      (node (ref "R168") (pin "1") (pinfunction "1_1") (pintype "passive"))
    )
    (net (code "48") (name "/R3_1_IN") (class "Default")
      (node (ref "R161") (pin "2") (pinfunction "2_2") (pintype "passive"))
      (node (ref "R89") (pin "2") (pinfunction "2_2") (pintype "passive"))
      (node (ref "U8") (pin "1") (pinfunction "1OUT_1") (pintype "passive"))
    )
    (net (code "49") (name "/R3_1_OUT") (class "Default")
      (node (ref "R161") (pin "1") (pinfunction "1_1") (pintype "passive"))
      (node (ref "R87") (pin "1") (pinfunction "1_1") (pintype "passive"))
    )
    (net (code "50") (name "/R3_2_IN") (class "Default")
      (node (ref "R158") (pin "2") (pinfunction "2_2") (pintype "passive"))
      (node (ref "R89") (pin "1") (pinfunction "1_1") (pintype "passive"))
    )
    (net (code "51") (name "/R3_2_OUT") (class "Default")
      (node (ref "R158") (pin "1") (pinfunction "1_1") (pintype "passive"))
      (node (ref "R94") (pin "2") (pinfunction "2_2") (pintype "passive"))
      (node (ref "U8") (pin "6") (pinfunction "2IN-_6") (pintype "passive"))
    )
    (net (code "52") (name "/R3_3_IN") (class "Default")
      (node (ref "R157") (pin "2") (pinfunction "2_2") (pintype "passive"))
      (node (ref "R86") (pin "1") (pinfunction "1_1") (pintype "passive"))
    )
    (net (code "53") (name "/R3_3_OUT") (class "Default")
      (node (ref "R105") (pin "1") (pinfunction "1_1") (pintype "passive"))
      (node (ref "R157") (pin "1") (pinfunction "1_1") (pintype "passive"))
      (node (ref "U11") (pin "1") (pinfunction "1OUT_1") (pintype "passive"))
    )
    (net (code "54") (name "/R3_4_IN") (class "Default")
      (node (ref "R159") (pin "2") (pinfunction "2_2") (pintype "passive"))
      (node (ref "R82") (pin "2") (pinfunction "2_2") (pintype "passive"))
      (node (ref "R86") (pin "2") (pinfunction "2_2") (pintype "passive"))
      (node (ref "R87") (pin "2") (pinfunction "2_2") (pintype "passive"))
      (node (ref "U8") (pin "2") (pinfunction "1IN-_2") (pintype "passive"))
    )
    (net (code "55") (name "/R3_4_OUT") (class "Default")
      (node (ref "R110") (pin "2") (pinfunction "2_2") (pintype "passive"))
      (node (ref "R159") (pin "1") (pinfunction "1_1") (pintype "passive"))
    )
    (net (code "56") (name "/R3_5_IN") (class "Default")
      (node (ref "R105") (pin "2") (pinfunction "2_2") (pintype "passive"))
      (node (ref "R134") (pin "2") (pinfunction "2_2") (pintype "passive"))
      (node (ref "R164") (pin "2") (pinfunction "2_2") (pintype "passive"))
    )
    (net (code "57") (name "/R3_5_OUT") (class "Default")
      (node (ref "R107") (pin "1") (pinfunction "1_1") (pintype "passive"))
      (node (ref "R164") (pin "1") (pinfunction "1_1") (pintype "passive"))
    )
    (net (code "58") (name "/R3_6_IN") (class "Default")
      (node (ref "R101") (pin "2") (pinfunction "2_2") (pintype "passive"))
      (node (ref "R166") (pin "2") (pinfunction "2_2") (pintype "passive"))
    )
    (net (code "59") (name "/R3_6_OUT") (class "Default")
      (node (ref "R108") (pin "2") (pinfunction "2_2") (pintype "passive"))
      (node (ref "R166") (pin "1") (pinfunction "1_1") (pintype "passive"))
      (node (ref "U11") (pin "6") (pinfunction "2IN-_6") (pintype "passive"))
    )
    (net (code "60") (name "/R4_1_IN") (class "Default")
      (node (ref "R122") (pin "1") (pinfunction "1_1") (pintype "passive"))
      (node (ref "R179") (pin "2") (pinfunction "2_2") (pintype "passive"))
    )
    (net (code "61") (name "/R4_1_OUT") (class "Default")
      (node (ref "R115") (pin "2") (pinfunction "2_2") (pintype "passive"))
      (node (ref "R116") (pin "2") (pinfunction "2_2") (pintype "passive"))
      (node (ref "R117") (pin "2") (pinfunction "2_2") (pintype "passive"))
      (node (ref "R179") (pin "1") (pinfunction "1_1") (pintype "passive"))
      (node (ref "U14") (pin "2") (pinfunction "1IN-_2") (pintype "passive"))
    )
    (net (code "62") (name "/R4_2_IN") (class "Default")
      (node (ref "R122") (pin "2") (pinfunction "2_2") (pintype "passive"))
      (node (ref "R180") (pin "2") (pinfunction "2_2") (pintype "passive"))
      (node (ref "U14") (pin "1") (pinfunction "1OUT_1") (pintype "passive"))
    )
    (net (code "63") (name "/R4_2_OUT") (class "Default")
      (node (ref "R126") (pin "2") (pinfunction "2_2") (pintype "passive"))
      (node (ref "R180") (pin "1") (pinfunction "1_1") (pintype "passive"))
      (node (ref "U14") (pin "6") (pinfunction "2IN-_6") (pintype "passive"))
    )
    (net (code "64") (name "/R4_3_IN") (class "Default")
      (node (ref "R117") (pin "1") (pinfunction "1_1") (pintype "passive"))
      (node (ref "R176") (pin "2") (pinfunction "2_2") (pintype "passive"))
    )
    (net (code "65") (name "/R4_3_OUT") (class "Default")
      (node (ref "R137") (pin "1") (pinfunction "1_1") (pintype "passive"))
      (node (ref "R176") (pin "1") (pinfunction "1_1") (pintype "passive"))
    )
    (net (code "66") (name "/R4_4_IN") (class "Default")
      (node (ref "R116") (pin "1") (pinfunction "1_1") (pintype "passive"))
      (node (ref "R175") (pin "2") (pinfunction "2_2") (pintype "passive"))
    )
    (net (code "67") (name "/R4_4_OUT") (class "Default")
      (node (ref "R143") (pin "1") (pinfunction "1_1") (pintype "passive"))
      (node (ref "R175") (pin "1") (pinfunction "1_1") (pintype "passive"))
    )
    (net (code "68") (name "/R4_5_IN") (class "Default")
      (node (ref "R137") (pin "2") (pinfunction "2_2") (pintype "passive"))
      (node (ref "R173") (pin "2") (pinfunction "2_2") (pintype "passive"))
      (node (ref "U16") (pin "1") (pinfunction "1OUT_1") (pintype "passive"))
    )
    (net (code "69") (name "/R4_5_OUT") (class "Default")
      (node (ref "R131") (pin "2") (pinfunction "2_2") (pintype "passive"))
      (node (ref "R173") (pin "1") (pinfunction "1_1") (pintype "passive"))
      (node (ref "U16") (pin "2") (pinfunction "1IN-_2") (pintype "passive"))
    )
    (net (code "70") (name "/R4_6_IN") (class "Default")
      (node (ref "R128") (pin "1") (pinfunction "1_1") (pintype "passive"))
      (node (ref "R129") (pin "1") (pinfunction "1_1") (pintype "passive"))
      (node (ref "R130") (pin "1") (pinfunction "1_1") (pintype "passive"))
      (node (ref "R169") (pin "2") (pinfunction "2_2") (pintype "passive"))
      (node (ref "U14") (pin "7") (pinfunction "2OUT_7") (pintype "passive"))
    )
    (net (code "71") (name "/R4_6_OUT") (class "Default")
      (node (ref "R139") (pin "2") (pinfunction "2_2") (pintype "passive"))
      (node (ref "R169") (pin "1") (pinfunction "1_1") (pintype "passive"))
    )
    (net (code "72") (name "/R5_1_IN") (class "Default")
      (node (ref "R118") (pin "2") (pinfunction "2_2") (pintype "passive"))
      (node (ref "R181") (pin "2") (pinfunction "2_2") (pintype "passive"))
      (node (ref "R183") (pin "2") (pinfunction "2_2") (pintype "passive"))
      (node (ref "U13") (pin "1") (pinfunction "1OUT_1") (pintype "passive"))
    )
    (net (code "73") (name "/R5_1_OUT") (class "Default")
      (node (ref "R121") (pin "1") (pinfunction "1_1") (pintype "passive"))
      (node (ref "R182") (pin "1") (pinfunction "1_1") (pintype "passive"))
      (node (ref "R183") (pin "1") (pinfunction "1_1") (pintype "passive"))
    )
    (net (code "74") (name "/R5_2_IN") (class "Default")
      (node (ref "R118") (pin "1") (pinfunction "1_1") (pintype "passive"))
      (node (ref "R184") (pin "2") (pinfunction "2_2") (pintype "passive"))
      (node (ref "R186") (pin "2") (pinfunction "2_2") (pintype "passive"))
    )
    (net (code "75") (name "/R5_2_OUT") (class "Default")
      (node (ref "R123") (pin "2") (pinfunction "2_2") (pintype "passive"))
      (node (ref "R185") (pin "1") (pinfunction "1_1") (pintype "passive"))
      (node (ref "R186") (pin "1") (pinfunction "1_1") (pintype "passive"))
      (node (ref "U13") (pin "6") (pinfunction "2IN-_6") (pintype "passive"))
    )
    (net (code "76") (name "/R5_3_IN") (class "Default")
      (node (ref "R120") (pin "1") (pinfunction "1_1") (pintype "passive"))
      (node (ref "R187") (pin "2") (pinfunction "2_2") (pintype "passive"))
      (node (ref "R189") (pin "2") (pinfunction "2_2") (pintype "passive"))
    )
    (net (code "77") (name "/R5_3_OUT") (class "Default")
      (node (ref "R134") (pin "1") (pinfunction "1_1") (pintype "passive"))
      (node (ref "R188") (pin "1") (pinfunction "1_1") (pintype "passive"))
      (node (ref "R189") (pin "1") (pinfunction "1_1") (pintype "passive"))
      (node (ref "U15") (pin "1") (pinfunction "1OUT_1") (pintype "passive"))
    )
    (net (code "78") (name "/R5_4_IN") (class "Default")
      (node (ref "R119") (pin "2") (pinfunction "2_2") (pintype "passive"))
      (node (ref "R120") (pin "2") (pinfunction "2_2") (pintype "passive"))
      (node (ref "R121") (pin "2") (pinfunction "2_2") (pintype "passive"))
      (node (ref "R190") (pin "2") (pinfunction "2_2") (pintype "passive"))
      (node (ref "R192") (pin "2") (pinfunction "2_2") (pintype "passive"))
      (node (ref "U13") (pin "2") (pinfunction "1IN-_2") (pintype "passive"))
    )
    (net (code "79") (name "/R5_4_OUT") (class "Default")
      (node (ref "R142") (pin "2") (pinfunction "2_2") (pintype "passive"))
      (node (ref "R191") (pin "1") (pinfunction "1_1") (pintype "passive"))
      (node (ref "R192") (pin "1") (pinfunction "1_1") (pintype "passive"))
    )
    (net (code "80") (name "/R5_5_IN") (class "Default")
      (node (ref "R199") (pin "2") (pinfunction "2_2") (pintype "passive"))
      (node (ref "R202") (pin "2") (pinfunction "2_2") (pintype "passive"))
    )
    (net (code "81") (name "/R5_5_OUT") (class "Default")
      (node (ref "R133") (pin "1") (pinfunction "1_1") (pintype "passive"))
      (node (ref "R200") (pin "1") (pinfunction "1_1") (pintype "passive"))
      (node (ref "R202") (pin "1") (pinfunction "1_1") (pintype "passive"))
      (node (ref "U15") (pin "2") (pinfunction "1IN-_2") (pintype "passive"))
    )
    (net (code "82") (name "/R5_6_IN") (class "Default")
      (node (ref "R124") (pin "1") (pinfunction "1_1") (pintype "passive"))
      (node (ref "R125") (pin "1") (pinfunction "1_1") (pintype "passive"))
      (node (ref "R127") (pin "1") (pinfunction "1_1") (pintype "passive"))
      (node (ref "R197") (pin "2") (pinfunction "2_2") (pintype "passive"))
      (node (ref "R201") (pin "2") (pinfunction "2_2") (pintype "passive"))
      (node (ref "U13") (pin "7") (pinfunction "2OUT_7") (pintype "passive"))
    )
    (net (code "83") (name "/R5_6_OUT") (class "Default")
      (node (ref "R141") (pin "1") (pinfunction "1_1") (pintype "passive"))
      (node (ref "R198") (pin "1") (pinfunction "1_1") (pintype "passive"))
      (node (ref "R201") (pin "1") (pinfunction "1_1") (pintype "passive"))
      (node (ref "U15") (pin "6") (pinfunction "2IN-_6") (pintype "passive"))
    )
    (net (code "84") (name "/R6_1_IN") (class "Default")
      (node (ref "R145") (pin "1") (pinfunction "1_1") (pintype "passive"))
      (node (ref "R174") (pin "2") (pinfunction "2_2") (pintype "passive"))
    )
    (net (code "85") (name "/R6_1_OUT") (class "Default")
      (node (ref "R146") (pin "2") (pinfunction "2_2") (pintype "passive"))
      (node (ref "R147") (pin "2") (pinfunction "2_2") (pintype "passive"))
      (node (ref "R148") (pin "2") (pinfunction "2_2") (pintype "passive"))
      (node (ref "R174") (pin "1") (pinfunction "1_1") (pintype "passive"))
      (node (ref "U17") (pin "2") (pinfunction "1IN-_2") (pintype "passive"))
    )
    (net (code "86") (name "/R6_2_IN") (class "Default")
      (node (ref "R145") (pin "2") (pinfunction "2_2") (pintype "passive"))
      (node (ref "R171") (pin "2") (pinfunction "2_2") (pintype "passive"))
      (node (ref "U17") (pin "1") (pinfunction "1OUT_1") (pintype "passive"))
    )
    (net (code "87") (name "/R6_2_OUT") (class "Default")
      (node (ref "R149") (pin "2") (pinfunction "2_2") (pintype "passive"))
      (node (ref "R171") (pin "1") (pinfunction "1_1") (pintype "passive"))
      (node (ref "U17") (pin "6") (pinfunction "2IN-_6") (pintype "passive"))
    )
    (net (code "88") (name "/R6_3_IN") (class "Default")
      (node (ref "R146") (pin "1") (pinfunction "1_1") (pintype "passive"))
      (node (ref "R170") (pin "2") (pinfunction "2_2") (pintype "passive"))
    )
    (net (code "89") (name "/R6_3_OUT") (class "Default")
      (node (ref "R154") (pin "2") (pinfunction "2_2") (pintype "passive"))
      (node (ref "R170") (pin "1") (pinfunction "1_1") (pintype "passive"))
    )
    (net (code "90") (name "/R6_4_IN") (class "Default")
      (node (ref "R148") (pin "1") (pinfunction "1_1") (pintype "passive"))
      (node (ref "R172") (pin "2") (pinfunction "2_2") (pintype "passive"))
    )
    (net (code "91") (name "/R6_4_OUT") (class "Default")
      (node (ref "R156") (pin "1") (pinfunction "1_1") (pintype "passive"))
      (node (ref "R172") (pin "1") (pinfunction "1_1") (pintype "passive"))
      (node (ref "U18") (pin "7") (pinfunction "2OUT_7") (pintype "passive"))
    )
    (net (code "92") (name "/R6_5_IN") (class "Default")
      (node (ref "R154") (pin "1") (pinfunction "1_1") (pintype "passive"))
      (node (ref "R177") (pin "2") (pinfunction "2_2") (pintype "passive"))
      (node (ref "U18") (pin "1") (pinfunction "1OUT_1") (pintype "passive"))
    )
    (net (code "93") (name "/R6_5_OUT") (class "Default")
      (node (ref "R153") (pin "1") (pinfunction "1_1") (pintype "passive"))
      (node (ref "R177") (pin "1") (pinfunction "1_1") (pintype "passive"))
      (node (ref "U18") (pin "2") (pinfunction "1IN-_2") (pintype "passive"))
    )
    (net (code "94") (name "/R6_6_IN") (class "Default")
      (node (ref "R150") (pin "1") (pinfunction "1_1") (pintype "passive"))
      (node (ref "R151") (pin "1") (pinfunction "1_1") (pintype "passive"))
      (node (ref "R152") (pin "1") (pinfunction "1_1") (pintype "passive"))
      (node (ref "R178") (pin "2") (pinfunction "2_2") (pintype "passive"))
      (node (ref "U17") (pin "7") (pinfunction "2OUT_7") (pintype "passive"))
    )
    (net (code "95") (name "/R6_6_OUT") (class "Default")
      (node (ref "R155") (pin "1") (pinfunction "1_1") (pintype "passive"))
      (node (ref "R178") (pin "1") (pinfunction "1_1") (pintype "passive"))
      (node (ref "U18") (pin "6") (pinfunction "2IN-_6") (pintype "passive"))
    )
    (net (code "96") (name "/RK_2_OUT_1") (class "Default")
      (node (ref "R48") (pin "1") (pinfunction "1_1") (pintype "passive"))
      (node (ref "R83") (pin "1") (pinfunction "1_1") (pintype "passive"))
    )
    (net (code "97") (name "/RK_3_OUT_1") (class "Default")
      (node (ref "R59") (pin "1") (pinfunction "1_1") (pintype "passive"))
      (node (ref "R82") (pin "1") (pinfunction "1_1") (pintype "passive"))
    )
    (net (code "98") (name "/RK_4_OUT_1") (class "Default")
      (node (ref "R115") (pin "1") (pinfunction "1_1") (pintype "passive"))
      (node (ref "R209") (pin "1") (pinfunction "1_1") (pintype "passive"))
    )
    (net (code "99") (name "/RK_5_OUT_1") (class "Default")
      (node (ref "R119") (pin "1") (pinfunction "1_1") (pintype "passive"))
      (node (ref "R64") (pin "1") (pinfunction "1_1") (pintype "passive"))
      (node (ref "R70") (pin "1") (pinfunction "1_1") (pintype "passive"))
    )
    (net (code "100") (name "/RK_6_OUT_1") (class "Default")
      (node (ref "R147") (pin "1") (pinfunction "1_1") (pintype "passive"))
      (node (ref "R68") (pin "1") (pinfunction "1_1") (pintype "passive"))
    )
    (net (code "101") (name "/RQ_1_IN") (class "Default")
      (node (ref "R111") (pin "1") (pinfunction "1_1") (pintype "passive"))
      (node (ref "R76") (pin "2") (pinfunction "2_2") (pintype "passive"))
    )
    (net (code "102") (name "/RQ_1_OUT") (class "Default")
      (node (ref "R75") (pin "1") (pinfunction "1_1") (pintype "passive"))
      (node (ref "R80") (pin "2") (pinfunction "2_2") (pintype "passive"))
      (node (ref "R90") (pin "1") (pinfunction "1_1") (pintype "passive"))
      (node (ref "R91") (pin "1") (pinfunction "1_1") (pintype "passive"))
      (node (ref "R92") (pin "1") (pinfunction "1_1") (pintype "passive"))
      (node (ref "U9") (pin "7") (pinfunction "2OUT_7") (pintype "passive"))
    )
    (net (code "103") (name "/RQ_2_IN") (class "Default")
      (node (ref "R103") (pin "2") (pinfunction "2_2") (pintype "passive"))
      (node (ref "R45") (pin "2") (pinfunction "2_2") (pintype "passive"))
    )
    (net (code "104") (name "/RQ_2_OUT") (class "Default")
      (node (ref "R44") (pin "1") (pinfunction "1_1") (pintype "passive"))
      (node (ref "R99") (pin "2") (pinfunction "2_2") (pintype "passive"))
    )
    (net (code "105") (name "/RQ_3_IN") (class "Default")
      (node (ref "R107") (pin "2") (pinfunction "2_2") (pintype "passive"))
      (node (ref "R50") (pin "2") (pinfunction "2_2") (pintype "passive"))
      (node (ref "R54") (pin "2") (pinfunction "2_2") (pintype "passive"))
      (node (ref "U11") (pin "2") (pinfunction "1IN-_2") (pintype "passive"))
    )
    (net (code "106") (name "/RQ_3_OUT") (class "Default")
      (node (ref "R52") (pin "1") (pinfunction "1_1") (pintype "passive"))
      (node (ref "R95") (pin "2") (pinfunction "2_2") (pintype "passive"))
    )
    (net (code "107") (name "/RQ_4_IN") (class "Default")
      (node (ref "R131") (pin "1") (pinfunction "1_1") (pintype "passive"))
      (node (ref "R60") (pin "1") (pinfunction "1_1") (pintype "passive"))
    )
    (net (code "108") (name "/RQ_4_OUT") (class "Default")
      (node (ref "R129") (pin "2") (pinfunction "2_2") (pintype "passive"))
      (node (ref "R61") (pin "1") (pinfunction "1_1") (pintype "passive"))
    )
    (net (code "109") (name "/RQ_5_IN") (class "Default")
      (node (ref "R133") (pin "2") (pinfunction "2_2") (pintype "passive"))
      (node (ref "R65") (pin "1") (pinfunction "1_1") (pintype "passive"))
    )
    (net (code "110") (name "/RQ_5_OUT") (class "Default")
      (node (ref "R124") (pin "2") (pinfunction "2_2") (pintype "passive"))
      (node (ref "R67") (pin "1") (pinfunction "1_1") (pintype "passive"))
    )
    (net (code "111") (name "/RQ_6_IN") (class "Default")
      (node (ref "R153") (pin "2") (pinfunction "2_2") (pintype "passive"))
      (node (ref "R71") (pin "1") (pinfunction "1_1") (pintype "passive"))
    )
    (net (code "112") (name "/RQ_6_OUT") (class "Default")
      (node (ref "R151") (pin "2") (pinfunction "2_2") (pintype "passive"))
      (node (ref "R72") (pin "2") (pinfunction "2_2") (pintype "passive"))
    )
    (net (code "113") (name "/R_1_IN") (class "Default")
      (node (ref "R102") (pin "2") (pinfunction "2_2") (pintype "passive"))
      (node (ref "R53") (pin "1") (pinfunction "1_1") (pintype "passive"))
      (node (ref "R55") (pin "1") (pinfunction "1_1") (pintype "passive"))
      (node (ref "R57") (pin "2") (pinfunction "2_2") (pintype "passive"))
      (node (ref "R96") (pin "2") (pinfunction "2_2") (pintype "passive"))
      (node (ref "U9") (pin "2") (pinfunction "1IN-_2") (pintype "passive"))
    )
    (net (code "114") (name "/R_1_OUT") (class "Default")
      (node (ref "R47") (pin "2") (pinfunction "2_2") (pintype "passive"))
      (node (ref "R62") (pin "2") (pinfunction "2_2") (pintype "passive"))
      (node (ref "U9") (pin "1") (pinfunction "1OUT_1") (pintype "passive"))
    )
    (net (code "115") (name "/R_5_IN") (class "Default")
      (node (ref "R78") (pin "2") (pinfunction "2_2") (pintype "passive"))
      (node (ref "R81") (pin "2") (pinfunction "2_2") (pintype "passive"))
    )
    (net (code "116") (name "/R_5_OUT") (class "Default")
      (node (ref "R79") (pin "1") (pinfunction "1_1") (pintype "passive"))
      (node (ref "R81") (pin "1") (pinfunction "1_1") (pintype "passive"))
    )
    (net (code "117") (name "/V0") (class "Default")
      (node (ref "C3") (pin "2") (pinfunction "2_2") (pintype "passive"))
      (node (ref "R25") (pin "1") (pinfunction "1_1") (pintype "passive"))
      (node (ref "R32") (pin "2") (pinfunction "2_2") (pintype "passive"))
      (node (ref "U3") (pin "1") (pinfunction "OUTA_1") (pintype "open_collector"))
    )
    (net (code "118") (name "/V1") (class "Default")
      (node (ref "R24") (pin "2") (pinfunction "2_2") (pintype "passive"))
      (node (ref "U2") (pin "10") (pinfunction "IN-_10") (pintype "input"))
      (node (ref "U2") (pin "5") (pinfunction "EMIT_5") (pintype "passive"))
      (node (ref "U5") (pin "3") (pinfunction "NON-INVERTING_INPUT_A_3") (pintype "passive"))
    )
    (net (code "119") (name "/V2") (class "Default")
      (node (ref "U5") (pin "1") (pinfunction "OUTPUT_A_1") (pintype "passive"))
      (node (ref "U5") (pin "2") (pinfunction "INVERTING_INPUT_A_2") (pintype "passive"))
      (node (ref "U6") (pin "3") (pinfunction "POA_A_3") (pintype "passive"))
      (node (ref "U6") (pin "6") (pinfunction "NEG_B_6") (pintype "passive"))
    )
    (net (code "120") (name "/cOUT_1_6") (class "Default")
      (node (ref "C31") (pin "2") (pinfunction "2_2") (pintype "passive"))
      (node (ref "C36") (pin "2") (pinfunction "2_2") (pintype "passive"))
      (node (ref "R73") (pin "2") (pinfunction "2_2") (pintype "passive"))
      (node (ref "U9") (pin "6") (pinfunction "2IN-_6") (pintype "passive"))
    )
    (net (code "121") (name "/cOUT_1_6_1") (class "Default")
      (node (ref "C77") (pin "2") (pinfunction "2_2") (pintype "passive"))
      (node (ref "C82") (pin "2") (pinfunction "2_2") (pintype "passive"))
      (node (ref "R113") (pin "2") (pinfunction "2_2") (pintype "passive"))
      (node (ref "U12") (pin "6") (pinfunction "2IN-_6") (pintype "passive"))
    )
    (net (code "122") (name "/cOUT_2_6") (class "Default")
      (node (ref "C21") (pin "1") (pinfunction "1_1") (pintype "passive"))
      (node (ref "C25") (pin "2") (pinfunction "2_2") (pintype "passive"))
      (node (ref "R93") (pin "1") (pinfunction "1_1") (pintype "passive"))
    )
    (net (code "123") (name "/cOUT_2_6_1") (class "Default")
      (node (ref "C67") (pin "1") (pinfunction "1_1") (pintype "passive"))
      (node (ref "C71") (pin "2") (pinfunction "2_2") (pintype "passive"))
      (node (ref "R109") (pin "2") (pinfunction "2_2") (pintype "passive"))
      (node (ref "U10") (pin "6") (pinfunction "2IN-_6") (pintype "passive"))
    )
    (net (code "124") (name "/cOUT_3_6") (class "Default")
      (node (ref "C20") (pin "1") (pinfunction "1_1") (pintype "passive"))
      (node (ref "C24") (pin "1") (pinfunction "1_1") (pintype "passive"))
      (node (ref "R94") (pin "1") (pinfunction "1_1") (pintype "passive"))
    )
    (net (code "125") (name "/cOUT_3_6_1") (class "Default")
      (node (ref "C66") (pin "1") (pinfunction "1_1") (pintype "passive"))
      (node (ref "C70") (pin "1") (pinfunction "1_1") (pintype "passive"))
      (node (ref "R108") (pin "1") (pinfunction "1_1") (pintype "passive"))
    )
    (net (code "126") (name "/cOUT_4_6") (class "Default")
      (node (ref "C26") (pin "1") (pinfunction "1_1") (pintype "passive"))
      (node (ref "C28") (pin "1") (pinfunction "1_1") (pintype "passive"))
      (node (ref "R126") (pin "1") (pinfunction "1_1") (pintype "passive"))
    )
    (net (code "127") (name "/cOUT_4_6_1") (class "Default")
      (node (ref "C72") (pin "1") (pinfunction "1_1") (pintype "passive"))
      (node (ref "C74") (pin "1") (pinfunction "1_1") (pintype "passive"))
      (node (ref "R139") (pin "1") (pinfunction "1_1") (pintype "passive"))
      (node (ref "U16") (pin "6") (pinfunction "2IN-_6") (pintype "passive"))
    )
    (net (code "128") (name "/cOUT_5_6") (class "Default")
      (node (ref "C33") (pin "1") (pinfunction "1_1") (pintype "passive"))
      (node (ref "R123") (pin "1") (pinfunction "1_1") (pintype "passive"))
    )
    (net (code "129") (name "/cOUT_5_6_1") (class "Default")
      (node (ref "C79") (pin "1") (pinfunction "1_1") (pintype "passive"))
      (node (ref "R141") (pin "2") (pinfunction "2_2") (pintype "passive"))
    )
    (net (code "130") (name "/cOUT_6_6") (class "Default")
      (node (ref "C39") (pin "1") (pinfunction "1_1") (pintype "passive"))
      (node (ref "R149") (pin "1") (pinfunction "1_1") (pintype "passive"))
    )
    (net (code "131") (name "/cOUT_6_6_1") (class "Default")
      (node (ref "C85") (pin "1") (pinfunction "1_1") (pintype "passive"))
      (node (ref "R155") (pin "2") (pinfunction "2_2") (pintype "passive"))
    )
    (net (code "132") (name "/pre amp out") (class "Default")
      (node (ref "C12") (pin "2") (pinfunction "2_2") (pintype "passive"))
      (node (ref "C14") (pin "2") (pinfunction "2_2") (pintype "passive"))
      (node (ref "C8") (pin "2") (pinfunction "2_2") (pintype "passive"))
      (node (ref "R29") (pin "2") (pinfunction "2_2") (pintype "passive"))
      (node (ref "U3") (pin "2") (pinfunction "INA-_2") (pintype "input"))
    )
    (net (code "133") (name "/pre_amp_in") (class "Default")
      (node (ref "P2") (pin "4") (pinfunction "4_4") (pintype "passive"))
      (node (ref "R36") (pin "1") (pinfunction "1_1") (pintype "passive"))
    )
    (net (code "134") (name "GND") (class "Default")
      (node (ref "C10") (pin "1") (pinfunction "1_1") (pintype "passive"))
      (node (ref "C15") (pin "2") (pinfunction "2_2") (pintype "passive"))
      (node (ref "C16") (pin "1") (pinfunction "1_1") (pintype "passive"))
      (node (ref "C17") (pin "2") (pinfunction "2_2") (pintype "passive"))
      (node (ref "C18") (pin "2") (pinfunction "2_2") (pintype "passive"))
      (node (ref "C2") (pin "1") (pinfunction "1_1") (pintype "passive"))
      (node (ref "C4") (pin "1") (pinfunction "1_1") (pintype "passive"))
      (node (ref "C5") (pin "1") (pinfunction "1_1") (pintype "passive"))
      (node (ref "C7") (pin "1") (pinfunction "1_1") (pintype "passive"))
      (node (ref "M1") (pin "2") (pinfunction "2_2") (pintype "passive"))
      (node (ref "R17") (pin "2") (pinfunction "2_2") (pintype "passive"))
      (node (ref "R18") (pin "1") (pinfunction "1_1") (pintype "passive"))
      (node (ref "R19") (pin "1") (pinfunction "1_1") (pintype "passive"))
      (node (ref "R20") (pin "1") (pinfunction "1_1") (pintype "passive"))
      (node (ref "R21") (pin "1") (pinfunction "1_1") (pintype "passive"))
      (node (ref "R22") (pin "1") (pinfunction "1_1") (pintype "passive"))
      (node (ref "R23") (pin "1") (pinfunction "1_1") (pintype "passive"))
      (node (ref "R24") (pin "1") (pinfunction "1_1") (pintype "passive"))
      (node (ref "R27") (pin "2") (pinfunction "2_2") (pintype "passive"))
      (node (ref "R29") (pin "1") (pinfunction "1_1") (pintype "passive"))
      (node (ref "R31") (pin "1") (pinfunction "1_1") (pintype "passive"))
      (node (ref "R33") (pin "2") (pinfunction "2_2") (pintype "passive"))
      (node (ref "R38") (pin "1") (pinfunction "1_1") (pintype "passive"))
      (node (ref "R40") (pin "1") (pinfunction "1_1") (pintype "passive"))
      (node (ref "U1") (pin "8") (pinfunction "V+_8") (pintype "passive"))
      (node (ref "U10") (pin "3") (pinfunction "1IN_+_3") (pintype "passive"))
      (node (ref "U10") (pin "4") (pinfunction "VCC-_4") (pintype "passive"))
      (node (ref "U10") (pin "5") (pinfunction "2IN+_5") (pintype "passive"))
      (node (ref "U11") (pin "3") (pinfunction "1IN_+_3") (pintype "passive"))
      (node (ref "U11") (pin "4") (pinfunction "VCC-_4") (pintype "passive"))
      (node (ref "U11") (pin "5") (pinfunction "2IN+_5") (pintype "passive"))
      (node (ref "U12") (pin "3") (pinfunction "1IN_+_3") (pintype "passive"))
      (node (ref "U12") (pin "4") (pinfunction "VCC-_4") (pintype "passive"))
      (node (ref "U12") (pin "5") (pinfunction "2IN+_5") (pintype "passive"))
      (node (ref "U13") (pin "3") (pinfunction "1IN_+_3") (pintype "passive"))
      (node (ref "U13") (pin "4") (pinfunction "VCC-_4") (pintype "passive"))
      (node (ref "U13") (pin "5") (pinfunction "2IN+_5") (pintype "passive"))
      (node (ref "U14") (pin "3") (pinfunction "1IN_+_3") (pintype "passive"))
      (node (ref "U14") (pin "4") (pinfunction "VCC-_4") (pintype "passive"))
      (node (ref "U14") (pin "5") (pinfunction "2IN+_5") (pintype "passive"))
      (node (ref "U15") (pin "3") (pinfunction "1IN_+_3") (pintype "passive"))
      (node (ref "U15") (pin "4") (pinfunction "VCC-_4") (pintype "passive"))
      (node (ref "U15") (pin "5") (pinfunction "2IN+_5") (pintype "passive"))
      (node (ref "U16") (pin "3") (pinfunction "1IN_+_3") (pintype "passive"))
      (node (ref "U16") (pin "4") (pinfunction "VCC-_4") (pintype "passive"))
      (node (ref "U16") (pin "5") (pinfunction "2IN+_5") (pintype "passive"))
      (node (ref "U17") (pin "3") (pinfunction "1IN_+_3") (pintype "passive"))
      (node (ref "U17") (pin "4") (pinfunction "VCC-_4") (pintype "passive"))
      (node (ref "U17") (pin "5") (pinfunction "2IN+_5") (pintype "passive"))
      (node (ref "U18") (pin "3") (pinfunction "1IN_+_3") (pintype "passive"))
      (node (ref "U18") (pin "4") (pinfunction "VCC-_4") (pintype "passive"))
      (node (ref "U18") (pin "5") (pinfunction "2IN+_5") (pintype "passive"))
      (node (ref "U2") (pin "11") (pinfunction "TACH-_11") (pintype "input"))
      (node (ref "U2") (pin "12") (pinfunction "GND_12") (pintype "power_in"))
      (node (ref "U3") (pin "4") (pinfunction "GND_4") (pintype "power_in"))
      (node (ref "U5") (pin "4") (pinfunction "GND_4") (pintype "passive"))
      (node (ref "U6") (pin "4") (pinfunction "GND_4") (pintype "passive"))
      (node (ref "U7") (pin "3") (pinfunction "1IN_+_3") (pintype "passive"))
      (node (ref "U7") (pin "4") (pinfunction "VCC-_4") (pintype "passive"))
      (node (ref "U7") (pin "5") (pinfunction "2IN+_5") (pintype "passive"))
      (node (ref "U8") (pin "3") (pinfunction "1IN_+_3") (pintype "passive"))
      (node (ref "U8") (pin "4") (pinfunction "VCC-_4") (pintype "passive"))
      (node (ref "U8") (pin "5") (pinfunction "2IN+_5") (pintype "passive"))
      (node (ref "U9") (pin "3") (pinfunction "1IN_+_3") (pintype "passive"))
      (node (ref "U9") (pin "4") (pinfunction "VCC-_4") (pintype "passive"))
      (node (ref "U9") (pin "5") (pinfunction "2IN+_5") (pintype "passive"))
      (node (ref "p1") (pin "2") (pinfunction "2_2") (pintype "passive"))
    )
    (net (code "135") (name "Net-(C1-Pad1)") (class "Default")
      (node (ref "C1") (pin "1") (pinfunction "1_1") (pintype "passive"))
      (node (ref "M1") (pin "1") (pinfunction "1_1") (pintype "passive"))
      (node (ref "R8") (pin "1") (pinfunction "1_1") (pintype "passive"))
    )
    (net (code "136") (name "Net-(C1-Pad2)") (class "Default")
      (node (ref "C1") (pin "2") (pinfunction "2_2") (pintype "passive"))
      (node (ref "R15") (pin "1") (pinfunction "1_1") (pintype "passive"))
    )
    (net (code "137") (name "Net-(C5-Pad2)") (class "Default")
      (node (ref "C5") (pin "2") (pinfunction "2_2") (pintype "passive"))
      (node (ref "C6") (pin "1") (pinfunction "1_1") (pintype "passive"))
    )
    (net (code "138") (name "Net-(C6-Pad2)") (class "Default")
      (node (ref "C6") (pin "2") (pinfunction "2_2") (pintype "passive"))
      (node (ref "C7") (pin "2") (pinfunction "2_2") (pintype "passive"))
      (node (ref "U2") (pin "2") (pinfunction "CP_2") (pintype "passive"))
    )
    (net (code "139") (name "Net-(C11-Pad1)") (class "Default")
      (node (ref "C11") (pin "1") (pinfunction "1_1") (pintype "passive"))
      (node (ref "C13") (pin "2") (pinfunction "2_2") (pintype "passive"))
      (node (ref "C9") (pin "2") (pinfunction "2_2") (pintype "passive"))
    )
    (net (code "140") (name "Net-(C13-Pad1)") (class "Default")
      (node (ref "C13") (pin "1") (pinfunction "1_1") (pintype "passive"))
      (node (ref "C16") (pin "2") (pinfunction "2_2") (pintype "passive"))
      (node (ref "C9") (pin "1") (pinfunction "1_1") (pintype "passive"))
      (node (ref "R36") (pin "2") (pinfunction "2_2") (pintype "passive"))
    )
    (net (code "141") (name "Net-(C19-Pad1)") (class "Default")
      (node (ref "C19") (pin "1") (pinfunction "1_1") (pintype "passive"))
      (node (ref "C20") (pin "2") (pinfunction "2_2") (pintype "passive"))
    )
    (net (code "142") (name "Net-(C21-Pad2)") (class "Default")
      (node (ref "C21") (pin "2") (pinfunction "2_2") (pintype "passive"))
      (node (ref "C23") (pin "2") (pinfunction "2_2") (pintype "passive"))
      (node (ref "C25") (pin "1") (pinfunction "1_1") (pintype "passive"))
    )
    (net (code "143") (name "Net-(C22-Pad1)") (class "Default")
      (node (ref "C22") (pin "1") (pinfunction "1_1") (pintype "passive"))
      (node (ref "C23") (pin "1") (pinfunction "1_1") (pintype "passive"))
    )
    (net (code "144") (name "Net-(C26-Pad2)") (class "Default")
      (node (ref "C26") (pin "2") (pinfunction "2_2") (pintype "passive"))
      (node (ref "C27") (pin "1") (pinfunction "1_1") (pintype "passive"))
    )
    (net (code "145") (name "Net-(C29-Pad2)") (class "Default")
      (node (ref "C29") (pin "2") (pinfunction "2_2") (pintype "passive"))
      (node (ref "C35") (pin "1") (pinfunction "1_1") (pintype "passive"))
      (node (ref "C37") (pin "1") (pinfunction "1_1") (pintype "passive"))
    )
    (net (code "146") (name "Net-(C30-Pad1)") (class "Default")
      (node (ref "C30") (pin "1") (pinfunction "1_1") (pintype "passive"))
      (node (ref "C34") (pin "2") (pinfunction "2_2") (pintype "passive"))
      (node (ref "C36") (pin "1") (pinfunction "1_1") (pintype "passive"))
    )
    (net (code "147") (name "Net-(C30-Pad2)") (class "Default")
      (node (ref "C30") (pin "2") (pinfunction "2_2") (pintype "passive"))
      (node (ref "C31") (pin "1") (pinfunction "1_1") (pintype "passive"))
    )
    (net (code "148") (name "Net-(C32-Pad1)") (class "Default")
      (node (ref "C32") (pin "1") (pinfunction "1_1") (pintype "passive"))
      (node (ref "C33") (pin "2") (pinfunction "2_2") (pintype "passive"))
    )
    (net (code "149") (name "Net-(C32-Pad2)") (class "Default")
      (node (ref "C32") (pin "2") (pinfunction "2_2") (pintype "passive"))
      (node (ref "C35") (pin "2") (pinfunction "2_2") (pintype "passive"))
    )
    (net (code "150") (name "Net-(C38-Pad2)") (class "Default")
      (node (ref "C38") (pin "2") (pinfunction "2_2") (pintype "passive"))
      (node (ref "C40") (pin "2") (pinfunction "2_2") (pintype "passive"))
      (node (ref "C41") (pin "1") (pinfunction "1_1") (pintype "passive"))
    )
    (net (code "151") (name "Net-(C39-Pad2)") (class "Default")
      (node (ref "C39") (pin "2") (pinfunction "2_2") (pintype "passive"))
      (node (ref "C40") (pin "1") (pinfunction "1_1") (pintype "passive"))
    )
    (net (code "152") (name "Net-(C65-Pad1)") (class "Default")
      (node (ref "C65") (pin "1") (pinfunction "1_1") (pintype "passive"))
      (node (ref "C66") (pin "2") (pinfunction "2_2") (pintype "passive"))
    )
    (net (code "153") (name "Net-(C67-Pad2)") (class "Default")
      (node (ref "C67") (pin "2") (pinfunction "2_2") (pintype "passive"))
      (node (ref "C69") (pin "2") (pinfunction "2_2") (pintype "passive"))
      (node (ref "C71") (pin "1") (pinfunction "1_1") (pintype "passive"))
    )
    (net (code "154") (name "Net-(C68-Pad1)") (class "Default")
      (node (ref "C68") (pin "1") (pinfunction "1_1") (pintype "passive"))
      (node (ref "C69") (pin "1") (pinfunction "1_1") (pintype "passive"))
    )
    (net (code "155") (name "Net-(C72-Pad2)") (class "Default")
      (node (ref "C72") (pin "2") (pinfunction "2_2") (pintype "passive"))
      (node (ref "C73") (pin "1") (pinfunction "1_1") (pintype "passive"))
    )
    (net (code "156") (name "Net-(C75-Pad2)") (class "Default")
      (node (ref "C75") (pin "2") (pinfunction "2_2") (pintype "passive"))
      (node (ref "C81") (pin "1") (pinfunction "1_1") (pintype "passive"))
      (node (ref "C83") (pin "1") (pinfunction "1_1") (pintype "passive"))
    )
    (net (code "157") (name "Net-(C76-Pad1)") (class "Default")
      (node (ref "C76") (pin "1") (pinfunction "1_1") (pintype "passive"))
      (node (ref "C80") (pin "2") (pinfunction "2_2") (pintype "passive"))
      (node (ref "C82") (pin "1") (pinfunction "1_1") (pintype "passive"))
    )
    (net (code "158") (name "Net-(C76-Pad2)") (class "Default")
      (node (ref "C76") (pin "2") (pinfunction "2_2") (pintype "passive"))
      (node (ref "C77") (pin "1") (pinfunction "1_1") (pintype "passive"))
    )
    (net (code "159") (name "Net-(C78-Pad1)") (class "Default")
      (node (ref "C78") (pin "1") (pinfunction "1_1") (pintype "passive"))
      (node (ref "C79") (pin "2") (pinfunction "2_2") (pintype "passive"))
    )
    (net (code "160") (name "Net-(C78-Pad2)") (class "Default")
      (node (ref "C78") (pin "2") (pinfunction "2_2") (pintype "passive"))
      (node (ref "C81") (pin "2") (pinfunction "2_2") (pintype "passive"))
    )
    (net (code "161") (name "Net-(C84-Pad2)") (class "Default")
      (node (ref "C84") (pin "2") (pinfunction "2_2") (pintype "passive"))
      (node (ref "C86") (pin "2") (pinfunction "2_2") (pintype "passive"))
      (node (ref "C87") (pin "1") (pinfunction "1_1") (pintype "passive"))
    )
    (net (code "162") (name "Net-(C85-Pad2)") (class "Default")
      (node (ref "C85") (pin "2") (pinfunction "2_2") (pintype "passive"))
      (node (ref "C86") (pin "1") (pinfunction "1_1") (pintype "passive"))
    )
    (net (code "163") (name "Net-(D1-A)") (class "Default")
      (node (ref "D1") (pin "2") (pinfunction "A_2") (pintype "passive"))
      (node (ref "R41") (pin "1") (pinfunction "1_1") (pintype "passive"))
    )
    (net (code "164") (name "Net-(D1-C)") (class "Default")
      (node (ref "D1") (pin "1") (pinfunction "C_1") (pintype "passive"))
      (node (ref "R39") (pin "2") (pinfunction "2_2") (pintype "passive"))
      (node (ref "U6") (pin "7") (pinfunction "OUT_B_7") (pintype "passive"))
    )
    (net (code "165") (name "Net-(D2-A)") (class "Default")
      (node (ref "D2") (pin "2") (pinfunction "A_2") (pintype "passive"))
      (node (ref "R43") (pin "1") (pinfunction "1_1") (pintype "passive"))
    )
    (net (code "166") (name "Net-(D2-C)") (class "Default")
      (node (ref "D2") (pin "1") (pinfunction "C_1") (pintype "passive"))
      (node (ref "R42") (pin "2") (pinfunction "2_2") (pintype "passive"))
      (node (ref "U6") (pin "1") (pinfunction "OUT_A_1") (pintype "passive"))
    )
    (net (code "167") (name "Net-(R1-Pad2)") (class "Default")
      (node (ref "R1") (pin "2") (pinfunction "2_2") (pintype "passive"))
      (node (ref "R9") (pin "1") (pinfunction "1_1") (pintype "passive"))
    )
    (net (code "168") (name "Net-(R10-Pad1)") (class "Default")
      (node (ref "R10") (pin "1") (pinfunction "1_1") (pintype "passive"))
      (node (ref "R2") (pin "2") (pinfunction "2_2") (pintype "passive"))
    )
    (net (code "169") (name "Net-(R10-Pad2)") (class "Default")
      (node (ref "R10") (pin "2") (pinfunction "2_2") (pintype "passive"))
      (node (ref "R19") (pin "2") (pinfunction "2_2") (pintype "passive"))
    )
    (net (code "170") (name "Net-(R11-Pad1)") (class "Default")
      (node (ref "R11") (pin "1") (pinfunction "1_1") (pintype "passive"))
      (node (ref "R3") (pin "2") (pinfunction "2_2") (pintype "passive"))
    )
    (net (code "171") (name "Net-(R11-Pad2)") (class "Default")
      (node (ref "R11") (pin "2") (pinfunction "2_2") (pintype "passive"))
      (node (ref "R22") (pin "2") (pinfunction "2_2") (pintype "passive"))
    )
    (net (code "172") (name "Net-(R12-Pad1)") (class "Default")
      (node (ref "R12") (pin "1") (pinfunction "1_1") (pintype "passive"))
      (node (ref "R4") (pin "2") (pinfunction "2_2") (pintype "passive"))
    )
    (net (code "173") (name "Net-(R12-Pad2)") (class "Default")
      (node (ref "R12") (pin "2") (pinfunction "2_2") (pintype "passive"))
      (node (ref "R20") (pin "2") (pinfunction "2_2") (pintype "passive"))
    )
    (net (code "174") (name "Net-(R13-Pad1)") (class "Default")
      (node (ref "R13") (pin "1") (pinfunction "1_1") (pintype "passive"))
      (node (ref "R5") (pin "2") (pinfunction "2_2") (pintype "passive"))
    )
    (net (code "175") (name "Net-(R13-Pad2)") (class "Default")
      (node (ref "R13") (pin "2") (pinfunction "2_2") (pintype "passive"))
      (node (ref "R21") (pin "2") (pinfunction "2_2") (pintype "passive"))
    )
    (net (code "176") (name "Net-(R14-Pad1)") (class "Default")
      (node (ref "R14") (pin "1") (pinfunction "1_1") (pintype "passive"))
      (node (ref "R6") (pin "2") (pinfunction "2_2") (pintype "passive"))
    )
    (net (code "177") (name "Net-(R14-Pad2)") (class "Default")
      (node (ref "R14") (pin "2") (pinfunction "2_2") (pintype "passive"))
      (node (ref "R23") (pin "2") (pinfunction "2_2") (pintype "passive"))
    )
    (net (code "178") (name "Net-(R18-Pad2)") (class "Default")
      (node (ref "R18") (pin "2") (pinfunction "2_2") (pintype "passive"))
      (node (ref "R9") (pin "2") (pinfunction "2_2") (pintype "passive"))
    )
    (net (code "179") (name "Net-(R28-Pad1)") (class "Default")
      (node (ref "R28") (pin "1") (pinfunction "1_1") (pintype "passive"))
      (node (ref "R34") (pin "2") (pinfunction "2_2") (pintype "passive"))
    )
    (net (code "180") (name "Net-(R37-Pad1)") (class "Default")
      (node (ref "R37") (pin "1") (pinfunction "1_1") (pintype "passive"))
      (node (ref "R40") (pin "2") (pinfunction "2_2") (pintype "passive"))
    )
    (net (code "181") (name "Net-(R44-Pad2)") (class "Default")
      (node (ref "R44") (pin "2") (pinfunction "2_2") (pintype "passive"))
      (node (ref "R45") (pin "1") (pinfunction "1_1") (pintype "passive"))
    )
    (net (code "182") (name "Net-(R46-Pad1)") (class "Default")
      (node (ref "R46") (pin "1") (pinfunction "1_1") (pintype "passive"))
      (node (ref "R48") (pin "2") (pinfunction "2_2") (pintype "passive"))
      (node (ref "R49") (pin "1") (pinfunction "1_1") (pintype "passive"))
    )
    (net (code "183") (name "Net-(R47-Pad1)") (class "Default")
      (node (ref "R47") (pin "1") (pinfunction "1_1") (pintype "passive"))
      (node (ref "R57") (pin "1") (pinfunction "1_1") (pintype "passive"))
    )
    (net (code "184") (name "Net-(R50-Pad1)") (class "Default")
      (node (ref "R50") (pin "1") (pinfunction "1_1") (pintype "passive"))
      (node (ref "R51") (pin "1") (pinfunction "1_1") (pintype "passive"))
      (node (ref "R54") (pin "1") (pinfunction "1_1") (pintype "passive"))
    )
    (net (code "185") (name "Net-(R51-Pad2)") (class "Default")
      (node (ref "R51") (pin "2") (pinfunction "2_2") (pintype "passive"))
      (node (ref "R52") (pin "2") (pinfunction "2_2") (pintype "passive"))
    )
    (net (code "186") (name "Net-(R56-Pad1)") (class "Default")
      (node (ref "R56") (pin "1") (pinfunction "1_1") (pintype "passive"))
      (node (ref "R59") (pin "2") (pinfunction "2_2") (pintype "passive"))
    )
    (net (code "187") (name "Net-(R56-Pad2)") (class "Default")
      (node (ref "R56") (pin "2") (pinfunction "2_2") (pintype "passive"))
      (node (ref "R58") (pin "1") (pinfunction "1_1") (pintype "passive"))
    )
    (net (code "188") (name "Net-(R60-Pad2)") (class "Default")
      (node (ref "R60") (pin "2") (pinfunction "2_2") (pintype "passive"))
      (node (ref "R61") (pin "2") (pinfunction "2_2") (pintype "passive"))
    )
    (net (code "189") (name "Net-(R62-Pad1)") (class "Default")
      (node (ref "R62") (pin "1") (pinfunction "1_1") (pintype "passive"))
      (node (ref "R73") (pin "1") (pinfunction "1_1") (pintype "passive"))
    )
    (net (code "190") (name "Net-(R63-Pad1)") (class "Default")
      (node (ref "R63") (pin "1") (pinfunction "1_1") (pintype "passive"))
      (node (ref "R68") (pin "2") (pinfunction "2_2") (pintype "passive"))
      (node (ref "R69") (pin "1") (pinfunction "1_1") (pintype "passive"))
    )
    (net (code "191") (name "Net-(R65-Pad2)") (class "Default")
      (node (ref "R65") (pin "2") (pinfunction "2_2") (pintype "passive"))
      (node (ref "R66") (pin "1") (pinfunction "1_1") (pintype "passive"))
    )
    (net (code "192") (name "Net-(R66-Pad2)") (class "Default")
      (node (ref "R66") (pin "2") (pinfunction "2_2") (pintype "passive"))
      (node (ref "R67") (pin "2") (pinfunction "2_2") (pintype "passive"))
    )
    (net (code "193") (name "Net-(R71-Pad2)") (class "Default")
      (node (ref "R71") (pin "2") (pinfunction "2_2") (pintype "passive"))
      (node (ref "R72") (pin "1") (pinfunction "1_1") (pintype "passive"))
    )
    (net (code "194") (name "Net-(R75-Pad2)") (class "Default")
      (node (ref "R75") (pin "2") (pinfunction "2_2") (pintype "passive"))
      (node (ref "R77") (pin "2") (pinfunction "2_2") (pintype "passive"))
      (node (ref "R80") (pin "1") (pinfunction "1_1") (pintype "passive"))
    )
    (net (code "195") (name "Net-(R76-Pad1)") (class "Default")
      (node (ref "R76") (pin "1") (pinfunction "1_1") (pintype "passive"))
      (node (ref "R77") (pin "1") (pinfunction "1_1") (pintype "passive"))
    )
    (net (code "196") (name "Net-(R78-Pad1)") (class "Default")
      (node (ref "R78") (pin "1") (pinfunction "1_1") (pintype "passive"))
      (node (ref "R79") (pin "2") (pinfunction "2_2") (pintype "passive"))
    )
    (net (code "197") (name "Net-(R181-Pad1)") (class "Default")
      (node (ref "R181") (pin "1") (pinfunction "1_1") (pintype "passive"))
      (node (ref "R182") (pin "2") (pinfunction "2_2") (pintype "passive"))
    )
    (net (code "198") (name "Net-(R184-Pad1)") (class "Default")
      (node (ref "R184") (pin "1") (pinfunction "1_1") (pintype "passive"))
      (node (ref "R185") (pin "2") (pinfunction "2_2") (pintype "passive"))
    )
    (net (code "199") (name "Net-(R187-Pad1)") (class "Default")
      (node (ref "R187") (pin "1") (pinfunction "1_1") (pintype "passive"))
      (node (ref "R188") (pin "2") (pinfunction "2_2") (pintype "passive"))
    )
    (net (code "200") (name "Net-(R190-Pad1)") (class "Default")
      (node (ref "R190") (pin "1") (pinfunction "1_1") (pintype "passive"))
      (node (ref "R191") (pin "2") (pinfunction "2_2") (pintype "passive"))
    )
    (net (code "201") (name "Net-(R193-Pad1)") (class "Default")
      (node (ref "R193") (pin "1") (pinfunction "1_1") (pintype "passive"))
      (node (ref "R203") (pin "1") (pinfunction "1_1") (pintype "passive"))
    )
    (net (code "202") (name "Net-(R194-Pad1)") (class "Default")
      (node (ref "R194") (pin "1") (pinfunction "1_1") (pintype "passive"))
      (node (ref "R204") (pin "1") (pinfunction "1_1") (pintype "passive"))
    )
    (net (code "203") (name "Net-(R195-Pad1)") (class "Default")
      (node (ref "R195") (pin "1") (pinfunction "1_1") (pintype "passive"))
      (node (ref "R205") (pin "1") (pinfunction "1_1") (pintype "passive"))
    )
    (net (code "204") (name "Net-(R196-Pad1)") (class "Default")
      (node (ref "R196") (pin "1") (pinfunction "1_1") (pintype "passive"))
      (node (ref "R206") (pin "1") (pinfunction "1_1") (pintype "passive"))
    )
    (net (code "205") (name "Net-(R197-Pad1)") (class "Default")
      (node (ref "R197") (pin "1") (pinfunction "1_1") (pintype "passive"))
      (node (ref "R198") (pin "2") (pinfunction "2_2") (pintype "passive"))
    )
    (net (code "206") (name "Net-(R199-Pad1)") (class "Default")
      (node (ref "R199") (pin "1") (pinfunction "1_1") (pintype "passive"))
      (node (ref "R200") (pin "2") (pinfunction "2_2") (pintype "passive"))
    )
    (net (code "207") (name "Net-(R207-Pad1)") (class "Default")
      (node (ref "R207") (pin "1") (pinfunction "1_1") (pintype "passive"))
      (node (ref "R209") (pin "2") (pinfunction "2_2") (pintype "passive"))
    )
    (net (code "208") (name "Net-(R207-Pad2)") (class "Default")
      (node (ref "R207") (pin "2") (pinfunction "2_2") (pintype "passive"))
      (node (ref "R208") (pin "1") (pinfunction "1_1") (pintype "passive"))
    )
    (net (code "209") (name "Net-(U1A-INVERTING_INPUT_A)") (class "Default")
      (node (ref "R15") (pin "2") (pinfunction "2_2") (pintype "passive"))
      (node (ref "R7") (pin "2") (pinfunction "2_2") (pintype "passive"))
      (node (ref "U1") (pin "2") (pinfunction "INVERTING_INPUT_A_2") (pintype "passive"))
    )
    (net (code "210") (name "Net-(U1A-NON-INVERTING_INPUT_A)") (class "Default")
      (node (ref "R16") (pin "2") (pinfunction "2_2") (pintype "passive"))
      (node (ref "R17") (pin "1") (pinfunction "1_1") (pintype "passive"))
      (node (ref "U1") (pin "3") (pinfunction "NON-INVERTING_INPUT_A_3") (pintype "passive"))
    )
    (net (code "211") (name "Net-(U1A-OUTPUT_A)") (class "Default")
      (node (ref "R132") (pin "2") (pinfunction "2_2") (pintype "passive"))
      (node (ref "R135") (pin "2") (pinfunction "2_2") (pintype "passive"))
      (node (ref "R136") (pin "2") (pinfunction "2_2") (pintype "passive"))
      (node (ref "R138") (pin "2") (pinfunction "2_2") (pintype "passive"))
      (node (ref "R140") (pin "2") (pinfunction "2_2") (pintype "passive"))
      (node (ref "R144") (pin "2") (pinfunction "2_2") (pintype "passive"))
      (node (ref "R7") (pin "3") (pinfunction "3_3") (pintype "passive"))
      (node (ref "U1") (pin "1") (pinfunction "OUTPUT_A_1") (pintype "passive"))
    )
    (net (code "212") (name "Net-(U2-IN+)") (class "Default")
      (node (ref "C10") (pin "2") (pinfunction "2_2") (pintype "passive"))
      (node (ref "R33") (pin "1") (pinfunction "1_1") (pintype "passive"))
      (node (ref "U2") (pin "3") (pinfunction "CP_3") (pintype "passive"))
      (node (ref "U2") (pin "4") (pinfunction "IN+_4") (pintype "passive"))
    )
    (net (code "213") (name "Net-(U2-TACH+)") (class "Default")
      (node (ref "C3") (pin "1") (pinfunction "1_1") (pintype "passive"))
      (node (ref "R27") (pin "1") (pinfunction "1_1") (pintype "passive"))
      (node (ref "U2") (pin "1") (pinfunction "TACH+_1") (pintype "input"))
    )
    (net (code "214") (name "Net-(U2-V+)") (class "Default")
      (node (ref "R35") (pin "1") (pinfunction "1_1") (pintype "passive"))
      (node (ref "U2") (pin "9") (pinfunction "V+_9") (pintype "power_in"))
    )
    (net (code "215") (name "Net-(U3A-INA+)") (class "Default")
      (node (ref "R26") (pin "1") (pinfunction "1_1") (pintype "passive"))
      (node (ref "R31") (pin "2") (pinfunction "2_2") (pintype "passive"))
      (node (ref "R32") (pin "1") (pinfunction "1_1") (pintype "passive"))
      (node (ref "U3") (pin "3") (pinfunction "INA+_3") (pintype "input"))
    )
    (net (code "216") (name "Net-(U4-BASE)") (class "Default")
      (node (ref "C11") (pin "2") (pinfunction "2_2") (pintype "passive"))
      (node (ref "R34") (pin "1") (pinfunction "1_1") (pintype "passive"))
      (node (ref "R37") (pin "2") (pinfunction "2_2") (pintype "passive"))
      (node (ref "U4") (pin "3") (pinfunction "BASE_3") (pintype "passive"))
    )
    (net (code "217") (name "Net-(U4-COLLECTOR)") (class "Default")
      (node (ref "C12") (pin "1") (pinfunction "1_1") (pintype "passive"))
      (node (ref "C14") (pin "1") (pinfunction "1_1") (pintype "passive"))
      (node (ref "C8") (pin "1") (pinfunction "1_1") (pintype "passive"))
      (node (ref "R30") (pin "1") (pinfunction "1_1") (pintype "passive"))
      (node (ref "U4") (pin "2") (pinfunction "COLLECTOR_2") (pintype "passive"))
    )
    (net (code "218") (name "Net-(U4-EMITTER)") (class "Default")
      (node (ref "C17") (pin "1") (pinfunction "1_1") (pintype "passive"))
      (node (ref "C18") (pin "1") (pinfunction "1_1") (pintype "passive"))
      (node (ref "R38") (pin "2") (pinfunction "2_2") (pintype "passive"))
      (node (ref "U4") (pin "1") (pinfunction "EMITTER_1") (pintype "passive"))
    )
    (net (code "219") (name "unconnected-(C28-Pad2)") (class "Default")
      (node (ref "C28") (pin "2") (pinfunction "2_2") (pintype "passive"))
    )
    (net (code "220") (name "unconnected-(C74-Pad2)") (class "Default")
      (node (ref "C74") (pin "2") (pinfunction "2_2") (pintype "passive"))
    )
    (net (code "221") (name "unconnected-(P2-Pad3)") (class "Default")
      (node (ref "P2") (pin "3") (pinfunction "3_3") (pintype "passive"))
    )
    (net (code "222") (name "unconnected-(R7-Pad1)") (class "Default")
      (node (ref "R7") (pin "1") (pinfunction "1_1") (pintype "passive+no_connect"))
    )
    (net (code "223") (name "unconnected-(R18-Pad3)") (class "Default")
      (node (ref "R18") (pin "3") (pinfunction "3_3") (pintype "passive+no_connect"))
    )
    (net (code "224") (name "unconnected-(R19-Pad3)") (class "Default")
      (node (ref "R19") (pin "3") (pinfunction "3_3") (pintype "passive+no_connect"))
    )
    (net (code "225") (name "unconnected-(R20-Pad3)") (class "Default")
      (node (ref "R20") (pin "3") (pinfunction "3_3") (pintype "passive+no_connect"))
    )
    (net (code "226") (name "unconnected-(R21-Pad3)") (class "Default")
      (node (ref "R21") (pin "3") (pinfunction "3_3") (pintype "passive+no_connect"))
    )
    (net (code "227") (name "unconnected-(R22-Pad3)") (class "Default")
      (node (ref "R22") (pin "3") (pinfunction "3_3") (pintype "passive+no_connect"))
    )
    (net (code "228") (name "unconnected-(R23-Pad3)") (class "Default")
      (node (ref "R23") (pin "3") (pinfunction "3_3") (pintype "passive+no_connect"))
    )
    (net (code "229") (name "unconnected-(U2-NC-Pad6)") (class "Default")
      (node (ref "U2") (pin "6") (pinfunction "NC_6") (pintype "passive+no_connect"))
    )
    (net (code "230") (name "unconnected-(U2-NC-Pad7)") (class "Default")
      (node (ref "U2") (pin "7") (pinfunction "NC_7") (pintype "passive+no_connect"))
    )
    (net (code "231") (name "unconnected-(U2-NC-Pad13)") (class "Default")
      (node (ref "U2") (pin "13") (pinfunction "NC_13") (pintype "passive+no_connect"))
    )
    (net (code "232") (name "unconnected-(U2-NC-Pad14)") (class "Default")
      (node (ref "U2") (pin "14") (pinfunction "NC_14") (pintype "passive+no_connect"))
    )
    (net (code "233") (name "unconnected-(Z1-Pad3)") (class "Default")
      (node (ref "Z1") (pin "3") (pinfunction "3_3") (pintype "passive+no_connect"))
    )
    (net (code "234") (name "unconnected-(Z2-Pad3)") (class "Default")
      (node (ref "Z2") (pin "3") (pinfunction "3_3") (pintype "passive+no_connect"))
    )
    (net (code "235") (name "unconnected-(Z3-Pad3)") (class "Default")
      (node (ref "Z3") (pin "3") (pinfunction "3_3") (pintype "passive+no_connect"))
    )
    (net (code "236") (name "unconnected-(Z4-Pad3)") (class "Default")
      (node (ref "Z4") (pin "3") (pinfunction "3_3") (pintype "passive+no_connect"))
    )
  )
)
